# ReA4091_Mini_2024-10-24_SCH.net
KiCad netlist of a schematic drawn in EasyEDA
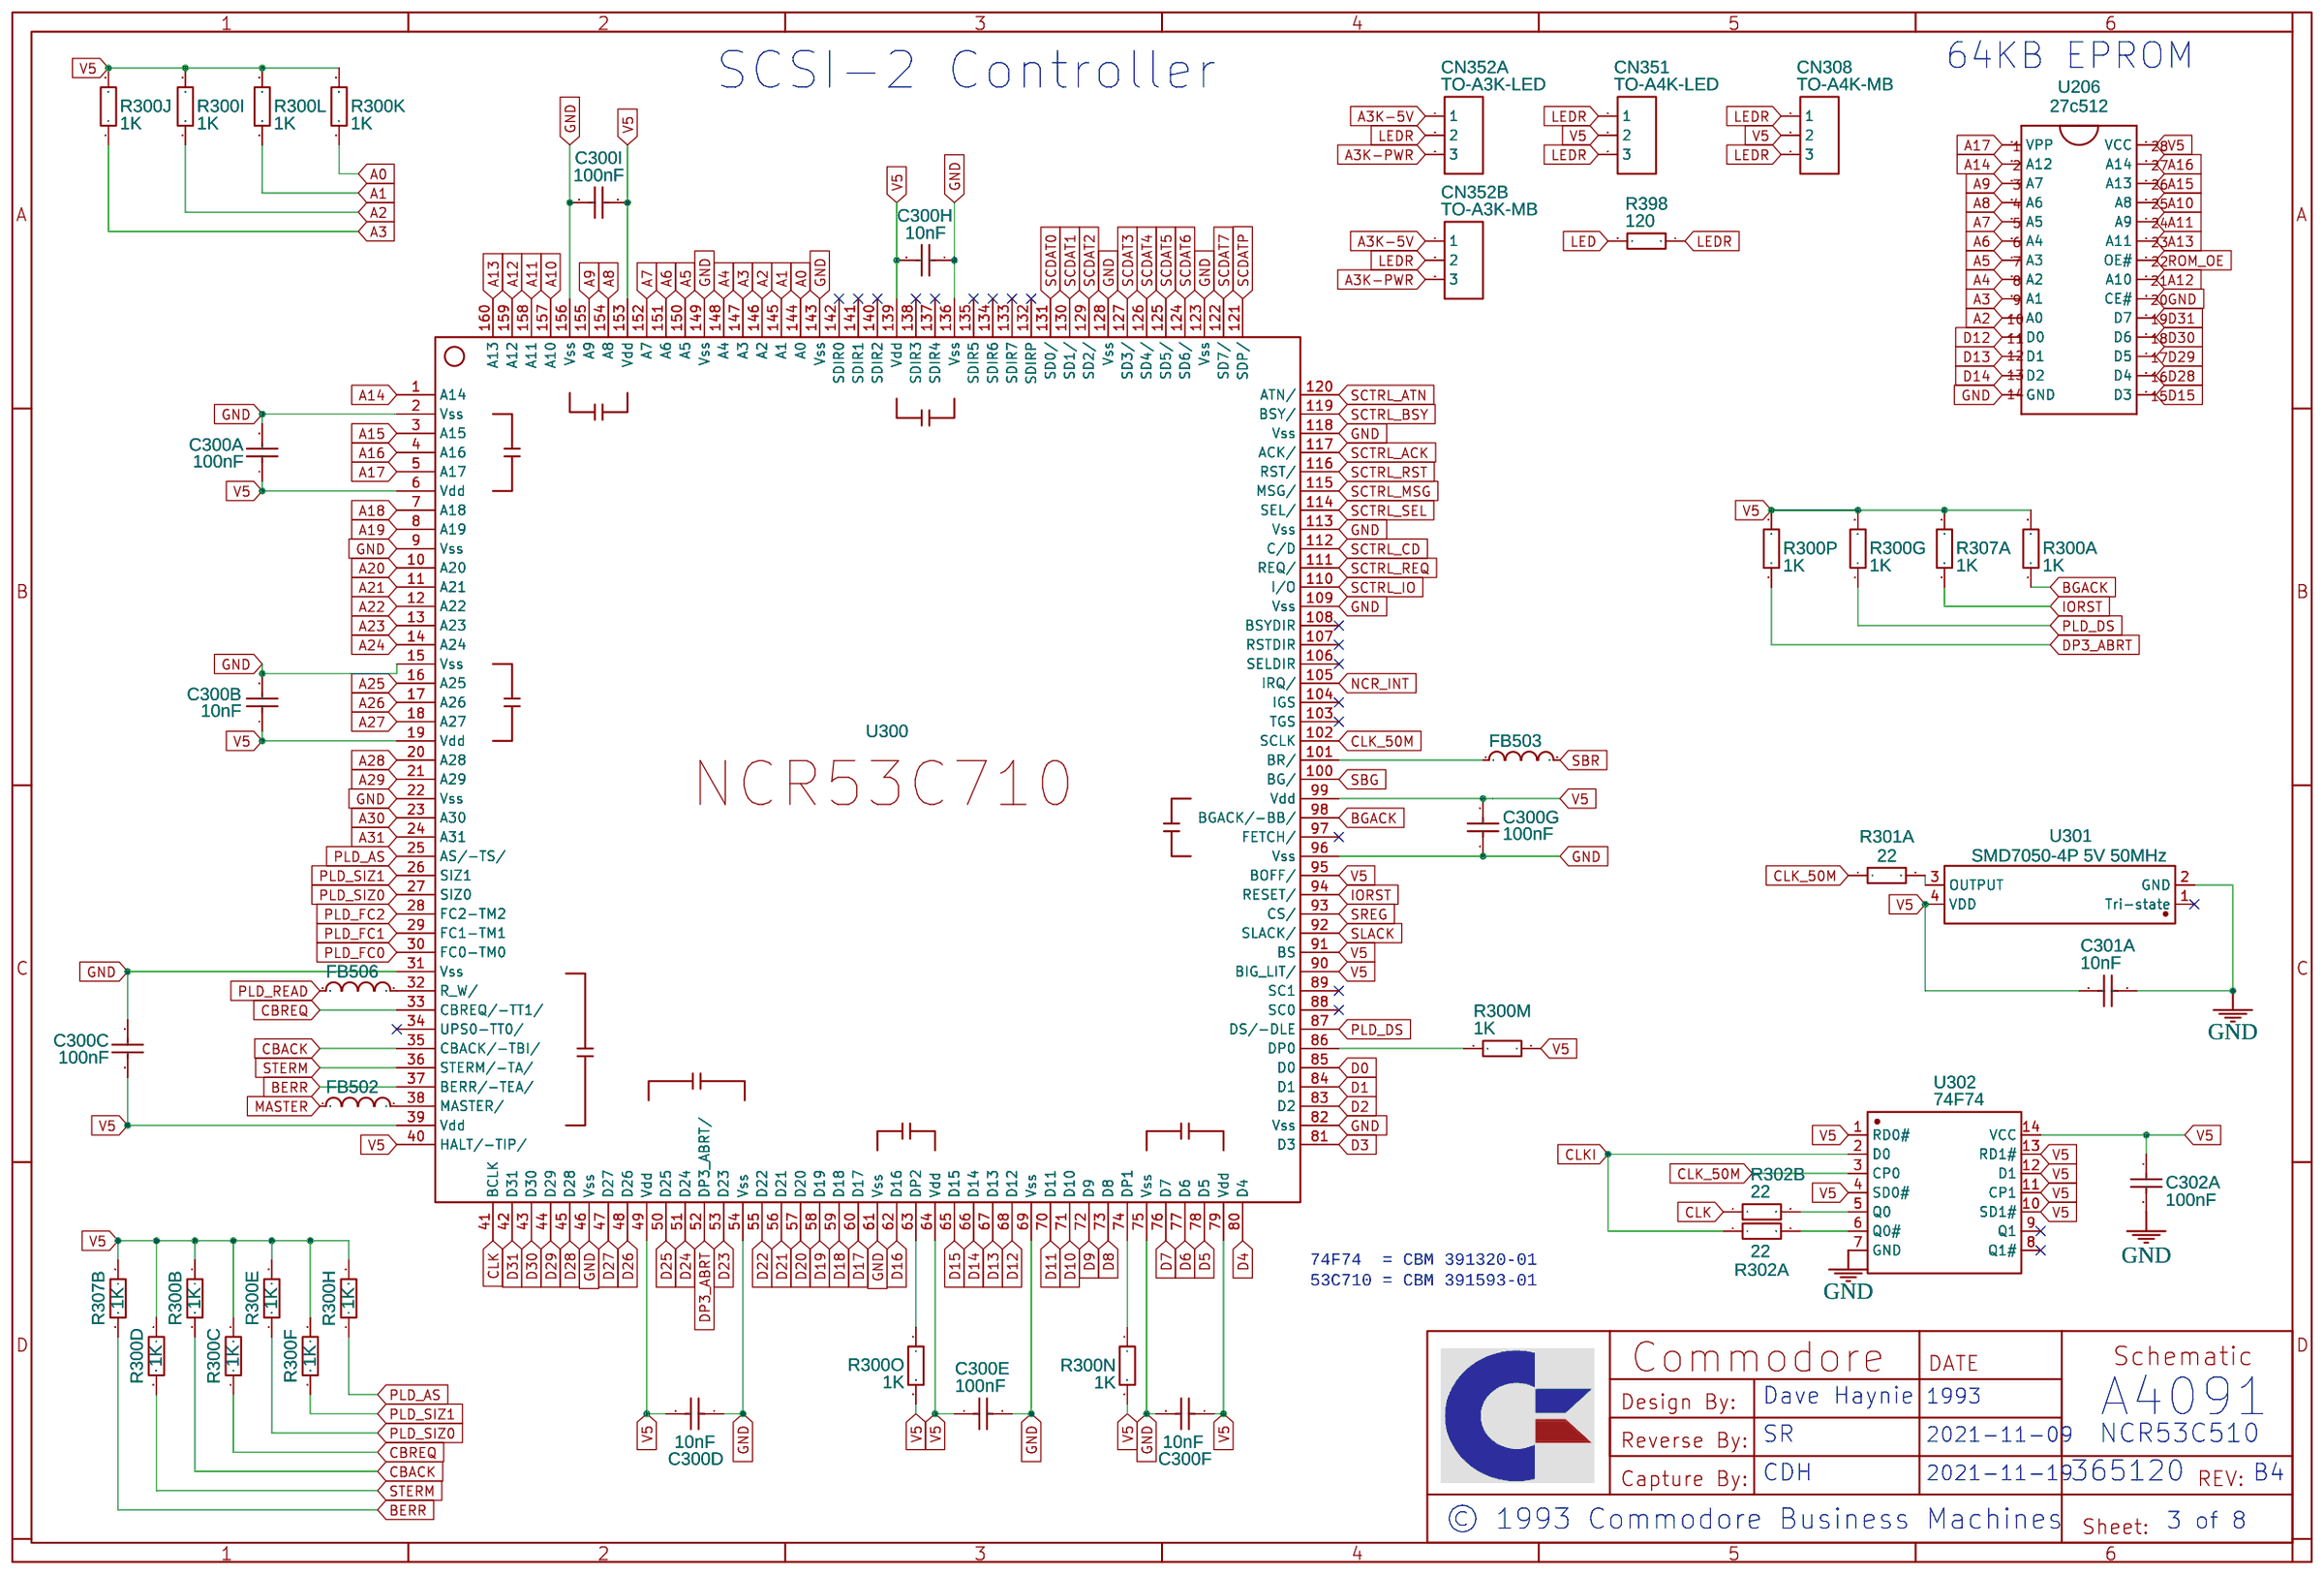
[diagram p0: NCR53C710]
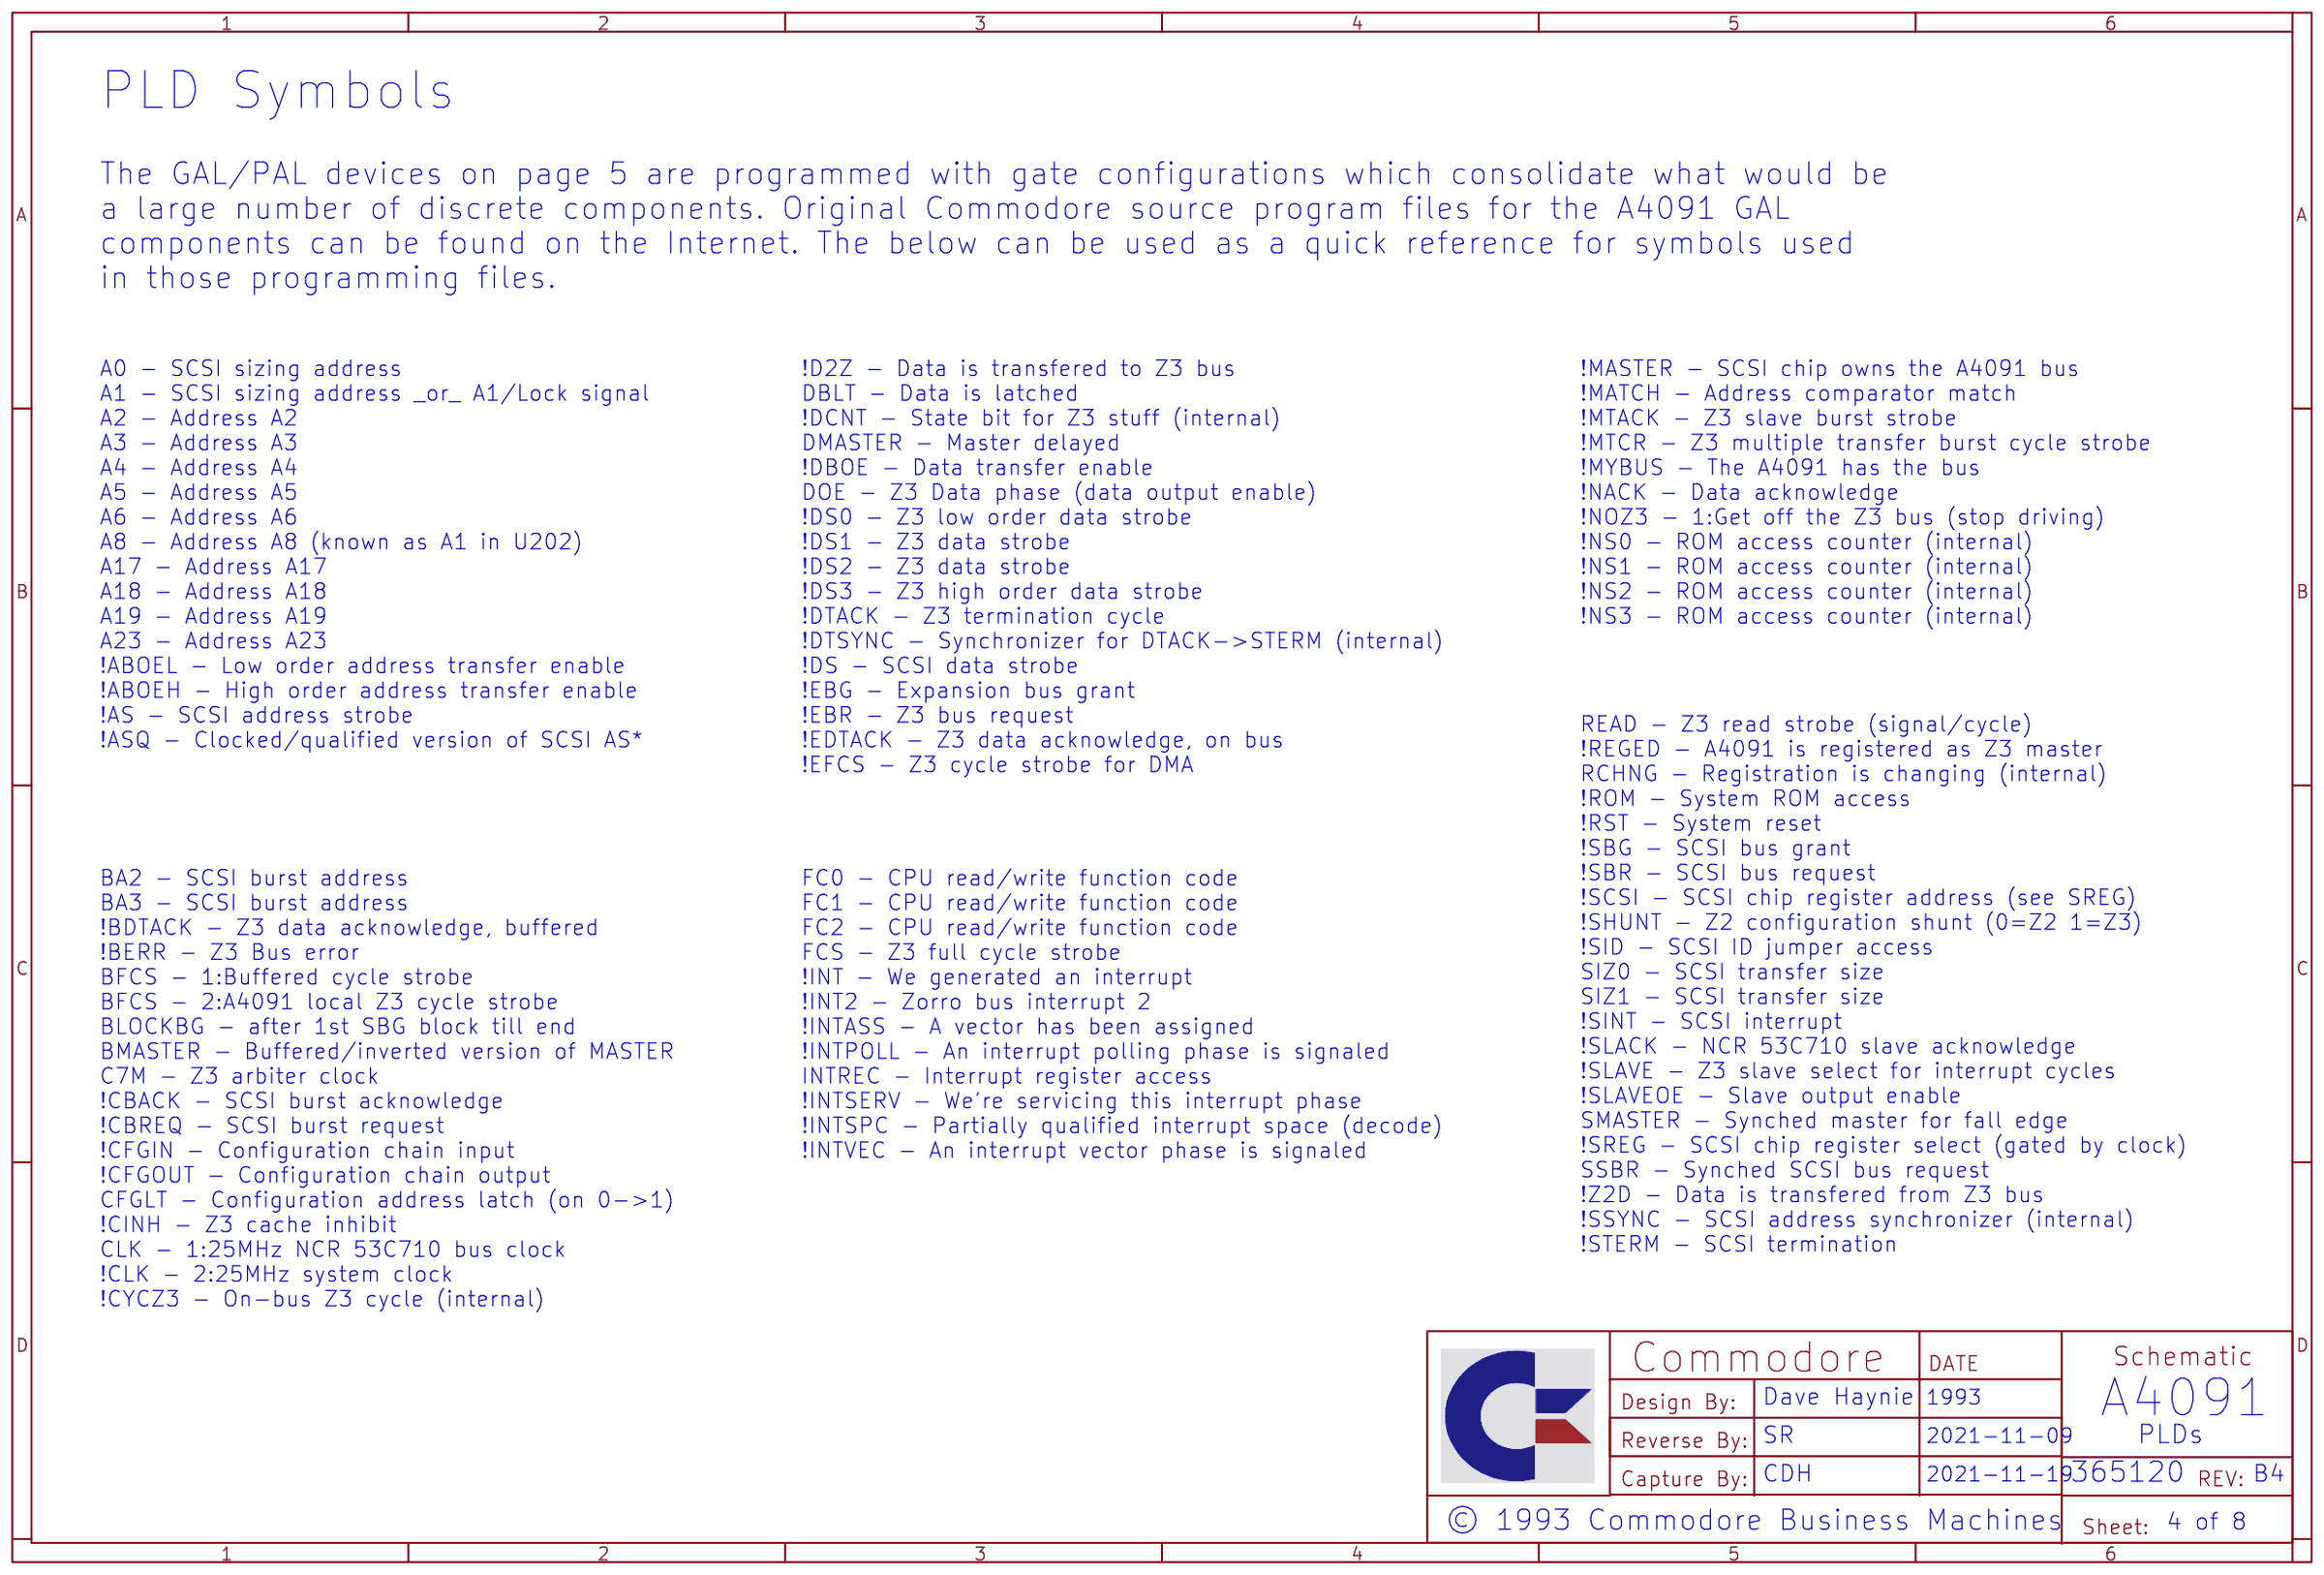
[diagram p1: PLD Symbols]
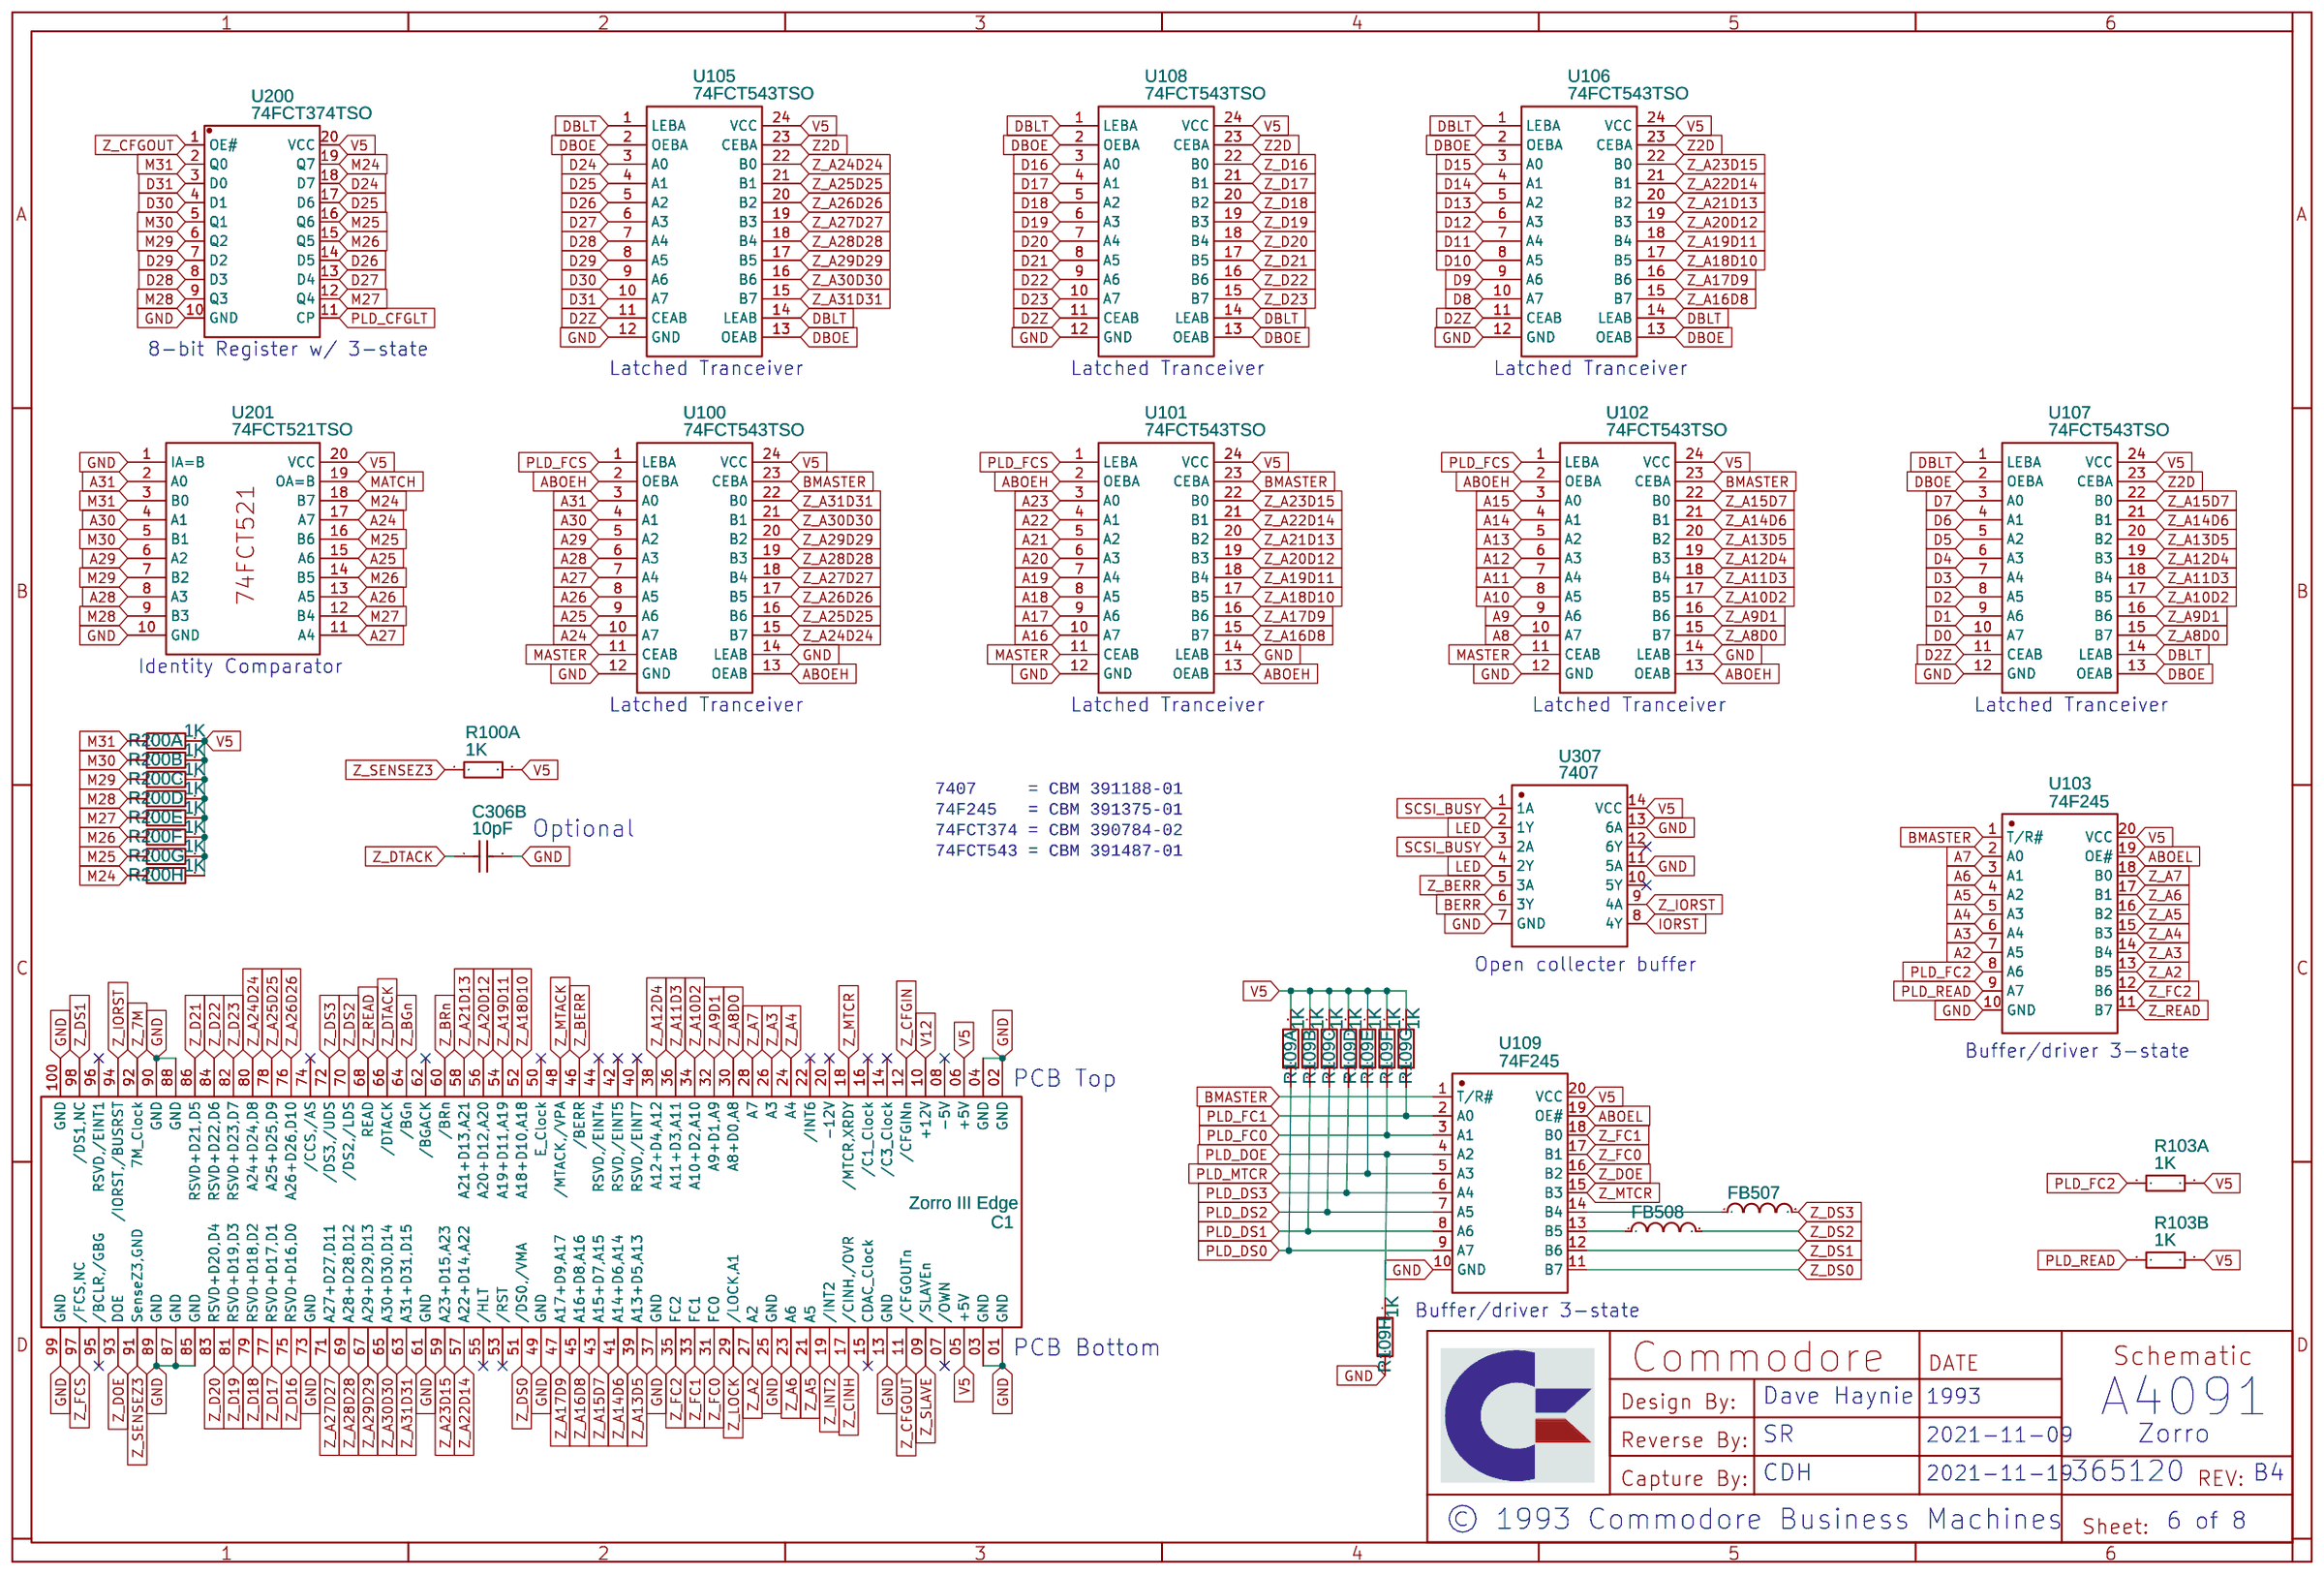
[diagram p2: Zorro]
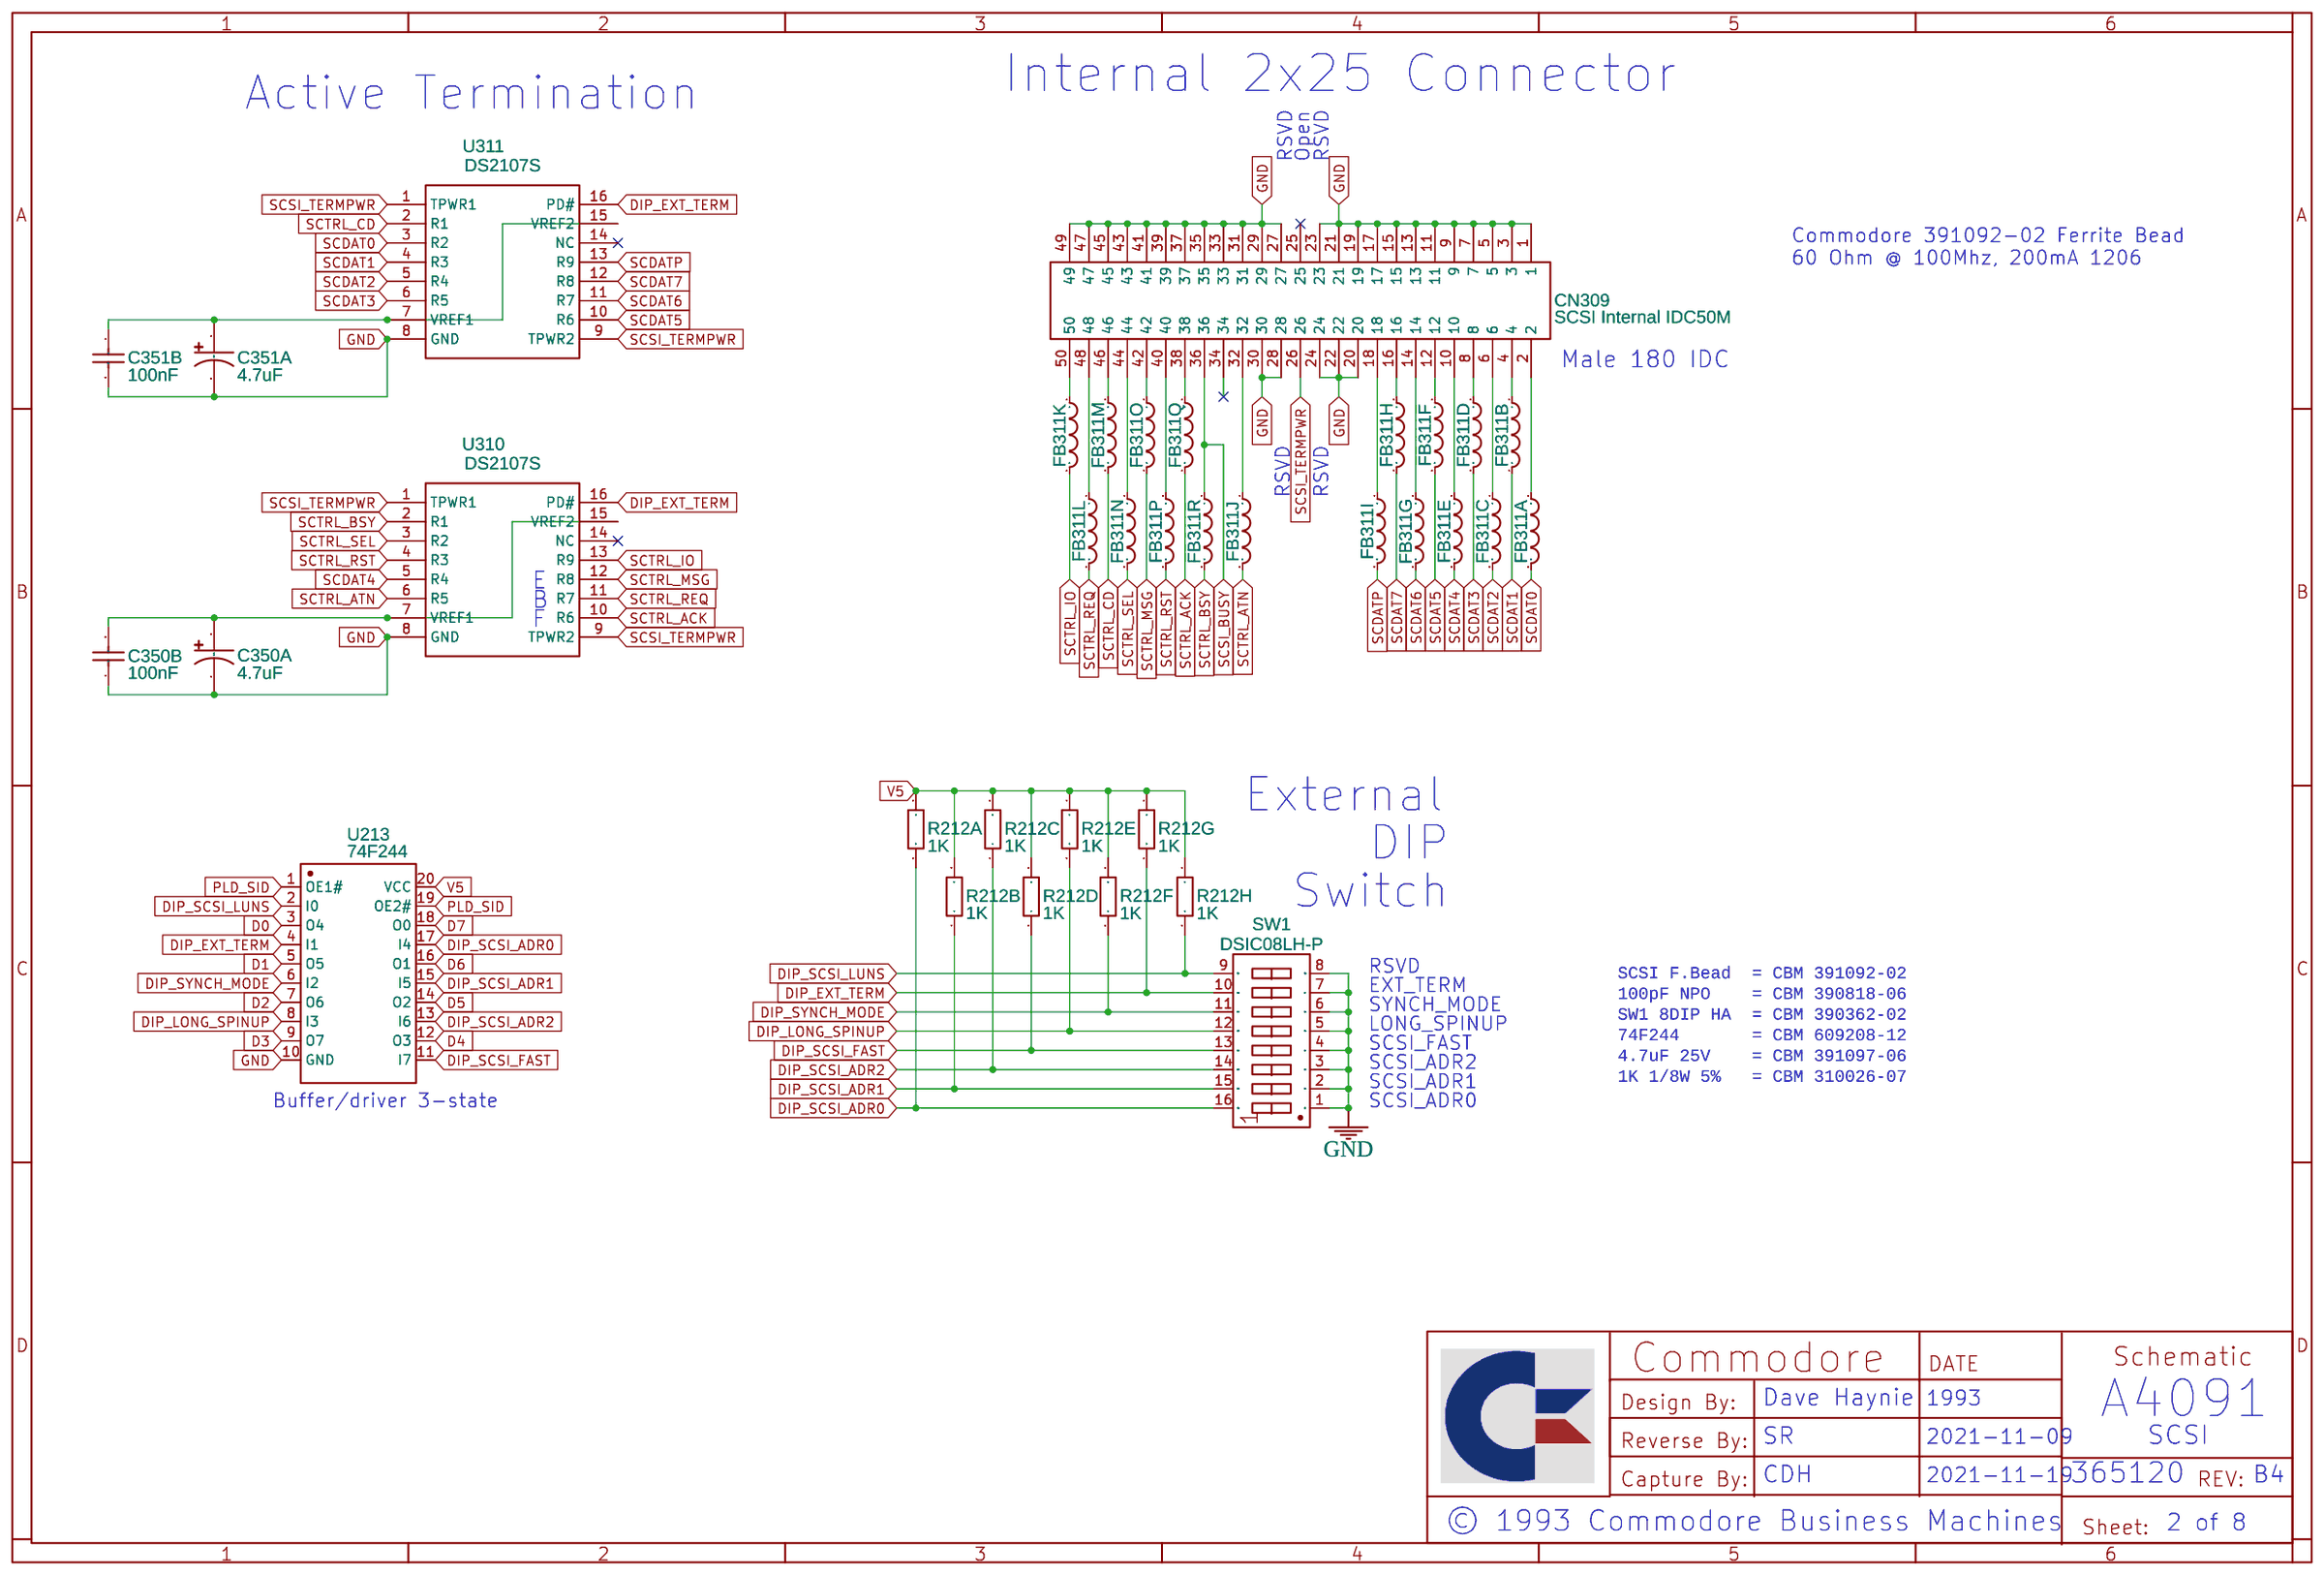
[diagram p3: SCSI]
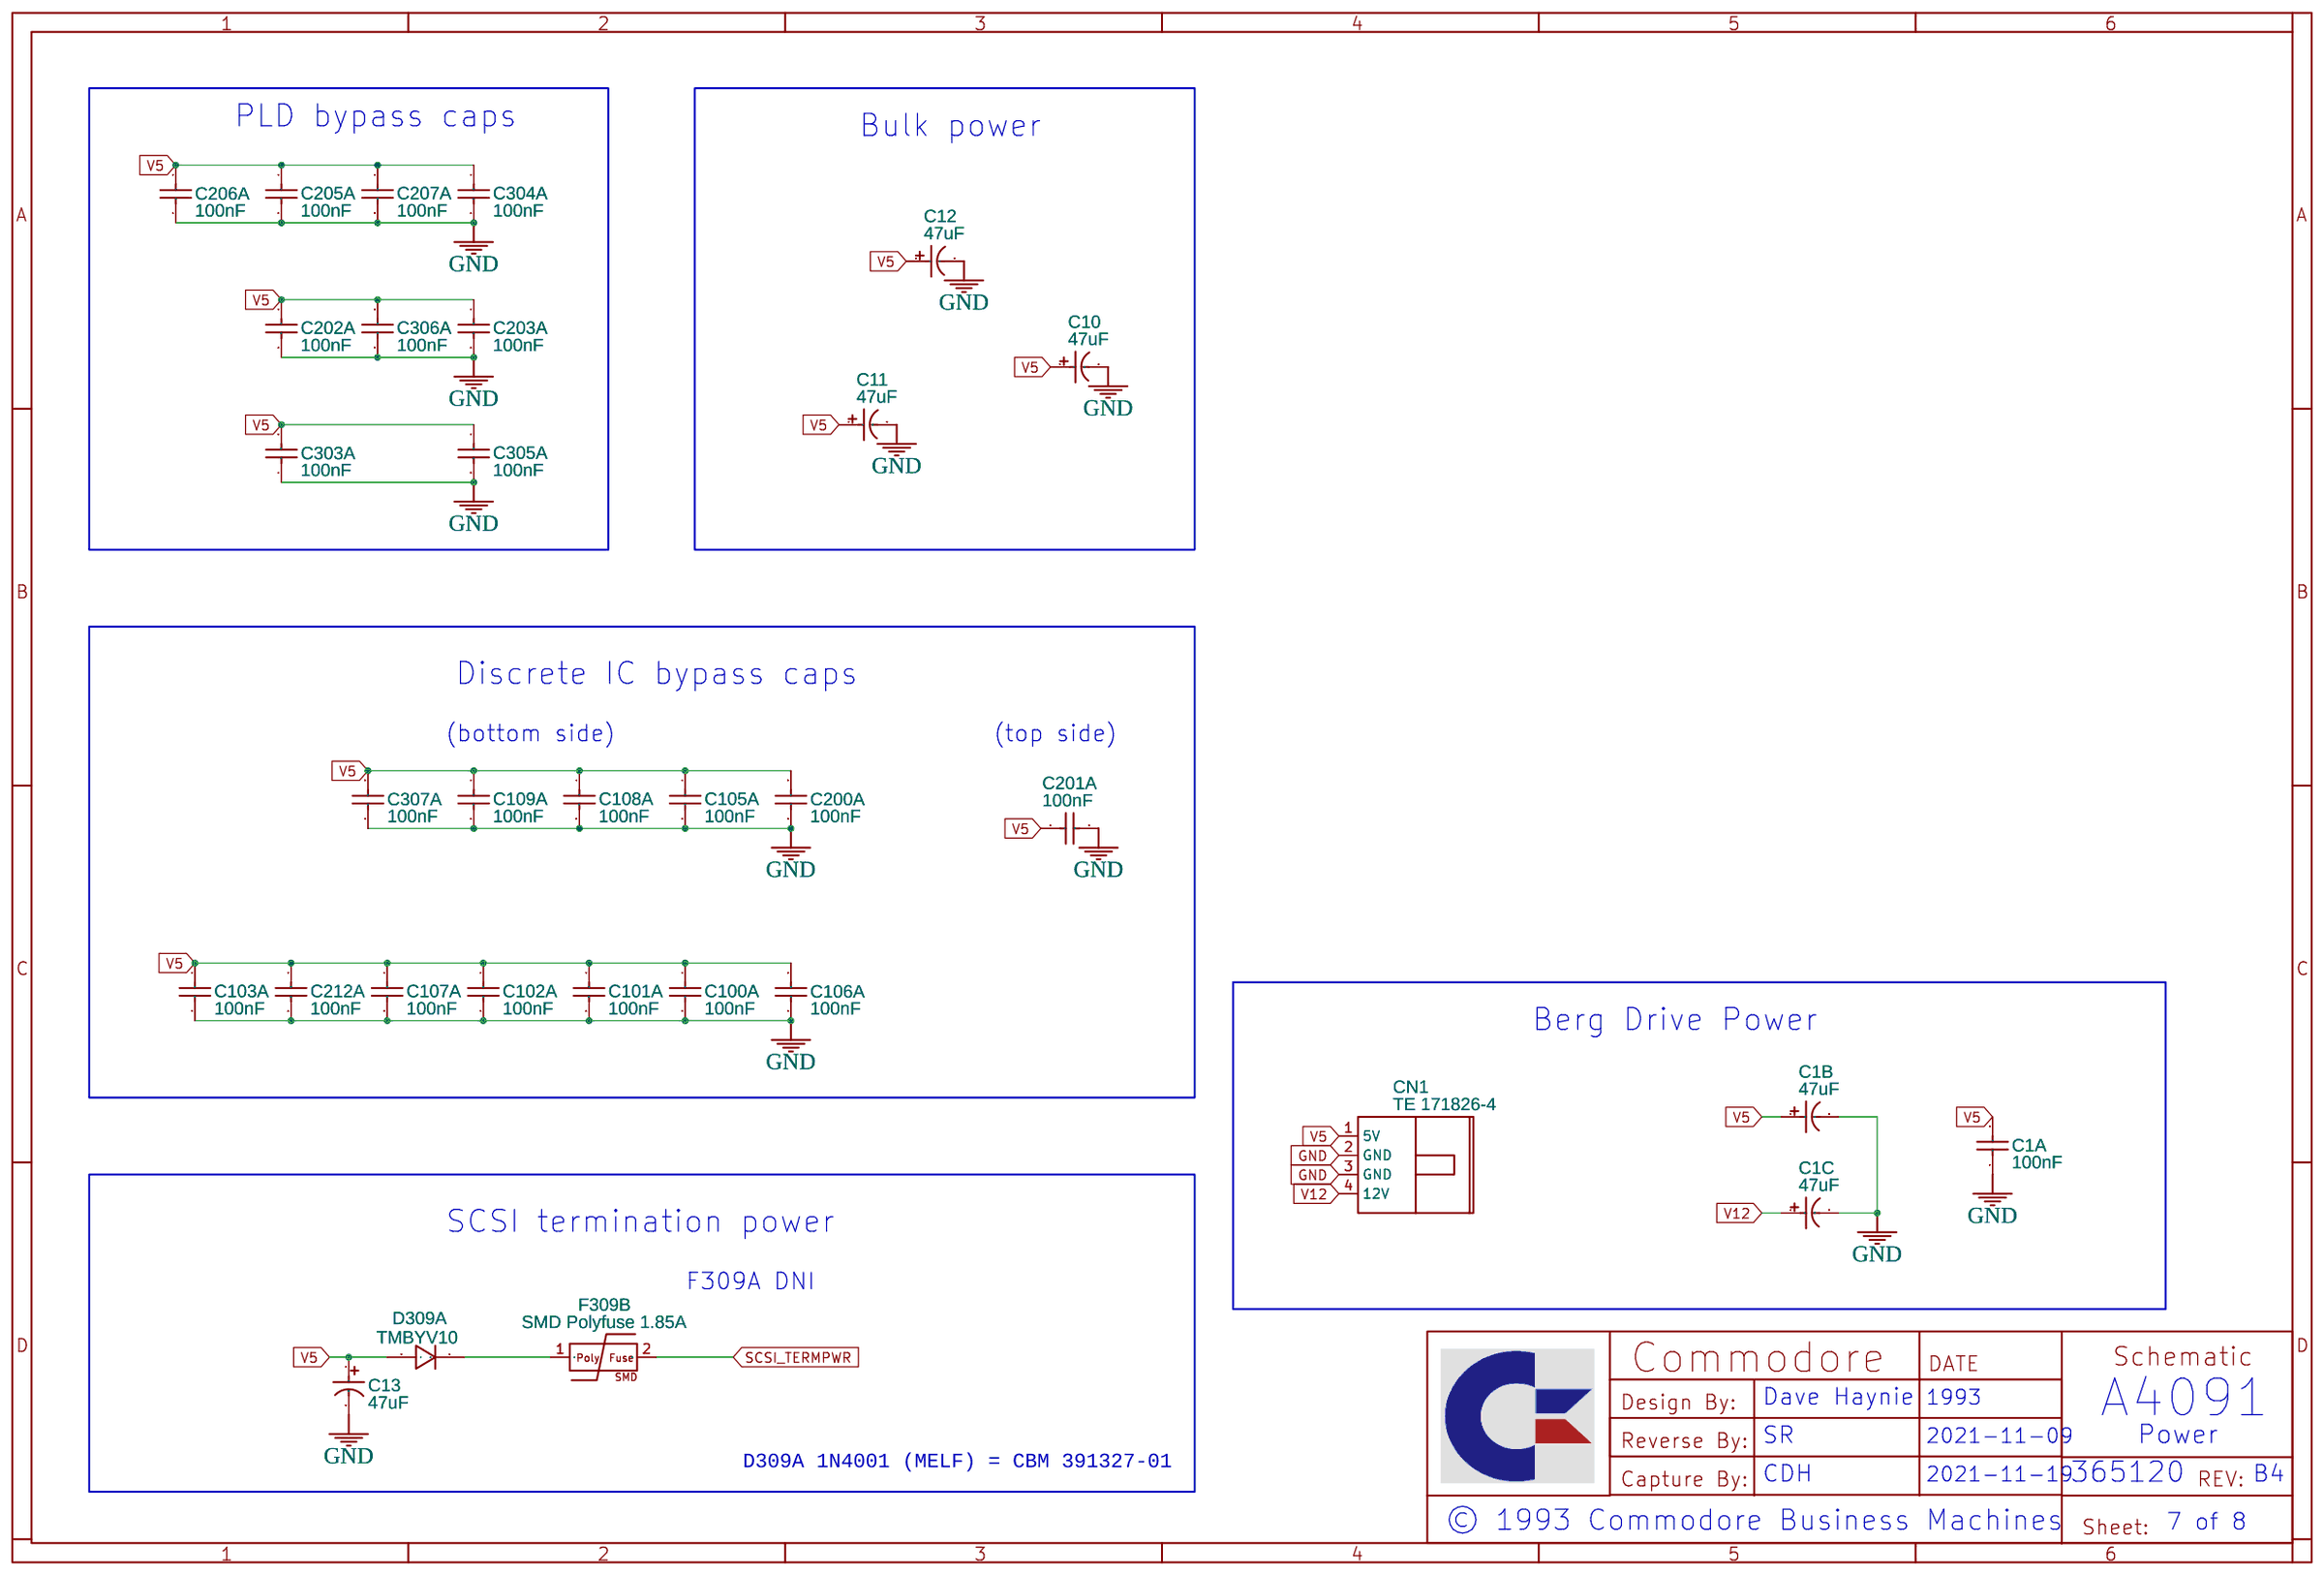
[diagram p4: Power]
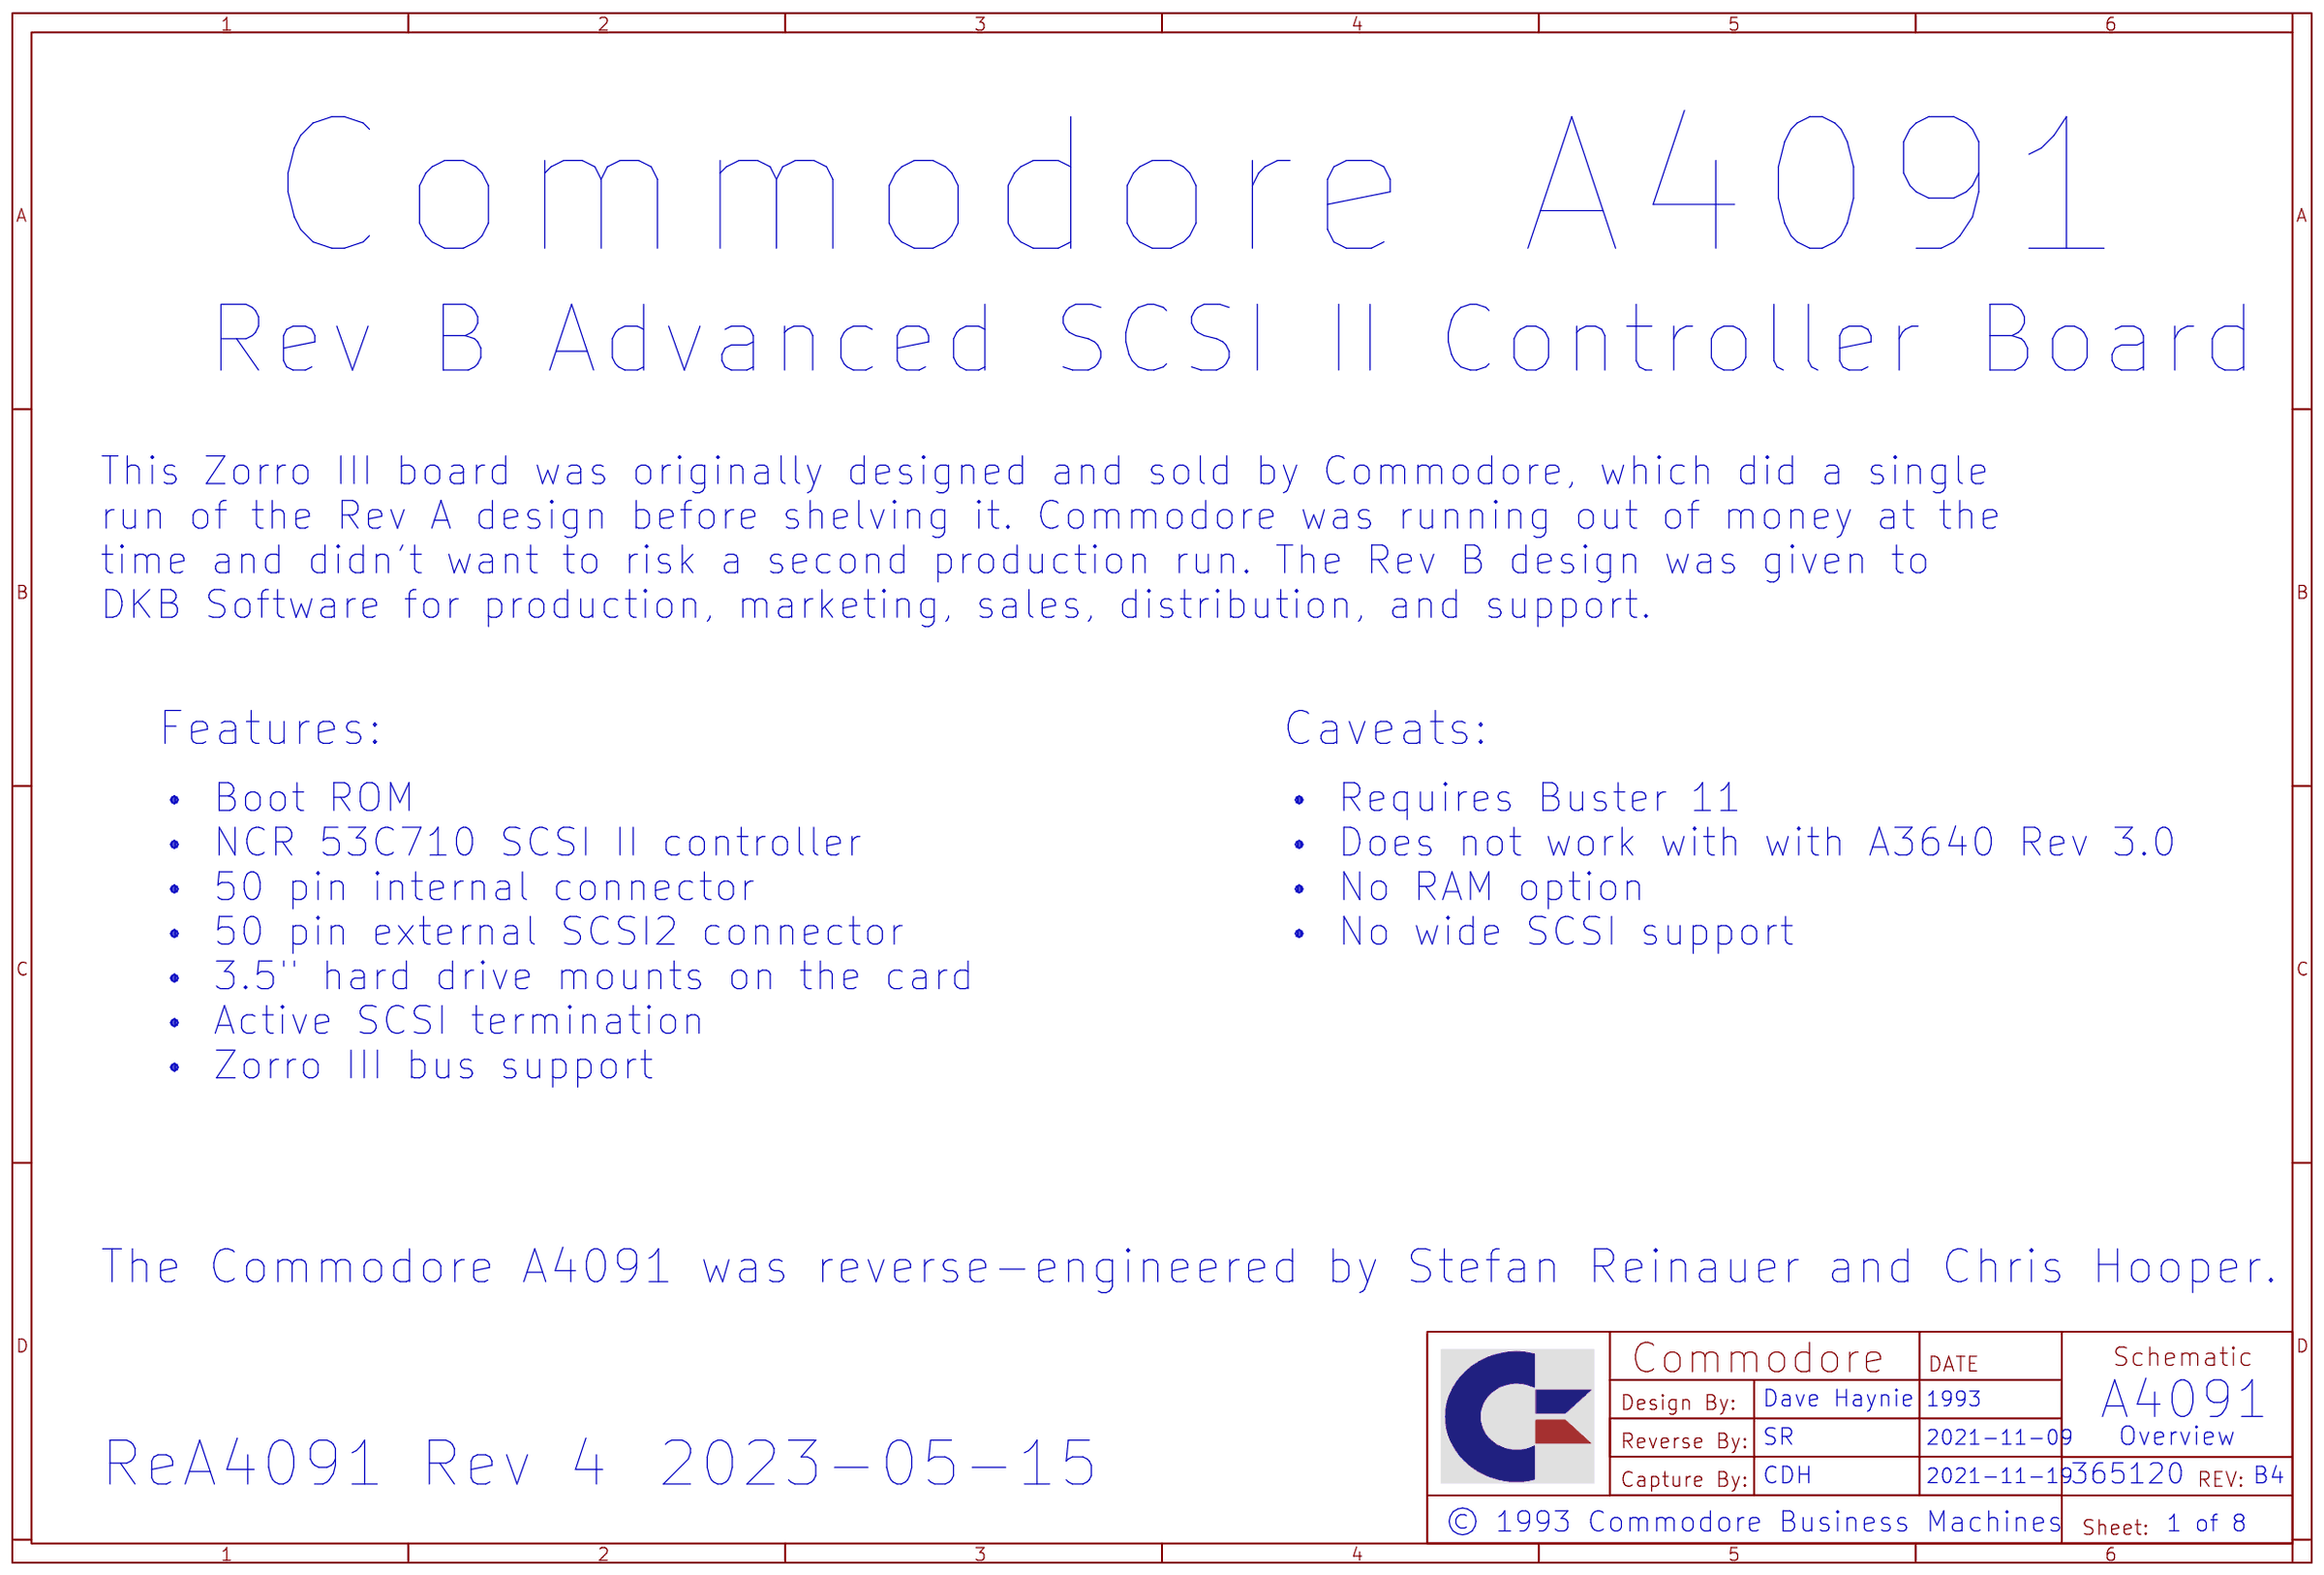
[diagram p5: Overview]
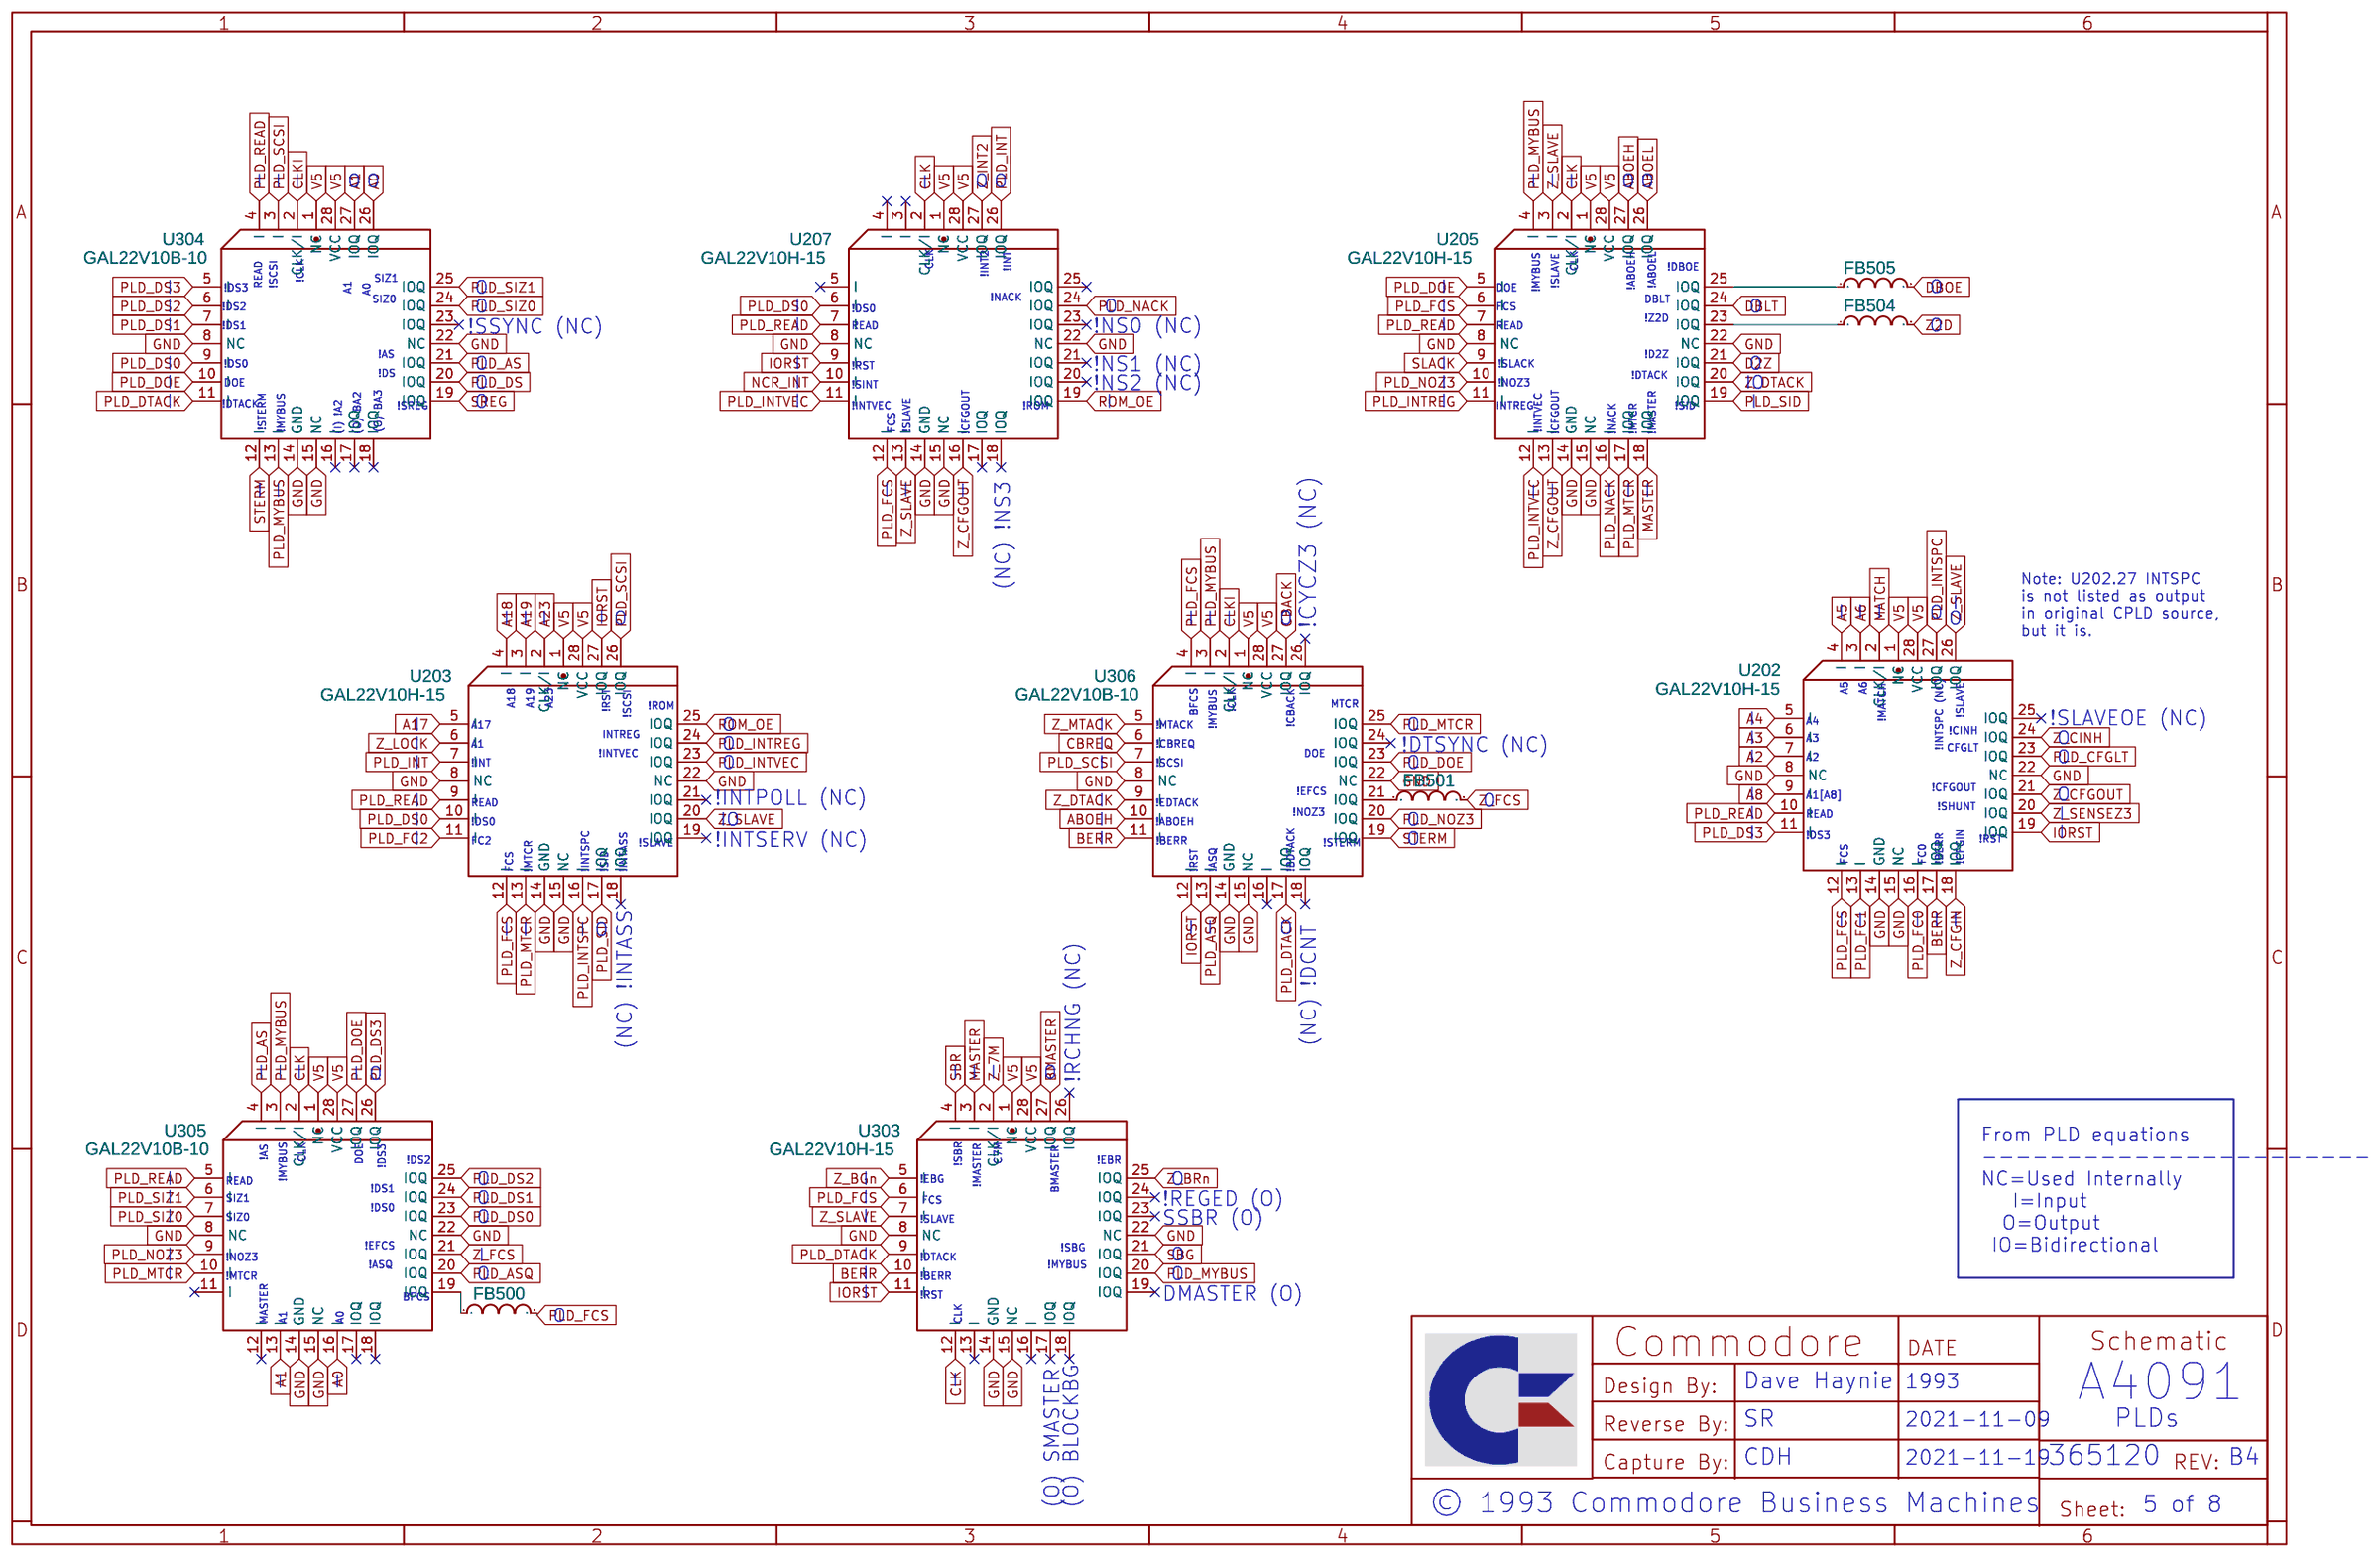
[diagram p6: PLDs]

(export (version "E")
  (design (tool "Eeschema 10.0.6"))
  (components
    (comp (ref "C300A")
      (value "100nF")
      (fields (field (name "Manufacturer Part") "CL31B104KBCNNNC") (field (name "Manufacturer") "SAMSUNG"))
      (libsource (lib "") (part "CL31B104KBCNNNC_5"))
    )
    (comp (ref "C300B")
      (value "10nF")
      (fields (field (name "Manufacturer Part") "1206B103K500NT") (field (name "Manufacturer") "FH"))
      (libsource (lib "") (part "1206B103K500NT_1"))
    )
    (comp (ref "C300C")
      (value "100nF")
      (fields (field (name "Manufacturer Part") "CL31B104KBCNNNC") (field (name "Manufacturer") "SAMSUNG"))
      (libsource (lib "") (part "CL31B104KBCNNNC_2"))
    )
    (comp (ref "C300D")
      (value "10nF")
      (fields (field (name "Manufacturer Part") "1206B103K500NT") (field (name "Manufacturer") "FH"))
      (libsource (lib "") (part "1206B103K500NT_4"))
    )
    (comp (ref "C300E")
      (value "100nF")
      (fields (field (name "Manufacturer Part") "CL31B104KBCNNNC") (field (name "Manufacturer") "SAMSUNG"))
      (libsource (lib "") (part "CL31B104KBCNNNC_4"))
    )
    (comp (ref "C300F")
      (value "10nF")
      (fields (field (name "Manufacturer Part") "1206B103K500NT") (field (name "Manufacturer") "FH"))
      (libsource (lib "") (part "1206B103K500NT_3"))
    )
    (comp (ref "C300G")
      (value "100nF")
      (fields (field (name "Manufacturer Part") "CL31B104KBCNNNC") (field (name "Manufacturer") "SAMSUNG"))
      (libsource (lib "") (part "CL31B104KBCNNNC_3"))
    )
    (comp (ref "C300H")
      (value "10nF")
      (fields (field (name "Manufacturer Part") "1206B103K500NT") (field (name "Manufacturer") "FH"))
      (libsource (lib "") (part "1206B103K500NT_2"))
    )
    (comp (ref "C300I")
      (value "100nF")
      (fields (field (name "Manufacturer Part") "CL31B104KBCNNNC") (field (name "Manufacturer") "SAMSUNG"))
      (libsource (lib "") (part "CL31B104KBCNNNC"))
    )
    (comp (ref "C301A")
      (value "10nF")
      (fields (field (name "Manufacturer Part") "1206B103K500NT") (field (name "Manufacturer") "FH"))
      (libsource (lib "") (part "1206B103K500NT"))
    )
    (comp (ref "C302A")
      (value "100nF")
      (fields (field (name "Manufacturer Part") "CL31B104KBCNNNC") (field (name "Manufacturer") "SAMSUNG"))
      (libsource (lib "") (part "CL31B104KBCNNNC_1"))
    )
    (comp (ref "CN308")
      (value "TO-A4K-MB")
      (fields (field (name "Manufacturer Part") "Header2.54mm 1*3P") (field (name "Manufacturer") "BOOMELE"))
      (libsource (lib "") (part "Header-Male-2.54_1x3_1"))
    )
    (comp (ref "CN351")
      (value "TO-A4K-LED")
      (fields (field (name "Manufacturer Part") "Header2.54mm 1*3P") (field (name "Manufacturer") "BOOMELE"))
      (libsource (lib "") (part "Header-Male-2.54_1x3_1"))
    )
    (comp (ref "CN352A")
      (value "TO-A3K-LED")
      (fields (field (name "Manufacturer Part") "Header2.54mm 1*3P") (field (name "Manufacturer") "BOOMELE"))
      (libsource (lib "") (part "Header-Male-2.54_1x3_2"))
    )
    (comp (ref "CN352B")
      (value "TO-A3K-MB")
      (fields (field (name "Manufacturer Part") "Header2.54mm 1*3P") (field (name "Manufacturer") "BOOMELE"))
      (libsource (lib "") (part "Header-Male-2.54_1x3"))
    )
    (comp (ref "FB502")
      (value "60Ω")
      (fields (field (name "Manufacturer Part") "CBG321609U600T") (field (name "Manufacturer") "FH"))
      (libsource (lib "") (part "MLB3216-601(f)"))
    )
    (comp (ref "FB503")
      (value "60Ω")
      (fields (field (name "Manufacturer Part") "CBG321609U600T") (field (name "Manufacturer") "FH"))
      (libsource (lib "") (part "MLB3216-601(f)_1"))
    )
    (comp (ref "FB506")
      (value "60Ω")
      (fields (field (name "Manufacturer Part") "CBG321609U600T") (field (name "Manufacturer") "FH"))
      (libsource (lib "") (part "MLB3216-601(f)"))
    )
    (comp (ref "R300A")
      (value "1K")
      (fields (field (name "Manufacturer Part") "1206W4F1001T5E") (field (name "Manufacturer") "UniOhm"))
      (libsource (lib "") (part "1206W4F1001T5E_10"))
    )
    (comp (ref "R300B")
      (value "1K")
      (fields (field (name "Manufacturer Part") "1206W4F1001T5E") (field (name "Manufacturer") "UniOhm"))
      (libsource (lib "") (part "1206W4F1001T5E_12"))
    )
    (comp (ref "R300C")
      (value "1K")
      (fields (field (name "Manufacturer Part") "1206W4F1001T5E") (field (name "Manufacturer") "UniOhm"))
      (libsource (lib "") (part "1206W4F1001T5E"))
    )
    (comp (ref "R300D")
      (value "1K")
      (fields (field (name "Manufacturer Part") "1206W4F1001T5E") (field (name "Manufacturer") "UniOhm"))
      (libsource (lib "") (part "1206W4F1001T5E_4"))
    )
    (comp (ref "R300E")
      (value "1K")
      (fields (field (name "Manufacturer Part") "1206W4F1001T5E") (field (name "Manufacturer") "UniOhm"))
      (libsource (lib "") (part "1206W4F1001T5E_14"))
    )
    (comp (ref "R300F")
      (value "1K")
      (fields (field (name "Manufacturer Part") "1206W4F1001T5E") (field (name "Manufacturer") "UniOhm"))
      (libsource (lib "") (part "1206W4F1001T5E_8"))
    )
    (comp (ref "R300G")
      (value "1K")
      (fields (field (name "Manufacturer Part") "1206W4F1001T5E") (field (name "Manufacturer") "UniOhm"))
      (libsource (lib "") (part "1206W4F1001T5E_17"))
    )
    (comp (ref "R300H")
      (value "1K")
      (fields (field (name "Manufacturer Part") "1206W4F1001T5E") (field (name "Manufacturer") "UniOhm"))
      (libsource (lib "") (part "1206W4F1001T5E_11"))
    )
    (comp (ref "R300I")
      (value "1K")
      (fields (field (name "Manufacturer Part") "1206W4F1001T5E") (field (name "Manufacturer") "UniOhm"))
      (libsource (lib "") (part "1206W4F1001T5E_16"))
    )
    (comp (ref "R300J")
      (value "1K")
      (fields (field (name "Manufacturer Part") "1206W4F1001T5E") (field (name "Manufacturer") "UniOhm"))
      (libsource (lib "") (part "1206W4F1001T5E_9"))
    )
    (comp (ref "R300K")
      (value "1K")
      (fields (field (name "Manufacturer Part") "1206W4F1001T5E") (field (name "Manufacturer") "UniOhm"))
      (libsource (lib "") (part "1206W4F1001T5E_1"))
    )
    (comp (ref "R300L")
      (value "1K")
      (fields (field (name "Manufacturer Part") "1206W4F1001T5E") (field (name "Manufacturer") "UniOhm"))
      (libsource (lib "") (part "1206W4F1001T5E_15"))
    )
    (comp (ref "R300M")
      (value "1K")
      (fields (field (name "Manufacturer Part") "1206W4F1001T5E") (field (name "Manufacturer") "UniOhm"))
      (libsource (lib "") (part "1206W4F1001T5E_2"))
    )
    (comp (ref "R300N")
      (value "1K")
      (fields (field (name "Manufacturer Part") "1206W4F1001T5E") (field (name "Manufacturer") "UniOhm"))
      (libsource (lib "") (part "1206W4F1001T5E_7"))
    )
    (comp (ref "R300O")
      (value "1K")
      (fields (field (name "Manufacturer Part") "1206W4F1001T5E") (field (name "Manufacturer") "UniOhm"))
      (libsource (lib "") (part "1206W4F1001T5E_13"))
    )
    (comp (ref "R300P")
      (value "1K")
      (fields (field (name "Manufacturer Part") "1206W4F1001T5E") (field (name "Manufacturer") "UniOhm"))
      (libsource (lib "") (part "1206W4F1001T5E_6"))
    )
    (comp (ref "R301A")
      (value "22")
      (fields
        (field (name "Manufacturer Part") "1206W4F220JT5E")
        (field (name "Manufacturer") "UNI-ROYAL(厚声)")
      )
      (libsource (lib "") (part "RS-06K22R0FT_1"))
    )
    (comp (ref "R302A")
      (value "22")
      (fields
        (field (name "Manufacturer Part") "1206W4F220JT5E")
        (field (name "Manufacturer") "UNI-ROYAL(厚声)")
      )
      (libsource (lib "") (part "RS-06K22R0FT"))
    )
    (comp (ref "R302B")
      (value "22")
      (fields
        (field (name "Manufacturer Part") "1206W4F220JT5E")
        (field (name "Manufacturer") "UNI-ROYAL(厚声)")
      )
      (libsource (lib "") (part "RS-06K22R0FT_2"))
    )
    (comp (ref "R307A")
      (value "1K")
      (fields (field (name "Manufacturer Part") "1206W4F1001T5E") (field (name "Manufacturer") "UniOhm"))
      (libsource (lib "") (part "1206W4F1001T5E_3"))
    )
    (comp (ref "R307B")
      (value "1K")
      (fields (field (name "Manufacturer Part") "1206W4F1001T5E") (field (name "Manufacturer") "UniOhm"))
      (libsource (lib "") (part "1206W4F1001T5E_5"))
    )
    (comp (ref "R398")
      (value "120")
      (fields
        (field (name "Manufacturer Part") "1206W4F1200T5E")
        (field (name "Manufacturer") "UNI-ROYAL(厚声)")
      )
      (libsource (lib "") (part "RTT061200FTP"))
    )
    (comp (ref "U206")
      (value "27c512")
      (fields
        (field (name "Manufacturer Part") "IC254V-12-28-0743-P1524")
        (field (name "Manufacturer") "XFCN(兴飞)")
      )
      (libsource (lib "") (part "27c256"))
    )
    (comp (ref "U300") (value "NCR53C710") (libsource (lib "") (part "NCR53C710")))
    (comp (ref "U301")
      (value "SMD7050-4P 5V 50MHz")
      (fields
        (field (name "Manufacturer Part") "S7D50.000000A20F30T")
        (field (name "Manufacturer") "SCTF(星通时频)")
      )
      (libsource (lib "") (part "S7D50.000000A20F30T"))
    )
    (comp (ref "U302")
      (value "74F74")
      (fields (field (name "Manufacturer Part") "74F74D") (field (name "Manufacturer") "PHILIPS"))
      (libsource (lib "") (part "74F74D"))
    )
    (comp (ref "C1") (value "Zorro III Edge") (libsource (lib "") (part "Zorro III Edge")))
    (comp (ref "C306B")
      (value "10pF")
      (fields (field (name "Manufacturer Part") "CL21C100JBANNNC") (field (name "Manufacturer") "SAMSUNG"))
      (libsource (lib "") (part "CL21C100JBANNNC"))
    )
    (comp (ref "FB507")
      (value "60Ω")
      (fields (field (name "Manufacturer Part") "CBG321609U600T") (field (name "Manufacturer") "FH"))
      (libsource (lib "") (part "MLB3216-601(f)"))
    )
    (comp (ref "FB508")
      (value "60Ω")
      (fields (field (name "Manufacturer Part") "CBG321609U600T") (field (name "Manufacturer") "FH"))
      (libsource (lib "") (part "MLB3216-601(f)"))
    )
    (comp (ref "R100A")
      (value "1K")
      (fields (field (name "Manufacturer Part") "1206W4F1001T5E") (field (name "Manufacturer") "UniOhm"))
      (libsource (lib "") (part "1206W4F1001T5E_3"))
    )
    (comp (ref "R103A")
      (value "1K")
      (fields (field (name "Manufacturer Part") "1206W4F1001T5E") (field (name "Manufacturer") "UniOhm"))
      (libsource (lib "") (part "1206W4F1001T5E"))
    )
    (comp (ref "R103B")
      (value "1K")
      (fields (field (name "Manufacturer Part") "1206W4F1001T5E") (field (name "Manufacturer") "UniOhm"))
      (libsource (lib "") (part "1206W4F1001T5E_6"))
    )
    (comp (ref "R109A")
      (value "1K")
      (fields (field (name "Manufacturer Part") "1206W4F1001T5E") (field (name "Manufacturer") "UniOhm"))
      (libsource (lib "") (part "1206W4F1001T5E_5"))
    )
    (comp (ref "R109B")
      (value "1K")
      (fields (field (name "Manufacturer Part") "1206W4F1001T5E") (field (name "Manufacturer") "UniOhm"))
      (libsource (lib "") (part "1206W4F1001T5E_13"))
    )
    (comp (ref "R109C")
      (value "1K")
      (fields (field (name "Manufacturer Part") "1206W4F1001T5E") (field (name "Manufacturer") "UniOhm"))
      (libsource (lib "") (part "1206W4F1001T5E_12"))
    )
    (comp (ref "R109D")
      (value "1K")
      (fields (field (name "Manufacturer Part") "1206W4F1001T5E") (field (name "Manufacturer") "UniOhm"))
      (libsource (lib "") (part "1206W4F1001T5E_15"))
    )
    (comp (ref "R109E")
      (value "1K")
      (fields (field (name "Manufacturer Part") "1206W4F1001T5E") (field (name "Manufacturer") "UniOhm"))
      (libsource (lib "") (part "1206W4F1001T5E_7"))
    )
    (comp (ref "R109F")
      (value "1K")
      (fields (field (name "Manufacturer Part") "1206W4F1001T5E") (field (name "Manufacturer") "UniOhm"))
      (libsource (lib "") (part "1206W4F1001T5E_1"))
    )
    (comp (ref "R109G")
      (value "1K")
      (fields (field (name "Manufacturer Part") "1206W4F1001T5E") (field (name "Manufacturer") "UniOhm"))
      (libsource (lib "") (part "1206W4F1001T5E_9"))
    )
    (comp (ref "R109H")
      (value "1K")
      (fields (field (name "Manufacturer Part") "1206W4F1001T5E") (field (name "Manufacturer") "UniOhm"))
      (libsource (lib "") (part "1206W4F1001T5E_16"))
    )
    (comp (ref "R200A")
      (value "1K")
      (fields (field (name "Manufacturer Part") "1206W4F1001T5E") (field (name "Manufacturer") "UniOhm"))
      (libsource (lib "") (part "1206W4F1001T5E_8"))
    )
    (comp (ref "R200B")
      (value "1K")
      (fields (field (name "Manufacturer Part") "1206W4F1001T5E") (field (name "Manufacturer") "UniOhm"))
      (libsource (lib "") (part "1206W4F1001T5E_14"))
    )
    (comp (ref "R200C")
      (value "1K")
      (fields (field (name "Manufacturer Part") "1206W4F1001T5E") (field (name "Manufacturer") "UniOhm"))
      (libsource (lib "") (part "1206W4F1001T5E_18"))
    )
    (comp (ref "R200D")
      (value "1K")
      (fields (field (name "Manufacturer Part") "1206W4F1001T5E") (field (name "Manufacturer") "UniOhm"))
      (libsource (lib "") (part "1206W4F1001T5E_17"))
    )
    (comp (ref "R200E")
      (value "1K")
      (fields (field (name "Manufacturer Part") "1206W4F1001T5E") (field (name "Manufacturer") "UniOhm"))
      (libsource (lib "") (part "1206W4F1001T5E_11"))
    )
    (comp (ref "R200F")
      (value "1K")
      (fields (field (name "Manufacturer Part") "1206W4F1001T5E") (field (name "Manufacturer") "UniOhm"))
      (libsource (lib "") (part "1206W4F1001T5E_10"))
    )
    (comp (ref "R200G")
      (value "1K")
      (fields (field (name "Manufacturer Part") "1206W4F1001T5E") (field (name "Manufacturer") "UniOhm"))
      (libsource (lib "") (part "1206W4F1001T5E_2"))
    )
    (comp (ref "R200H")
      (value "1K")
      (fields (field (name "Manufacturer Part") "1206W4F1001T5E") (field (name "Manufacturer") "UniOhm"))
      (libsource (lib "") (part "1206W4F1001T5E_4"))
    )
    (comp (ref "U100")
      (value "74FCT543TSO")
      (fields (field (name "Manufacturer Part") "CY74FCT543TSOC") (field (name "Manufacturer") "TI"))
      (libsource (lib "") (part "74FCT543TSO"))
    )
    (comp (ref "U101")
      (value "74FCT543TSO")
      (fields (field (name "Manufacturer Part") "CY74FCT543TSOC") (field (name "Manufacturer") "TI"))
      (libsource (lib "") (part "74FCT543TSO"))
    )
    (comp (ref "U102")
      (value "74FCT543TSO")
      (fields (field (name "Manufacturer Part") "CY74FCT543TSOC") (field (name "Manufacturer") "TI"))
      (libsource (lib "") (part "74FCT543TSO"))
    )
    (comp (ref "U103")
      (value "74F245")
      (fields (field (name "Manufacturer Part") "74F245D") (field (name "Manufacturer") "PHILIPS"))
      (libsource (lib "") (part "74F245D"))
    )
    (comp (ref "U105")
      (value "74FCT543TSO")
      (fields (field (name "Manufacturer Part") "CY74FCT543TSOC") (field (name "Manufacturer") "TI"))
      (libsource (lib "") (part "74FCT543TSO"))
    )
    (comp (ref "U106")
      (value "74FCT543TSO")
      (fields (field (name "Manufacturer Part") "CY74FCT543TSOC") (field (name "Manufacturer") "TI"))
      (libsource (lib "") (part "74FCT543TSO"))
    )
    (comp (ref "U107")
      (value "74FCT543TSO")
      (fields (field (name "Manufacturer Part") "CY74FCT543TSOC") (field (name "Manufacturer") "TI"))
      (libsource (lib "") (part "74FCT543TSO"))
    )
    (comp (ref "U108")
      (value "74FCT543TSO")
      (fields (field (name "Manufacturer Part") "CY74FCT543TSOC") (field (name "Manufacturer") "TI"))
      (libsource (lib "") (part "74FCT543TSO"))
    )
    (comp (ref "U109")
      (value "74F245")
      (fields (field (name "Manufacturer Part") "74F245D") (field (name "Manufacturer") "PHILIPS"))
      (libsource (lib "") (part "74F245D"))
    )
    (comp (ref "U200")
      (value "74FCT374TSO")
      (fields (field (name "Manufacturer Part") "74F374D") (field (name "Manufacturer") "PHILIPS"))
      (libsource (lib "") (part "74F374D"))
    )
    (comp (ref "U201")
      (value "74FCT521TSO")
      (fields
        (field (name "Manufacturer Part") "74FCT521CTSOG8")
        (field (name "Manufacturer") "Renesas Electronics")
      )
      (libsource (lib "") (part "74FCT521TSO"))
    )
    (comp (ref "U307")
      (value "7407")
      (fields (field (name "Manufacturer Part") "SN7407DR") (field (name "Manufacturer") "TI(德州仪器)"))
      (libsource (lib "") (part "SN7407DR"))
    )
    (comp (ref "C350A")
      (value "4.7uF")
      (fields
        (field (name "Manufacturer Part") "UWX1E4R7MCL1GB")
        (field (name "Manufacturer") "Nichicon(尼吉康)")
      )
      (libsource (lib "") (part "VZH4R7M1HTR-0406_1"))
    )
    (comp (ref "C350B")
      (value "100nF")
      (fields (field (name "Manufacturer Part") "CL31B104KBCNNNC") (field (name "Manufacturer") "SAMSUNG"))
      (libsource (lib "") (part "CL31B104KBCNNNC"))
    )
    (comp (ref "C351A")
      (value "4.7uF")
      (fields
        (field (name "Manufacturer Part") "UWX1E4R7MCL1GB")
        (field (name "Manufacturer") "Nichicon(尼吉康)")
      )
      (libsource (lib "") (part "VZH4R7M1HTR-0406"))
    )
    (comp (ref "C351B")
      (value "100nF")
      (fields (field (name "Manufacturer Part") "CL31B104KBCNNNC") (field (name "Manufacturer") "SAMSUNG"))
      (libsource (lib "") (part "CL31B104KBCNNNC_1"))
    )
    (comp (ref "CN309")
      (value "SCSI Internal IDC50M")
      (fields (field (name "Manufacturer Part") "B-3000S50P-0110") (field (name "Manufacturer") "Ckmtw(灿科盟)"))
      (libsource (lib "") (part "300S-50P"))
    )
    (comp (ref "FB311A")
      (value "60Ω")
      (fields (field (name "Manufacturer Part") "CBG321609U600T") (field (name "Manufacturer") "FH"))
      (libsource (lib "") (part "MLB3216-601(f)_10"))
    )
    (comp (ref "FB311B")
      (value "60Ω")
      (fields (field (name "Manufacturer Part") "CBG321609U600T") (field (name "Manufacturer") "FH"))
      (libsource (lib "") (part "MLB3216-601(f)_3"))
    )
    (comp (ref "FB311C")
      (value "60Ω")
      (fields (field (name "Manufacturer Part") "CBG321609U600T") (field (name "Manufacturer") "FH"))
      (libsource (lib "") (part "MLB3216-601(f)_6"))
    )
    (comp (ref "FB311D")
      (value "60Ω")
      (fields (field (name "Manufacturer Part") "CBG321609U600T") (field (name "Manufacturer") "FH"))
      (libsource (lib "") (part "MLB3216-601(f)"))
    )
    (comp (ref "FB311E")
      (value "60Ω")
      (fields (field (name "Manufacturer Part") "CBG321609U600T") (field (name "Manufacturer") "FH"))
      (libsource (lib "") (part "MLB3216-601(f)_15"))
    )
    (comp (ref "FB311F")
      (value "60Ω")
      (fields (field (name "Manufacturer Part") "CBG321609U600T") (field (name "Manufacturer") "FH"))
      (libsource (lib "") (part "MLB3216-601(f)_16"))
    )
    (comp (ref "FB311G")
      (value "60Ω")
      (fields (field (name "Manufacturer Part") "CBG321609U600T") (field (name "Manufacturer") "FH"))
      (libsource (lib "") (part "MLB3216-601(f)_7"))
    )
    (comp (ref "FB311H")
      (value "60Ω")
      (fields (field (name "Manufacturer Part") "CBG321609U600T") (field (name "Manufacturer") "FH"))
      (libsource (lib "") (part "MLB3216-601(f)_2"))
    )
    (comp (ref "FB311I")
      (value "60Ω")
      (fields (field (name "Manufacturer Part") "CBG321609U600T") (field (name "Manufacturer") "FH"))
      (libsource (lib "") (part "MLB3216-601(f)_4"))
    )
    (comp (ref "FB311J")
      (value "60Ω")
      (fields (field (name "Manufacturer Part") "CBG321609U600T") (field (name "Manufacturer") "FH"))
      (libsource (lib "") (part "MLB3216-601(f)_14"))
    )
    (comp (ref "FB311K")
      (value "60Ω")
      (fields (field (name "Manufacturer Part") "CBG321609U600T") (field (name "Manufacturer") "FH"))
      (libsource (lib "") (part "MLB3216-601(f)_13"))
    )
    (comp (ref "FB311L")
      (value "60Ω")
      (fields (field (name "Manufacturer Part") "CBG321609U600T") (field (name "Manufacturer") "FH"))
      (libsource (lib "") (part "MLB3216-601(f)_1"))
    )
    (comp (ref "FB311M")
      (value "60Ω")
      (fields (field (name "Manufacturer Part") "CBG321609U600T") (field (name "Manufacturer") "FH"))
      (libsource (lib "") (part "MLB3216-601(f)_9"))
    )
    (comp (ref "FB311N")
      (value "60Ω")
      (fields (field (name "Manufacturer Part") "CBG321609U600T") (field (name "Manufacturer") "FH"))
      (libsource (lib "") (part "MLB3216-601(f)_12"))
    )
    (comp (ref "FB311O")
      (value "60Ω")
      (fields (field (name "Manufacturer Part") "CBG321609U600T") (field (name "Manufacturer") "FH"))
      (libsource (lib "") (part "MLB3216-601(f)_11"))
    )
    (comp (ref "FB311P")
      (value "60Ω")
      (fields (field (name "Manufacturer Part") "CBG321609U600T") (field (name "Manufacturer") "FH"))
      (libsource (lib "") (part "MLB3216-601(f)_5"))
    )
    (comp (ref "FB311Q")
      (value "60Ω")
      (fields (field (name "Manufacturer Part") "CBG321609U600T") (field (name "Manufacturer") "FH"))
      (libsource (lib "") (part "MLB3216-601(f)_8"))
    )
    (comp (ref "FB311R")
      (value "60Ω")
      (fields (field (name "Manufacturer Part") "CBG321609U600T") (field (name "Manufacturer") "FH"))
      (libsource (lib "") (part "MLB3216-601(f)_17"))
    )
    (comp (ref "R212A")
      (value "1K")
      (fields (field (name "Manufacturer Part") "1206W4F1001T5E") (field (name "Manufacturer") "UniOhm"))
      (libsource (lib "") (part "1206W4F1001T5E_1"))
    )
    (comp (ref "R212B")
      (value "1K")
      (fields (field (name "Manufacturer Part") "1206W4F1001T5E") (field (name "Manufacturer") "UniOhm"))
      (libsource (lib "") (part "1206W4F1001T5E_5"))
    )
    (comp (ref "R212C")
      (value "1K")
      (fields (field (name "Manufacturer Part") "1206W4F1001T5E") (field (name "Manufacturer") "UniOhm"))
      (libsource (lib "") (part "1206W4F1001T5E_2"))
    )
    (comp (ref "R212D")
      (value "1K")
      (fields (field (name "Manufacturer Part") "1206W4F1001T5E") (field (name "Manufacturer") "UniOhm"))
      (libsource (lib "") (part "1206W4F1001T5E_6"))
    )
    (comp (ref "R212E")
      (value "1K")
      (fields (field (name "Manufacturer Part") "1206W4F1001T5E") (field (name "Manufacturer") "UniOhm"))
      (libsource (lib "") (part "1206W4F1001T5E_7"))
    )
    (comp (ref "R212F")
      (value "1K")
      (fields (field (name "Manufacturer Part") "1206W4F1001T5E") (field (name "Manufacturer") "UniOhm"))
      (libsource (lib "") (part "1206W4F1001T5E"))
    )
    (comp (ref "R212G")
      (value "1K")
      (fields (field (name "Manufacturer Part") "1206W4F1001T5E") (field (name "Manufacturer") "UniOhm"))
      (libsource (lib "") (part "1206W4F1001T5E_4"))
    )
    (comp (ref "R212H")
      (value "1K")
      (fields (field (name "Manufacturer Part") "1206W4F1001T5E") (field (name "Manufacturer") "UniOhm"))
      (libsource (lib "") (part "1206W4F1001T5E_3"))
    )
    (comp (ref "SW1")
      (value "DSIC08LH-P")
      (fields (field (name "Manufacturer") "XKB Connectivity(中国星坤)"))
      (libsource (lib "") (part "DSIC08LH-P"))
    )
    (comp (ref "U213")
      (value "74F244")
      (fields (field (name "Manufacturer Part") "74F244SCX") (field (name "Manufacturer") "TI"))
      (libsource (lib "") (part "74F244SCX"))
    )
    (comp (ref "U310")
      (value "DS2107S")
      (fields (field (name "Manufacturer") "Dallas"))
      (libsource (lib "") (part "DS2107S"))
    )
    (comp (ref "U311")
      (value "DS2107S")
      (fields (field (name "Manufacturer") "Dallas"))
      (libsource (lib "") (part "DS2107S"))
    )
    (comp (ref "C1A")
      (value "100nF")
      (fields (field (name "Manufacturer Part") "CL31B104KBCNNNC") (field (name "Manufacturer") "SAMSUNG"))
      (libsource (lib "") (part "CL31B104KBCNNNC_2"))
    )
    (comp (ref "C1B")
      (value "47uF")
      (fields (field (name "Manufacturer Part") "RVT1V470M0605") (field (name "Manufacturer") "HONOR"))
      (libsource (lib "") (part "RVT1V470M0605"))
    )
    (comp (ref "C1C")
      (value "47uF")
      (fields (field (name "Manufacturer Part") "RVT1V470M0605") (field (name "Manufacturer") "HONOR"))
      (libsource (lib "") (part "RVT1V470M0605_1"))
    )
    (comp (ref "C10")
      (value "47uF")
      (fields (field (name "Manufacturer Part") "RVT1V470M0605") (field (name "Manufacturer") "HONOR"))
      (libsource (lib "") (part "RVT1V470M0605_3"))
    )
    (comp (ref "C11")
      (value "47uF")
      (fields (field (name "Manufacturer Part") "RVT1V470M0605") (field (name "Manufacturer") "HONOR"))
      (libsource (lib "") (part "RVT1V470M0605_3"))
    )
    (comp (ref "C12")
      (value "47uF")
      (fields (field (name "Manufacturer Part") "RVT1V470M0605") (field (name "Manufacturer") "HONOR"))
      (libsource (lib "") (part "RVT1V470M0605_3"))
    )
    (comp (ref "C13")
      (value "47uF")
      (fields (field (name "Manufacturer Part") "RVT1V470M0605") (field (name "Manufacturer") "HONOR"))
      (libsource (lib "") (part "RVT1V470M0605_2"))
    )
    (comp (ref "C100A")
      (value "100nF")
      (fields (field (name "Manufacturer Part") "CL31B104KBCNNNC") (field (name "Manufacturer") "SAMSUNG"))
      (libsource (lib "") (part "CL31B104KBCNNNC_14"))
    )
    (comp (ref "C101A")
      (value "100nF")
      (fields (field (name "Manufacturer Part") "CL31B104KBCNNNC") (field (name "Manufacturer") "SAMSUNG"))
      (libsource (lib "") (part "CL31B104KBCNNNC_17"))
    )
    (comp (ref "C102A")
      (value "100nF")
      (fields (field (name "Manufacturer Part") "CL31B104KBCNNNC") (field (name "Manufacturer") "SAMSUNG"))
      (libsource (lib "") (part "CL31B104KBCNNNC_1"))
    )
    (comp (ref "C103A")
      (value "100nF")
      (fields (field (name "Manufacturer Part") "CL31B104KBCNNNC") (field (name "Manufacturer") "SAMSUNG"))
      (libsource (lib "") (part "CL31B104KBCNNNC_18"))
    )
    (comp (ref "C105A")
      (value "100nF")
      (fields (field (name "Manufacturer Part") "CL31B104KBCNNNC") (field (name "Manufacturer") "SAMSUNG"))
      (libsource (lib "") (part "CL31B104KBCNNNC_5"))
    )
    (comp (ref "C106A")
      (value "100nF")
      (fields (field (name "Manufacturer Part") "CL31B104KBCNNNC") (field (name "Manufacturer") "SAMSUNG"))
      (libsource (lib "") (part "CL31B104KBCNNNC_9"))
    )
    (comp (ref "C107A")
      (value "100nF")
      (fields (field (name "Manufacturer Part") "CL31B104KBCNNNC") (field (name "Manufacturer") "SAMSUNG"))
      (libsource (lib "") (part "CL31B104KBCNNNC_12"))
    )
    (comp (ref "C108A")
      (value "100nF")
      (fields (field (name "Manufacturer Part") "CL31B104KBCNNNC") (field (name "Manufacturer") "SAMSUNG"))
      (libsource (lib "") (part "CL31B104KBCNNNC_13"))
    )
    (comp (ref "C109A")
      (value "100nF")
      (fields (field (name "Manufacturer Part") "CL31B104KBCNNNC") (field (name "Manufacturer") "SAMSUNG"))
      (libsource (lib "") (part "CL31B104KBCNNNC_4"))
    )
    (comp (ref "C200A")
      (value "100nF")
      (fields (field (name "Manufacturer Part") "CL31B104KBCNNNC") (field (name "Manufacturer") "SAMSUNG"))
      (libsource (lib "") (part "CL31B104KBCNNNC_15"))
    )
    (comp (ref "C201A")
      (value "100nF")
      (fields (field (name "Manufacturer Part") "CL31B104KBCNNNC") (field (name "Manufacturer") "SAMSUNG"))
      (libsource (lib "") (part "CL31B104KBCNNNC_10"))
    )
    (comp (ref "C202A")
      (value "100nF")
      (fields (field (name "Manufacturer Part") "CL31B104KBCNNNC") (field (name "Manufacturer") "SAMSUNG"))
      (libsource (lib "") (part "CL31B104KBCNNNC_21"))
    )
    (comp (ref "C203A")
      (value "100nF")
      (fields (field (name "Manufacturer Part") "CL31B104KBCNNNC") (field (name "Manufacturer") "SAMSUNG"))
      (libsource (lib "") (part "CL31B104KBCNNNC_8"))
    )
    (comp (ref "C205A")
      (value "100nF")
      (fields (field (name "Manufacturer Part") "CL31B104KBCNNNC") (field (name "Manufacturer") "SAMSUNG"))
      (libsource (lib "") (part "CL31B104KBCNNNC_16"))
    )
    (comp (ref "C206A")
      (value "100nF")
      (fields (field (name "Manufacturer Part") "CL31B104KBCNNNC") (field (name "Manufacturer") "SAMSUNG"))
      (libsource (lib "") (part "CL31B104KBCNNNC_7"))
    )
    (comp (ref "C207A")
      (value "100nF")
      (fields (field (name "Manufacturer Part") "CL31B104KBCNNNC") (field (name "Manufacturer") "SAMSUNG"))
      (libsource (lib "") (part "CL31B104KBCNNNC_6"))
    )
    (comp (ref "C212A")
      (value "100nF")
      (fields (field (name "Manufacturer Part") "CL31B104KBCNNNC") (field (name "Manufacturer") "SAMSUNG"))
      (libsource (lib "") (part "CL31B104KBCNNNC_3"))
    )
    (comp (ref "C303A")
      (value "100nF")
      (fields (field (name "Manufacturer Part") "CL31B104KBCNNNC") (field (name "Manufacturer") "SAMSUNG"))
      (libsource (lib "") (part "CL31B104KBCNNNC_20"))
    )
    (comp (ref "C304A")
      (value "100nF")
      (fields (field (name "Manufacturer Part") "CL31B104KBCNNNC") (field (name "Manufacturer") "SAMSUNG"))
      (libsource (lib "") (part "CL31B104KBCNNNC_22"))
    )
    (comp (ref "C305A")
      (value "100nF")
      (fields (field (name "Manufacturer Part") "CL31B104KBCNNNC") (field (name "Manufacturer") "SAMSUNG"))
      (libsource (lib "") (part "CL31B104KBCNNNC_19"))
    )
    (comp (ref "C306A")
      (value "100nF")
      (fields (field (name "Manufacturer Part") "CL31B104KBCNNNC") (field (name "Manufacturer") "SAMSUNG"))
      (libsource (lib "") (part "CL31B104KBCNNNC"))
    )
    (comp (ref "C307A")
      (value "100nF")
      (fields (field (name "Manufacturer Part") "CL31B104KBCNNNC") (field (name "Manufacturer") "SAMSUNG"))
      (libsource (lib "") (part "CL31B104KBCNNNC_11"))
    )
    (comp (ref "CN1")
      (value "TE 171826-4")
      (fields (field (name "Manufacturer Part") "171826-4") (field (name "Manufacturer") "TE Connectivity"))
      (libsource (lib "") (part "FLOPPY PWR TE 171826-4"))
    )
    (comp (ref "D309A")
      (value "TMBYV10")
      (fields (field (name "Manufacturer Part") "TMBYV10-40FILM") (field (name "Manufacturer") "ST(意法半导体)"))
      (libsource (lib "") (part "LL4007G L0"))
    )
    (comp (ref "F309B")
      (value "SMD Polyfuse 1.85A")
      (fields
        (field (name "Manufacturer Part") "SMD2920B185TF")
        (field (name "Manufacturer") "Brightking(君耀电子)")
      )
      (libsource (lib "") (part "A72-185-POLYFUSE-SMD"))
    )
    (comp (ref "FB500")
      (value "60Ω")
      (fields (field (name "Manufacturer Part") "CBG321609U600T") (field (name "Manufacturer") "FH"))
      (libsource (lib "") (part "MLB3216-601(f)_1"))
    )
    (comp (ref "FB501")
      (value "60Ω")
      (fields (field (name "Manufacturer Part") "CBG321609U600T") (field (name "Manufacturer") "FH"))
      (libsource (lib "") (part "MLB3216-601(f)"))
    )
    (comp (ref "FB504")
      (value "60Ω")
      (fields (field (name "Manufacturer Part") "CBG321609U600T") (field (name "Manufacturer") "FH"))
      (libsource (lib "") (part "MLB3216-601(f)"))
    )
    (comp (ref "FB505")
      (value "60Ω")
      (fields (field (name "Manufacturer Part") "CBG321609U600T") (field (name "Manufacturer") "FH"))
      (libsource (lib "") (part "MLB3216-601(f)"))
    )
    (comp (ref "U202")
      (value "GAL22V10H-15")
      (fields (field (name "Manufacturer Part") "GAL220V10") (field (name "Manufacturer") "Lattice"))
      (libsource (lib "") (part "GAL22V10"))
    )
    (comp (ref "U203")
      (value "GAL22V10H-15")
      (fields (field (name "Manufacturer Part") "GAL220V10") (field (name "Manufacturer") "Lattice"))
      (libsource (lib "") (part "GAL22V10"))
    )
    (comp (ref "U205")
      (value "GAL22V10H-15")
      (fields (field (name "Manufacturer Part") "GAL220V10") (field (name "Manufacturer") "Lattice"))
      (libsource (lib "") (part "GAL22V10"))
    )
    (comp (ref "U207")
      (value "GAL22V10H-15")
      (fields (field (name "Manufacturer Part") "GAL220V10") (field (name "Manufacturer") "Lattice"))
      (libsource (lib "") (part "GAL22V10"))
    )
    (comp (ref "U303")
      (value "GAL22V10H-15")
      (fields (field (name "Manufacturer Part") "GAL220V10") (field (name "Manufacturer") "Lattice"))
      (libsource (lib "") (part "GAL22V10"))
    )
    (comp (ref "U304")
      (value "GAL22V10B-10")
      (fields (field (name "Manufacturer Part") "GAL220V10") (field (name "Manufacturer") "Lattice"))
      (libsource (lib "") (part "GAL22V10"))
    )
    (comp (ref "U305")
      (value "GAL22V10B-10")
      (fields (field (name "Manufacturer Part") "GAL220V10") (field (name "Manufacturer") "Lattice"))
      (libsource (lib "") (part "GAL22V10"))
    )
    (comp (ref "U306")
      (value "GAL22V10B-10")
      (fields (field (name "Manufacturer Part") "GAL220V10") (field (name "Manufacturer") "Lattice"))
      (libsource (lib "") (part "GAL22V10"))
    )
  )
  (nets
    (net (code "1") (name "A0") (class "Default")
      (node (ref "R300K") (pin "1") (pinfunction "1_1") (pintype "input"))
      (node (ref "U300") (pin "144") (pinfunction "A0_144") (pintype "unspecified"))
      (node (ref "U304") (pin "26") (pinfunction "IOQ_26") (pintype "unspecified"))
      (node (ref "U305") (pin "16") (pinfunction "I_16") (pintype "unspecified"))
    )
    (net (code "2") (name "A1") (class "Default")
      (node (ref "R300L") (pin "1") (pinfunction "1_1") (pintype "input"))
      (node (ref "U300") (pin "145") (pinfunction "A1_145") (pintype "unspecified"))
      (node (ref "U304") (pin "27") (pinfunction "IOQ_27") (pintype "unspecified"))
      (node (ref "U305") (pin "13") (pinfunction "I_13") (pintype "unspecified"))
    )
    (net (code "3") (name "A2") (class "Default")
      (node (ref "R300I") (pin "1") (pinfunction "1_1") (pintype "input"))
      (node (ref "U103") (pin "7") (pinfunction "A5_7") (pintype "unspecified"))
      (node (ref "U202") (pin "7") (pinfunction "I_7") (pintype "unspecified"))
      (node (ref "U206") (pin "10") (pinfunction "A0_10") (pintype "input"))
      (node (ref "U300") (pin "146") (pinfunction "A2_146") (pintype "unspecified"))
    )
    (net (code "4") (name "A3") (class "Default")
      (node (ref "R300J") (pin "1") (pinfunction "1_1") (pintype "input"))
      (node (ref "U103") (pin "6") (pinfunction "A4_6") (pintype "unspecified"))
      (node (ref "U202") (pin "6") (pinfunction "I_6") (pintype "unspecified"))
      (node (ref "U206") (pin "9") (pinfunction "A1_9") (pintype "input"))
      (node (ref "U300") (pin "147") (pinfunction "A3_147") (pintype "unspecified"))
    )
    (net (code "5") (name "A3K-5V") (class "Default")
      (node (ref "CN352A") (pin "1") (pinfunction "1_1") (pintype "input"))
      (node (ref "CN352B") (pin "1") (pinfunction "1_1") (pintype "input"))
    )
    (net (code "6") (name "A3K-PWR") (class "Default")
      (node (ref "CN352A") (pin "3") (pinfunction "3_3") (pintype "input"))
      (node (ref "CN352B") (pin "3") (pinfunction "3_3") (pintype "input"))
    )
    (net (code "7") (name "A4") (class "Default")
      (node (ref "U103") (pin "5") (pinfunction "A3_5") (pintype "unspecified"))
      (node (ref "U202") (pin "5") (pinfunction "I_5") (pintype "unspecified"))
      (node (ref "U206") (pin "8") (pinfunction "A2_8") (pintype "input"))
      (node (ref "U300") (pin "148") (pinfunction "A4_148") (pintype "unspecified"))
    )
    (net (code "8") (name "A5") (class "Default")
      (node (ref "U103") (pin "4") (pinfunction "A2_4") (pintype "unspecified"))
      (node (ref "U202") (pin "4") (pinfunction "I_4") (pintype "unspecified"))
      (node (ref "U206") (pin "7") (pinfunction "A3_7") (pintype "input"))
      (node (ref "U300") (pin "150") (pinfunction "A5_150") (pintype "unspecified"))
    )
    (net (code "9") (name "A6") (class "Default")
      (node (ref "U103") (pin "3") (pinfunction "A1_3") (pintype "unspecified"))
      (node (ref "U202") (pin "3") (pinfunction "I_3") (pintype "unspecified"))
      (node (ref "U206") (pin "6") (pinfunction "A4_6") (pintype "input"))
      (node (ref "U300") (pin "151") (pinfunction "A6_151") (pintype "unspecified"))
    )
    (net (code "10") (name "A7") (class "Default")
      (node (ref "U103") (pin "2") (pinfunction "A0_2") (pintype "unspecified"))
      (node (ref "U206") (pin "5") (pinfunction "A5_5") (pintype "input"))
      (node (ref "U300") (pin "152") (pinfunction "A7_152") (pintype "unspecified"))
    )
    (net (code "11") (name "A8") (class "Default")
      (node (ref "U102") (pin "10") (pinfunction "A7_10") (pintype "bidirectional"))
      (node (ref "U202") (pin "9") (pinfunction "I_9") (pintype "unspecified"))
      (node (ref "U206") (pin "4") (pinfunction "A6_4") (pintype "input"))
      (node (ref "U300") (pin "154") (pinfunction "A8_154") (pintype "unspecified"))
    )
    (net (code "12") (name "A9") (class "Default")
      (node (ref "U102") (pin "9") (pinfunction "A6_9") (pintype "bidirectional"))
      (node (ref "U206") (pin "3") (pinfunction "A7_3") (pintype "input"))
      (node (ref "U300") (pin "155") (pinfunction "A9_155") (pintype "unspecified"))
    )
    (net (code "13") (name "A10") (class "Default")
      (node (ref "U102") (pin "8") (pinfunction "A5_8") (pintype "bidirectional"))
      (node (ref "U206") (pin "25") (pinfunction "A8_25") (pintype "output"))
      (node (ref "U300") (pin "157") (pinfunction "A10_157") (pintype "unspecified"))
    )
    (net (code "14") (name "A11") (class "Default")
      (node (ref "U102") (pin "7") (pinfunction "A4_7") (pintype "bidirectional"))
      (node (ref "U206") (pin "24") (pinfunction "A9_24") (pintype "output"))
      (node (ref "U300") (pin "158") (pinfunction "A11_158") (pintype "unspecified"))
    )
    (net (code "15") (name "A12") (class "Default")
      (node (ref "U102") (pin "6") (pinfunction "A3_6") (pintype "bidirectional"))
      (node (ref "U206") (pin "21") (pinfunction "A10_21") (pintype "output"))
      (node (ref "U300") (pin "159") (pinfunction "A12_159") (pintype "unspecified"))
    )
    (net (code "16") (name "A13") (class "Default")
      (node (ref "U102") (pin "5") (pinfunction "A2_5") (pintype "bidirectional"))
      (node (ref "U206") (pin "23") (pinfunction "A11_23") (pintype "output"))
      (node (ref "U300") (pin "160") (pinfunction "A13_160") (pintype "unspecified"))
    )
    (net (code "17") (name "A14") (class "Default")
      (node (ref "U102") (pin "4") (pinfunction "A1_4") (pintype "bidirectional"))
      (node (ref "U206") (pin "2") (pinfunction "A12_2") (pintype "input"))
      (node (ref "U300") (pin "1") (pinfunction "A14_1") (pintype "unspecified"))
    )
    (net (code "18") (name "A15") (class "Default")
      (node (ref "U102") (pin "3") (pinfunction "A0_3") (pintype "bidirectional"))
      (node (ref "U206") (pin "26") (pinfunction "A13_26") (pintype "output"))
      (node (ref "U300") (pin "3") (pinfunction "A15_3") (pintype "unspecified"))
    )
    (net (code "19") (name "A16") (class "Default")
      (node (ref "U101") (pin "10") (pinfunction "A7_10") (pintype "bidirectional"))
      (node (ref "U206") (pin "27") (pinfunction "A14_27") (pintype "output"))
      (node (ref "U300") (pin "4") (pinfunction "A16_4") (pintype "unspecified"))
    )
    (net (code "20") (name "A17") (class "Default")
      (node (ref "U101") (pin "9") (pinfunction "A6_9") (pintype "bidirectional"))
      (node (ref "U203") (pin "5") (pinfunction "I_5") (pintype "unspecified"))
      (node (ref "U206") (pin "1") (pinfunction "VPP_1") (pintype "input"))
      (node (ref "U300") (pin "5") (pinfunction "A17_5") (pintype "unspecified"))
    )
    (net (code "21") (name "A18") (class "Default")
      (node (ref "U101") (pin "8") (pinfunction "A5_8") (pintype "bidirectional"))
      (node (ref "U203") (pin "4") (pinfunction "I_4") (pintype "unspecified"))
      (node (ref "U300") (pin "7") (pinfunction "A18_7") (pintype "unspecified"))
    )
    (net (code "22") (name "A19") (class "Default")
      (node (ref "U101") (pin "7") (pinfunction "A4_7") (pintype "bidirectional"))
      (node (ref "U203") (pin "3") (pinfunction "I_3") (pintype "unspecified"))
      (node (ref "U300") (pin "8") (pinfunction "A19_8") (pintype "unspecified"))
    )
    (net (code "23") (name "A20") (class "Default")
      (node (ref "U101") (pin "6") (pinfunction "A3_6") (pintype "bidirectional"))
      (node (ref "U300") (pin "10") (pinfunction "A20_10") (pintype "unspecified"))
    )
    (net (code "24") (name "A21") (class "Default")
      (node (ref "U101") (pin "5") (pinfunction "A2_5") (pintype "bidirectional"))
      (node (ref "U300") (pin "11") (pinfunction "A21_11") (pintype "unspecified"))
    )
    (net (code "25") (name "A22") (class "Default")
      (node (ref "U101") (pin "4") (pinfunction "A1_4") (pintype "bidirectional"))
      (node (ref "U300") (pin "12") (pinfunction "A22_12") (pintype "unspecified"))
    )
    (net (code "26") (name "A23") (class "Default")
      (node (ref "U101") (pin "3") (pinfunction "A0_3") (pintype "bidirectional"))
      (node (ref "U203") (pin "2") (pinfunction "CLK/I_2") (pintype "unspecified"))
      (node (ref "U300") (pin "13") (pinfunction "A23_13") (pintype "unspecified"))
    )
    (net (code "27") (name "A24") (class "Default")
      (node (ref "U100") (pin "10") (pinfunction "A7_10") (pintype "bidirectional"))
      (node (ref "U201") (pin "17") (pinfunction "A7_17") (pintype "unspecified"))
      (node (ref "U300") (pin "14") (pinfunction "A24_14") (pintype "unspecified"))
    )
    (net (code "28") (name "A25") (class "Default")
      (node (ref "U100") (pin "9") (pinfunction "A6_9") (pintype "bidirectional"))
      (node (ref "U201") (pin "15") (pinfunction "A6_15") (pintype "unspecified"))
      (node (ref "U300") (pin "16") (pinfunction "A25_16") (pintype "unspecified"))
    )
    (net (code "29") (name "A26") (class "Default")
      (node (ref "U100") (pin "8") (pinfunction "A5_8") (pintype "bidirectional"))
      (node (ref "U201") (pin "13") (pinfunction "A5_13") (pintype "unspecified"))
      (node (ref "U300") (pin "17") (pinfunction "A26_17") (pintype "unspecified"))
    )
    (net (code "30") (name "A27") (class "Default")
      (node (ref "U100") (pin "7") (pinfunction "A4_7") (pintype "bidirectional"))
      (node (ref "U201") (pin "11") (pinfunction "A4_11") (pintype "unspecified"))
      (node (ref "U300") (pin "18") (pinfunction "A27_18") (pintype "unspecified"))
    )
    (net (code "31") (name "A28") (class "Default")
      (node (ref "U100") (pin "6") (pinfunction "A3_6") (pintype "bidirectional"))
      (node (ref "U201") (pin "8") (pinfunction "A3_8") (pintype "unspecified"))
      (node (ref "U300") (pin "20") (pinfunction "A28_20") (pintype "unspecified"))
    )
    (net (code "32") (name "A29") (class "Default")
      (node (ref "U100") (pin "5") (pinfunction "A2_5") (pintype "bidirectional"))
      (node (ref "U201") (pin "6") (pinfunction "A2_6") (pintype "unspecified"))
      (node (ref "U300") (pin "21") (pinfunction "A29_21") (pintype "unspecified"))
    )
    (net (code "33") (name "A30") (class "Default")
      (node (ref "U100") (pin "4") (pinfunction "A1_4") (pintype "bidirectional"))
      (node (ref "U201") (pin "4") (pinfunction "A1_4") (pintype "unspecified"))
      (node (ref "U300") (pin "23") (pinfunction "A30_23") (pintype "unspecified"))
    )
    (net (code "34") (name "A31") (class "Default")
      (node (ref "U100") (pin "3") (pinfunction "A0_3") (pintype "bidirectional"))
      (node (ref "U201") (pin "2") (pinfunction "A0_2") (pintype "unspecified"))
      (node (ref "U300") (pin "24") (pinfunction "A31_24") (pintype "unspecified"))
    )
    (net (code "35") (name "ABOEH") (class "Default")
      (node (ref "U100") (pin "13") (pinfunction "OEAB_13") (pintype "unspecified"))
      (node (ref "U100") (pin "2") (pinfunction "OEBA_2") (pintype "unspecified"))
      (node (ref "U101") (pin "13") (pinfunction "OEAB_13") (pintype "unspecified"))
      (node (ref "U101") (pin "2") (pinfunction "OEBA_2") (pintype "unspecified"))
      (node (ref "U102") (pin "13") (pinfunction "OEAB_13") (pintype "unspecified"))
      (node (ref "U102") (pin "2") (pinfunction "OEBA_2") (pintype "unspecified"))
      (node (ref "U205") (pin "27") (pinfunction "IOQ_27") (pintype "unspecified"))
      (node (ref "U306") (pin "10") (pinfunction "I_10") (pintype "unspecified"))
    )
    (net (code "36") (name "ABOEL") (class "Default")
      (node (ref "U103") (pin "19") (pinfunction "OE#_19") (pintype "unspecified"))
      (node (ref "U109") (pin "19") (pinfunction "OE#_19") (pintype "unspecified"))
      (node (ref "U205") (pin "26") (pinfunction "IOQ_26") (pintype "unspecified"))
    )
    (net (code "37") (name "BERR") (class "Default")
      (node (ref "R307B") (pin "2") (pinfunction "2_2") (pintype "input"))
      (node (ref "U202") (pin "17") (pinfunction "IOQ_17") (pintype "unspecified"))
      (node (ref "U300") (pin "37") (pinfunction "BERR/-TEA/_37") (pintype "unspecified"))
      (node (ref "U303") (pin "10") (pinfunction "I_10") (pintype "unspecified"))
      (node (ref "U306") (pin "11") (pinfunction "I_11") (pintype "unspecified"))
      (node (ref "U307") (pin "6") (pinfunction "3Y_6") (pintype "unspecified"))
    )
    (net (code "38") (name "BGACK") (class "Default")
      (node (ref "R300A") (pin "1") (pinfunction "1_1") (pintype "input"))
      (node (ref "U300") (pin "98") (pinfunction "BGACK/-BB/_98") (pintype "unspecified"))
    )
    (net (code "39") (name "BMASTER") (class "Default")
      (node (ref "U100") (pin "23") (pinfunction "CEBA_23") (pintype "unspecified"))
      (node (ref "U101") (pin "23") (pinfunction "CEBA_23") (pintype "unspecified"))
      (node (ref "U102") (pin "23") (pinfunction "CEBA_23") (pintype "unspecified"))
      (node (ref "U103") (pin "1") (pinfunction "T/R#_1") (pintype "unspecified"))
      (node (ref "U109") (pin "1") (pinfunction "T/R#_1") (pintype "unspecified"))
      (node (ref "U303") (pin "27") (pinfunction "IOQ_27") (pintype "unspecified"))
    )
    (net (code "40") (name "CBACK") (class "Default")
      (node (ref "R300B") (pin "2") (pinfunction "2_2") (pintype "input"))
      (node (ref "U300") (pin "35") (pinfunction "CBACK/-TBI/_35") (pintype "unspecified"))
      (node (ref "U306") (pin "27") (pinfunction "IOQ_27") (pintype "unspecified"))
    )
    (net (code "41") (name "CBREQ") (class "Default")
      (node (ref "R300C") (pin "1") (pinfunction "1_1") (pintype "input"))
      (node (ref "U300") (pin "33") (pinfunction "CBREQ/-TT1/_33") (pintype "unspecified"))
      (node (ref "U306") (pin "6") (pinfunction "I_6") (pintype "unspecified"))
    )
    (net (code "42") (name "CLK") (class "Default")
      (node (ref "R302B") (pin "1") (pinfunction "1_1") (pintype "input"))
      (node (ref "U205") (pin "2") (pinfunction "CLK/I_2") (pintype "unspecified"))
      (node (ref "U207") (pin "2") (pinfunction "CLK/I_2") (pintype "unspecified"))
      (node (ref "U300") (pin "41") (pinfunction "BCLK_41") (pintype "unspecified"))
      (node (ref "U303") (pin "12") (pinfunction "I_12") (pintype "unspecified"))
      (node (ref "U305") (pin "2") (pinfunction "CLK/I_2") (pintype "unspecified"))
    )
    (net (code "43") (name "CLKI") (class "Default")
      (node (ref "R302A") (pin "1") (pinfunction "1_1") (pintype "input"))
      (node (ref "U302") (pin "2") (pinfunction "D0_2") (pintype "unspecified"))
      (node (ref "U304") (pin "2") (pinfunction "CLK/I_2") (pintype "unspecified"))
      (node (ref "U306") (pin "2") (pinfunction "CLK/I_2") (pintype "unspecified"))
    )
    (net (code "44") (name "CLK_50M") (class "Default")
      (node (ref "R301A") (pin "1") (pinfunction "1_1") (pintype "input"))
      (node (ref "U300") (pin "102") (pinfunction "SCLK_102") (pintype "unspecified"))
      (node (ref "U302") (pin "3") (pinfunction "CP0_3") (pintype "unspecified"))
    )
    (net (code "45") (name "D0") (class "Default")
      (node (ref "U107") (pin "10") (pinfunction "A7_10") (pintype "bidirectional"))
      (node (ref "U213") (pin "3") (pinfunction "O4_3") (pintype "unspecified"))
      (node (ref "U300") (pin "85") (pinfunction "D0_85") (pintype "unspecified"))
    )
    (net (code "46") (name "D1") (class "Default")
      (node (ref "U107") (pin "9") (pinfunction "A6_9") (pintype "bidirectional"))
      (node (ref "U213") (pin "5") (pinfunction "O5_5") (pintype "unspecified"))
      (node (ref "U300") (pin "84") (pinfunction "D1_84") (pintype "unspecified"))
    )
    (net (code "47") (name "D2") (class "Default")
      (node (ref "U107") (pin "8") (pinfunction "A5_8") (pintype "bidirectional"))
      (node (ref "U213") (pin "7") (pinfunction "O6_7") (pintype "unspecified"))
      (node (ref "U300") (pin "83") (pinfunction "D2_83") (pintype "unspecified"))
    )
    (net (code "48") (name "D2Z") (class "Default")
      (node (ref "U105") (pin "11") (pinfunction "CEAB_11") (pintype "unspecified"))
      (node (ref "U106") (pin "11") (pinfunction "CEAB_11") (pintype "unspecified"))
      (node (ref "U107") (pin "11") (pinfunction "CEAB_11") (pintype "unspecified"))
      (node (ref "U108") (pin "11") (pinfunction "CEAB_11") (pintype "unspecified"))
      (node (ref "U205") (pin "21") (pinfunction "IOQ_21") (pintype "unspecified"))
    )
    (net (code "49") (name "D3") (class "Default")
      (node (ref "U107") (pin "7") (pinfunction "A4_7") (pintype "bidirectional"))
      (node (ref "U213") (pin "9") (pinfunction "O7_9") (pintype "unspecified"))
      (node (ref "U300") (pin "81") (pinfunction "D3_81") (pintype "unspecified"))
    )
    (net (code "50") (name "D4") (class "Default")
      (node (ref "U107") (pin "6") (pinfunction "A3_6") (pintype "bidirectional"))
      (node (ref "U213") (pin "12") (pinfunction "O3_12") (pintype "unspecified"))
      (node (ref "U300") (pin "80") (pinfunction "D4_80") (pintype "unspecified"))
    )
    (net (code "51") (name "D5") (class "Default")
      (node (ref "U107") (pin "5") (pinfunction "A2_5") (pintype "bidirectional"))
      (node (ref "U213") (pin "14") (pinfunction "O2_14") (pintype "unspecified"))
      (node (ref "U300") (pin "78") (pinfunction "D5_78") (pintype "unspecified"))
    )
    (net (code "52") (name "D6") (class "Default")
      (node (ref "U107") (pin "4") (pinfunction "A1_4") (pintype "bidirectional"))
      (node (ref "U213") (pin "16") (pinfunction "O1_16") (pintype "unspecified"))
      (node (ref "U300") (pin "77") (pinfunction "D6_77") (pintype "unspecified"))
    )
    (net (code "53") (name "D7") (class "Default")
      (node (ref "U107") (pin "3") (pinfunction "A0_3") (pintype "bidirectional"))
      (node (ref "U213") (pin "18") (pinfunction "O0_18") (pintype "unspecified"))
      (node (ref "U300") (pin "76") (pinfunction "D7_76") (pintype "unspecified"))
    )
    (net (code "54") (name "D8") (class "Default")
      (node (ref "U106") (pin "10") (pinfunction "A7_10") (pintype "bidirectional"))
      (node (ref "U300") (pin "73") (pinfunction "D8_73") (pintype "unspecified"))
    )
    (net (code "55") (name "D9") (class "Default")
      (node (ref "U106") (pin "9") (pinfunction "A6_9") (pintype "bidirectional"))
      (node (ref "U300") (pin "72") (pinfunction "D9_72") (pintype "unspecified"))
    )
    (net (code "56") (name "D10") (class "Default")
      (node (ref "U106") (pin "8") (pinfunction "A5_8") (pintype "bidirectional"))
      (node (ref "U300") (pin "71") (pinfunction "D10_71") (pintype "unspecified"))
    )
    (net (code "57") (name "D11") (class "Default")
      (node (ref "U106") (pin "7") (pinfunction "A4_7") (pintype "bidirectional"))
      (node (ref "U300") (pin "70") (pinfunction "D11_70") (pintype "unspecified"))
    )
    (net (code "58") (name "D12") (class "Default")
      (node (ref "U106") (pin "6") (pinfunction "A3_6") (pintype "bidirectional"))
      (node (ref "U206") (pin "11") (pinfunction "D0_11") (pintype "input"))
      (node (ref "U300") (pin "68") (pinfunction "D12_68") (pintype "unspecified"))
    )
    (net (code "59") (name "D13") (class "Default")
      (node (ref "U106") (pin "5") (pinfunction "A2_5") (pintype "bidirectional"))
      (node (ref "U206") (pin "12") (pinfunction "D1_12") (pintype "passive"))
      (node (ref "U300") (pin "67") (pinfunction "D13_67") (pintype "unspecified"))
    )
    (net (code "60") (name "D14") (class "Default")
      (node (ref "U106") (pin "4") (pinfunction "A1_4") (pintype "bidirectional"))
      (node (ref "U206") (pin "13") (pinfunction "D2_13") (pintype "input"))
      (node (ref "U300") (pin "66") (pinfunction "D14_66") (pintype "unspecified"))
    )
    (net (code "61") (name "D15") (class "Default")
      (node (ref "U106") (pin "3") (pinfunction "A0_3") (pintype "bidirectional"))
      (node (ref "U206") (pin "15") (pinfunction "D3_15") (pintype "output"))
      (node (ref "U300") (pin "65") (pinfunction "D15_65") (pintype "unspecified"))
    )
    (net (code "62") (name "D16") (class "Default")
      (node (ref "U108") (pin "3") (pinfunction "A0_3") (pintype "bidirectional"))
      (node (ref "U300") (pin "62") (pinfunction "D16_62") (pintype "unspecified"))
    )
    (net (code "63") (name "D17") (class "Default")
      (node (ref "U108") (pin "4") (pinfunction "A1_4") (pintype "bidirectional"))
      (node (ref "U300") (pin "60") (pinfunction "D17_60") (pintype "unspecified"))
    )
    (net (code "64") (name "D18") (class "Default")
      (node (ref "U108") (pin "5") (pinfunction "A2_5") (pintype "bidirectional"))
      (node (ref "U300") (pin "59") (pinfunction "D18_59") (pintype "unspecified"))
    )
    (net (code "65") (name "D19") (class "Default")
      (node (ref "U108") (pin "6") (pinfunction "A3_6") (pintype "bidirectional"))
      (node (ref "U300") (pin "58") (pinfunction "D19_58") (pintype "unspecified"))
    )
    (net (code "66") (name "D20") (class "Default")
      (node (ref "U108") (pin "7") (pinfunction "A4_7") (pintype "bidirectional"))
      (node (ref "U300") (pin "57") (pinfunction "D20_57") (pintype "unspecified"))
    )
    (net (code "67") (name "D21") (class "Default")
      (node (ref "U108") (pin "8") (pinfunction "A5_8") (pintype "bidirectional"))
      (node (ref "U300") (pin "56") (pinfunction "D21_56") (pintype "unspecified"))
    )
    (net (code "68") (name "D22") (class "Default")
      (node (ref "U108") (pin "9") (pinfunction "A6_9") (pintype "bidirectional"))
      (node (ref "U300") (pin "55") (pinfunction "D22_55") (pintype "unspecified"))
    )
    (net (code "69") (name "D23") (class "Default")
      (node (ref "U108") (pin "10") (pinfunction "A7_10") (pintype "bidirectional"))
      (node (ref "U300") (pin "53") (pinfunction "D23_53") (pintype "unspecified"))
    )
    (net (code "70") (name "D24") (class "Default")
      (node (ref "U105") (pin "3") (pinfunction "A0_3") (pintype "bidirectional"))
      (node (ref "U200") (pin "18") (pinfunction "D7_18") (pintype "unspecified"))
      (node (ref "U300") (pin "51") (pinfunction "D24_51") (pintype "unspecified"))
    )
    (net (code "71") (name "D25") (class "Default")
      (node (ref "U105") (pin "4") (pinfunction "A1_4") (pintype "bidirectional"))
      (node (ref "U200") (pin "17") (pinfunction "D6_17") (pintype "unspecified"))
      (node (ref "U300") (pin "50") (pinfunction "D25_50") (pintype "unspecified"))
    )
    (net (code "72") (name "D26") (class "Default")
      (node (ref "U105") (pin "5") (pinfunction "A2_5") (pintype "bidirectional"))
      (node (ref "U200") (pin "14") (pinfunction "D5_14") (pintype "unspecified"))
      (node (ref "U300") (pin "48") (pinfunction "D26_48") (pintype "unspecified"))
    )
    (net (code "73") (name "D27") (class "Default")
      (node (ref "U105") (pin "6") (pinfunction "A3_6") (pintype "bidirectional"))
      (node (ref "U200") (pin "13") (pinfunction "D4_13") (pintype "unspecified"))
      (node (ref "U300") (pin "47") (pinfunction "D27_47") (pintype "unspecified"))
    )
    (net (code "74") (name "D28") (class "Default")
      (node (ref "U105") (pin "7") (pinfunction "A4_7") (pintype "bidirectional"))
      (node (ref "U200") (pin "8") (pinfunction "D3_8") (pintype "unspecified"))
      (node (ref "U206") (pin "16") (pinfunction "D4_16") (pintype "output"))
      (node (ref "U300") (pin "45") (pinfunction "D28_45") (pintype "unspecified"))
    )
    (net (code "75") (name "D29") (class "Default")
      (node (ref "U105") (pin "8") (pinfunction "A5_8") (pintype "bidirectional"))
      (node (ref "U200") (pin "7") (pinfunction "D2_7") (pintype "unspecified"))
      (node (ref "U206") (pin "17") (pinfunction "D5_17") (pintype "output"))
      (node (ref "U300") (pin "44") (pinfunction "D29_44") (pintype "unspecified"))
    )
    (net (code "76") (name "D30") (class "Default")
      (node (ref "U105") (pin "9") (pinfunction "A6_9") (pintype "bidirectional"))
      (node (ref "U200") (pin "4") (pinfunction "D1_4") (pintype "unspecified"))
      (node (ref "U206") (pin "18") (pinfunction "D6_18") (pintype "output"))
      (node (ref "U300") (pin "43") (pinfunction "D30_43") (pintype "unspecified"))
    )
    (net (code "77") (name "D31") (class "Default")
      (node (ref "U105") (pin "10") (pinfunction "A7_10") (pintype "bidirectional"))
      (node (ref "U200") (pin "3") (pinfunction "D0_3") (pintype "unspecified"))
      (node (ref "U206") (pin "19") (pinfunction "D7_19") (pintype "output"))
      (node (ref "U300") (pin "42") (pinfunction "D31_42") (pintype "unspecified"))
    )
    (net (code "78") (name "DBLT") (class "Default")
      (node (ref "U105") (pin "1") (pinfunction "LEBA_1") (pintype "unspecified"))
      (node (ref "U105") (pin "14") (pinfunction "LEAB_14") (pintype "unspecified"))
      (node (ref "U106") (pin "1") (pinfunction "LEBA_1") (pintype "unspecified"))
      (node (ref "U106") (pin "14") (pinfunction "LEAB_14") (pintype "unspecified"))
      (node (ref "U107") (pin "1") (pinfunction "LEBA_1") (pintype "unspecified"))
      (node (ref "U107") (pin "14") (pinfunction "LEAB_14") (pintype "unspecified"))
      (node (ref "U108") (pin "1") (pinfunction "LEBA_1") (pintype "unspecified"))
      (node (ref "U108") (pin "14") (pinfunction "LEAB_14") (pintype "unspecified"))
      (node (ref "U205") (pin "24") (pinfunction "IOQ_24") (pintype "unspecified"))
    )
    (net (code "79") (name "DBOE") (class "Default")
      (node (ref "FB505") (pin "2") (pinfunction "2_2") (pintype "unspecified"))
      (node (ref "U105") (pin "13") (pinfunction "OEAB_13") (pintype "unspecified"))
      (node (ref "U105") (pin "2") (pinfunction "OEBA_2") (pintype "unspecified"))
      (node (ref "U106") (pin "13") (pinfunction "OEAB_13") (pintype "unspecified"))
      (node (ref "U106") (pin "2") (pinfunction "OEBA_2") (pintype "unspecified"))
      (node (ref "U107") (pin "13") (pinfunction "OEAB_13") (pintype "unspecified"))
      (node (ref "U107") (pin "2") (pinfunction "OEBA_2") (pintype "unspecified"))
      (node (ref "U108") (pin "13") (pinfunction "OEAB_13") (pintype "unspecified"))
      (node (ref "U108") (pin "2") (pinfunction "OEBA_2") (pintype "unspecified"))
    )
    (net (code "80") (name "DIP_EXT_TERM") (class "Default")
      (node (ref "R212G") (pin "2") (pinfunction "2_2") (pintype "input"))
      (node (ref "SW1") (pin "10") (pinfunction "PIN10_10") (pintype "unspecified"))
      (node (ref "U213") (pin "4") (pinfunction "I1_4") (pintype "unspecified"))
      (node (ref "U310") (pin "16") (pinfunction "PD#_16") (pintype "unspecified"))
      (node (ref "U311") (pin "16") (pinfunction "PD#_16") (pintype "unspecified"))
    )
    (net (code "81") (name "DIP_LONG_SPINUP") (class "Default")
      (node (ref "R212E") (pin "2") (pinfunction "2_2") (pintype "input"))
      (node (ref "SW1") (pin "12") (pinfunction "PIN12_12") (pintype "unspecified"))
      (node (ref "U213") (pin "8") (pinfunction "I3_8") (pintype "unspecified"))
    )
    (net (code "82") (name "DIP_SCSI_ADR0") (class "Default")
      (node (ref "R212A") (pin "2") (pinfunction "2_2") (pintype "input"))
      (node (ref "SW1") (pin "16") (pinfunction "PIN16_16") (pintype "unspecified"))
      (node (ref "U213") (pin "17") (pinfunction "I4_17") (pintype "unspecified"))
    )
    (net (code "83") (name "DIP_SCSI_ADR1") (class "Default")
      (node (ref "R212B") (pin "1") (pinfunction "1_1") (pintype "input"))
      (node (ref "SW1") (pin "15") (pinfunction "PIN15_15") (pintype "unspecified"))
      (node (ref "U213") (pin "15") (pinfunction "I5_15") (pintype "unspecified"))
    )
    (net (code "84") (name "DIP_SCSI_ADR2") (class "Default")
      (node (ref "R212C") (pin "1") (pinfunction "1_1") (pintype "input"))
      (node (ref "SW1") (pin "14") (pinfunction "PIN14_14") (pintype "unspecified"))
      (node (ref "U213") (pin "13") (pinfunction "I6_13") (pintype "unspecified"))
    )
    (net (code "85") (name "DIP_SCSI_FAST") (class "Default")
      (node (ref "R212D") (pin "1") (pinfunction "1_1") (pintype "input"))
      (node (ref "SW1") (pin "13") (pinfunction "PIN13_13") (pintype "unspecified"))
      (node (ref "U213") (pin "11") (pinfunction "I7_11") (pintype "unspecified"))
    )
    (net (code "86") (name "DIP_SCSI_LUNS") (class "Default")
      (node (ref "R212H") (pin "2") (pinfunction "2_2") (pintype "input"))
      (node (ref "SW1") (pin "9") (pinfunction "PIN9_9") (pintype "unspecified"))
      (node (ref "U213") (pin "2") (pinfunction "I0_2") (pintype "unspecified"))
    )
    (net (code "87") (name "DIP_SYNCH_MODE") (class "Default")
      (node (ref "R212F") (pin "2") (pinfunction "2_2") (pintype "input"))
      (node (ref "SW1") (pin "11") (pinfunction "PIN11_11") (pintype "unspecified"))
      (node (ref "U213") (pin "6") (pinfunction "I2_6") (pintype "unspecified"))
    )
    (net (code "88") (name "DP3_ABRT") (class "Default")
      (node (ref "R300P") (pin "1") (pinfunction "1_1") (pintype "input"))
      (node (ref "U300") (pin "52") (pinfunction "DP3_ABRT/_52") (pintype "unspecified"))
    )
    (net (code "89") (name "GND") (class "Default")
      (node (ref "C1") (pin "01") (pinfunction "GND_01") (pintype "bidirectional"))
      (node (ref "C1") (pin "02") (pinfunction "GND_02") (pintype "unspecified"))
      (node (ref "C1") (pin "03") (pinfunction "GND_03") (pintype "output"))
      (node (ref "C1") (pin "04") (pinfunction "GND_04") (pintype "bidirectional"))
      (node (ref "C1") (pin "100") (pinfunction "GND_100") (pintype "bidirectional"))
      (node (ref "C1") (pin "13") (pinfunction "GND_13") (pintype "bidirectional"))
      (node (ref "C1") (pin "25") (pinfunction "GND_25") (pintype "output"))
      (node (ref "C1") (pin "37") (pinfunction "GND_37") (pintype "unspecified"))
      (node (ref "C1") (pin "49") (pinfunction "GND_49") (pintype "unspecified"))
      (node (ref "C1") (pin "61") (pinfunction "GND_61") (pintype "bidirectional"))
      (node (ref "C1") (pin "73") (pinfunction "GND_73") (pintype "unspecified"))
      (node (ref "C1") (pin "85") (pinfunction "GND_85") (pintype "unspecified"))
      (node (ref "C1") (pin "87") (pinfunction "GND_87") (pintype "output"))
      (node (ref "C1") (pin "88") (pinfunction "GND_88") (pintype "bidirectional"))
      (node (ref "C1") (pin "89") (pinfunction "GND_89") (pintype "unspecified"))
      (node (ref "C1") (pin "90") (pinfunction "GND_90") (pintype "bidirectional"))
      (node (ref "C1") (pin "99") (pinfunction "GND_99") (pintype "bidirectional"))
      (node (ref "C10") (pin "2") (pinfunction "2_2") (pintype "input"))
      (node (ref "C100A") (pin "2") (pinfunction "2_2") (pintype "input"))
      (node (ref "C101A") (pin "2") (pinfunction "2_2") (pintype "input"))
      (node (ref "C102A") (pin "2") (pinfunction "2_2") (pintype "input"))
      (node (ref "C103A") (pin "2") (pinfunction "2_2") (pintype "input"))
      (node (ref "C105A") (pin "2") (pinfunction "2_2") (pintype "input"))
      (node (ref "C106A") (pin "1") (pinfunction "1_1") (pintype "input"))
      (node (ref "C107A") (pin "2") (pinfunction "2_2") (pintype "input"))
      (node (ref "C108A") (pin "2") (pinfunction "2_2") (pintype "input"))
      (node (ref "C109A") (pin "2") (pinfunction "2_2") (pintype "input"))
      (node (ref "C11") (pin "2") (pinfunction "2_2") (pintype "input"))
      (node (ref "C12") (pin "2") (pinfunction "2_2") (pintype "input"))
      (node (ref "C13") (pin "2") (pinfunction "2_2") (pintype "input"))
      (node (ref "C1A") (pin "1") (pinfunction "1_1") (pintype "input"))
      (node (ref "C1B") (pin "2") (pinfunction "2_2") (pintype "input"))
      (node (ref "C1C") (pin "2") (pinfunction "2_2") (pintype "input"))
      (node (ref "C200A") (pin "1") (pinfunction "1_1") (pintype "input"))
      (node (ref "C201A") (pin "2") (pinfunction "2_2") (pintype "input"))
      (node (ref "C202A") (pin "2") (pinfunction "2_2") (pintype "input"))
      (node (ref "C203A") (pin "2") (pinfunction "2_2") (pintype "input"))
      (node (ref "C205A") (pin "2") (pinfunction "2_2") (pintype "input"))
      (node (ref "C206A") (pin "1") (pinfunction "1_1") (pintype "input"))
      (node (ref "C207A") (pin "2") (pinfunction "2_2") (pintype "input"))
      (node (ref "C212A") (pin "2") (pinfunction "2_2") (pintype "input"))
      (node (ref "C300A") (pin "2") (pinfunction "2_2") (pintype "input"))
      (node (ref "C300B") (pin "2") (pinfunction "2_2") (pintype "input"))
      (node (ref "C300C") (pin "2") (pinfunction "2_2") (pintype "input"))
      (node (ref "C300D") (pin "1") (pinfunction "1_1") (pintype "input"))
      (node (ref "C300E") (pin "2") (pinfunction "2_2") (pintype "input"))
      (node (ref "C300F") (pin "2") (pinfunction "2_2") (pintype "input"))
      (node (ref "C300G") (pin "2") (pinfunction "2_2") (pintype "input"))
      (node (ref "C300H") (pin "1") (pinfunction "1_1") (pintype "input"))
      (node (ref "C300I") (pin "2") (pinfunction "2_2") (pintype "input"))
      (node (ref "C301A") (pin "1") (pinfunction "1_1") (pintype "input"))
      (node (ref "C302A") (pin "2") (pinfunction "2_2") (pintype "input"))
      (node (ref "C303A") (pin "1") (pinfunction "1_1") (pintype "input"))
      (node (ref "C304A") (pin "2") (pinfunction "2_2") (pintype "input"))
      (node (ref "C305A") (pin "2") (pinfunction "2_2") (pintype "input"))
      (node (ref "C306A") (pin "2") (pinfunction "2_2") (pintype "input"))
      (node (ref "C306B") (pin "2") (pinfunction "2_2") (pintype "input"))
      (node (ref "C307A") (pin "1") (pinfunction "1_1") (pintype "input"))
      (node (ref "C350A") (pin "2") (pinfunction "2_2") (pintype "unspecified"))
      (node (ref "C350B") (pin "1") (pinfunction "1_1") (pintype "input"))
      (node (ref "C351A") (pin "2") (pinfunction "2_2") (pintype "unspecified"))
      (node (ref "C351B") (pin "2") (pinfunction "2_2") (pintype "input"))
      (node (ref "CN1") (pin "2") (pinfunction "GND_2") (pintype "unspecified"))
      (node (ref "CN1") (pin "3") (pinfunction "GND_3") (pintype "unspecified"))
      (node (ref "CN309") (pin "1") (pinfunction "1_1") (pintype "unspecified"))
      (node (ref "CN309") (pin "11") (pinfunction "11_11") (pintype "unspecified"))
      (node (ref "CN309") (pin "13") (pinfunction "13_13") (pintype "unspecified"))
      (node (ref "CN309") (pin "15") (pinfunction "15_15") (pintype "unspecified"))
      (node (ref "CN309") (pin "17") (pinfunction "17_17") (pintype "unspecified"))
      (node (ref "CN309") (pin "19") (pinfunction "19_19") (pintype "unspecified"))
      (node (ref "CN309") (pin "20") (pinfunction "20_20") (pintype "unspecified"))
      (node (ref "CN309") (pin "21") (pinfunction "21_21") (pintype "unspecified"))
      (node (ref "CN309") (pin "22") (pinfunction "22_22") (pintype "unspecified"))
      (node (ref "CN309") (pin "23") (pinfunction "23_23") (pintype "unspecified"))
      (node (ref "CN309") (pin "24") (pinfunction "24_24") (pintype "unspecified"))
      (node (ref "CN309") (pin "27") (pinfunction "27_27") (pintype "unspecified"))
      (node (ref "CN309") (pin "28") (pinfunction "28_28") (pintype "unspecified"))
      (node (ref "CN309") (pin "29") (pinfunction "29_29") (pintype "unspecified"))
      (node (ref "CN309") (pin "3") (pinfunction "3_3") (pintype "unspecified"))
      (node (ref "CN309") (pin "30") (pinfunction "30_30") (pintype "unspecified"))
      (node (ref "CN309") (pin "31") (pinfunction "31_31") (pintype "unspecified"))
      (node (ref "CN309") (pin "33") (pinfunction "33_33") (pintype "unspecified"))
      (node (ref "CN309") (pin "35") (pinfunction "35_35") (pintype "unspecified"))
      (node (ref "CN309") (pin "37") (pinfunction "37_37") (pintype "unspecified"))
      (node (ref "CN309") (pin "39") (pinfunction "39_39") (pintype "unspecified"))
      (node (ref "CN309") (pin "41") (pinfunction "41_41") (pintype "unspecified"))
      (node (ref "CN309") (pin "43") (pinfunction "43_43") (pintype "unspecified"))
      (node (ref "CN309") (pin "45") (pinfunction "45_45") (pintype "unspecified"))
      (node (ref "CN309") (pin "47") (pinfunction "47_47") (pintype "unspecified"))
      (node (ref "CN309") (pin "49") (pinfunction "49_49") (pintype "unspecified"))
      (node (ref "CN309") (pin "5") (pinfunction "5_5") (pintype "unspecified"))
      (node (ref "CN309") (pin "7") (pinfunction "7_7") (pintype "unspecified"))
      (node (ref "CN309") (pin "9") (pinfunction "9_9") (pintype "unspecified"))
      (node (ref "R109H") (pin "1") (pinfunction "1_1") (pintype "input"))
      (node (ref "SW1") (pin "1") (pinfunction "PIN1_1") (pintype "unspecified"))
      (node (ref "SW1") (pin "2") (pinfunction "PIN2_2") (pintype "unspecified"))
      (node (ref "SW1") (pin "3") (pinfunction "PIN3_3") (pintype "unspecified"))
      (node (ref "SW1") (pin "4") (pinfunction "PIN4_4") (pintype "unspecified"))
      (node (ref "SW1") (pin "5") (pinfunction "PIN5_5") (pintype "unspecified"))
      (node (ref "SW1") (pin "6") (pinfunction "PIN6_6") (pintype "unspecified"))
      (node (ref "SW1") (pin "7") (pinfunction "PIN7_7") (pintype "unspecified"))
      (node (ref "SW1") (pin "8") (pinfunction "PIN8_8") (pintype "unspecified"))
      (node (ref "U100") (pin "12") (pinfunction "GND_12") (pintype "passive"))
      (node (ref "U100") (pin "14") (pinfunction "LEAB_14") (pintype "unspecified"))
      (node (ref "U101") (pin "12") (pinfunction "GND_12") (pintype "passive"))
      (node (ref "U101") (pin "14") (pinfunction "LEAB_14") (pintype "unspecified"))
      (node (ref "U102") (pin "12") (pinfunction "GND_12") (pintype "passive"))
      (node (ref "U102") (pin "14") (pinfunction "LEAB_14") (pintype "unspecified"))
      (node (ref "U103") (pin "10") (pinfunction "GND_10") (pintype "unspecified"))
      (node (ref "U105") (pin "12") (pinfunction "GND_12") (pintype "passive"))
      (node (ref "U106") (pin "12") (pinfunction "GND_12") (pintype "passive"))
      (node (ref "U107") (pin "12") (pinfunction "GND_12") (pintype "passive"))
      (node (ref "U108") (pin "12") (pinfunction "GND_12") (pintype "passive"))
      (node (ref "U109") (pin "10") (pinfunction "GND_10") (pintype "unspecified"))
      (node (ref "U200") (pin "10") (pinfunction "GND_10") (pintype "unspecified"))
      (node (ref "U201") (pin "1") (pinfunction "IA=B_1") (pintype "unspecified"))
      (node (ref "U201") (pin "10") (pinfunction "GND_10") (pintype "unspecified"))
      (node (ref "U202") (pin "14") (pinfunction "GND_14") (pintype "unspecified"))
      (node (ref "U202") (pin "15") (pinfunction "NC_15") (pintype "unspecified"))
      (node (ref "U202") (pin "22") (pinfunction "NC_22") (pintype "unspecified"))
      (node (ref "U202") (pin "8") (pinfunction "NC_8") (pintype "unspecified"))
      (node (ref "U203") (pin "14") (pinfunction "GND_14") (pintype "unspecified"))
      (node (ref "U203") (pin "15") (pinfunction "NC_15") (pintype "unspecified"))
      (node (ref "U203") (pin "22") (pinfunction "NC_22") (pintype "unspecified"))
      (node (ref "U203") (pin "8") (pinfunction "NC_8") (pintype "unspecified"))
      (node (ref "U205") (pin "14") (pinfunction "GND_14") (pintype "unspecified"))
      (node (ref "U205") (pin "15") (pinfunction "NC_15") (pintype "unspecified"))
      (node (ref "U205") (pin "22") (pinfunction "NC_22") (pintype "unspecified"))
      (node (ref "U205") (pin "8") (pinfunction "NC_8") (pintype "unspecified"))
      (node (ref "U206") (pin "14") (pinfunction "GND_14") (pintype "output"))
      (node (ref "U206") (pin "20") (pinfunction "CE#_20") (pintype "output"))
      (node (ref "U207") (pin "14") (pinfunction "GND_14") (pintype "unspecified"))
      (node (ref "U207") (pin "15") (pinfunction "NC_15") (pintype "unspecified"))
      (node (ref "U207") (pin "22") (pinfunction "NC_22") (pintype "unspecified"))
      (node (ref "U207") (pin "8") (pinfunction "NC_8") (pintype "unspecified"))
      (node (ref "U213") (pin "10") (pinfunction "GND_10") (pintype "unspecified"))
      (node (ref "U300") (pin "109") (pinfunction "Vss_109") (pintype "unspecified"))
      (node (ref "U300") (pin "113") (pinfunction "Vss_113") (pintype "unspecified"))
      (node (ref "U300") (pin "118") (pinfunction "Vss_118") (pintype "unspecified"))
      (node (ref "U300") (pin "123") (pinfunction "Vss_123") (pintype "unspecified"))
      (node (ref "U300") (pin "128") (pinfunction "Vss_128") (pintype "unspecified"))
      (node (ref "U300") (pin "136") (pinfunction "Vss_136") (pintype "unspecified"))
      (node (ref "U300") (pin "143") (pinfunction "Vss_143") (pintype "unspecified"))
      (node (ref "U300") (pin "149") (pinfunction "Vss_149") (pintype "unspecified"))
      (node (ref "U300") (pin "15") (pinfunction "Vss_15") (pintype "unspecified"))
      (node (ref "U300") (pin "156") (pinfunction "Vss_156") (pintype "unspecified"))
      (node (ref "U300") (pin "2") (pinfunction "Vss_2") (pintype "unspecified"))
      (node (ref "U300") (pin "22") (pinfunction "Vss_22") (pintype "unspecified"))
      (node (ref "U300") (pin "31") (pinfunction "Vss_31") (pintype "unspecified"))
      (node (ref "U300") (pin "46") (pinfunction "Vss_46") (pintype "unspecified"))
      (node (ref "U300") (pin "54") (pinfunction "Vss_54") (pintype "unspecified"))
      (node (ref "U300") (pin "61") (pinfunction "Vss_61") (pintype "unspecified"))
      (node (ref "U300") (pin "69") (pinfunction "Vss_69") (pintype "unspecified"))
      (node (ref "U300") (pin "75") (pinfunction "Vss_75") (pintype "unspecified"))
      (node (ref "U300") (pin "82") (pinfunction "Vss_82") (pintype "unspecified"))
      (node (ref "U300") (pin "9") (pinfunction "Vss_9") (pintype "unspecified"))
      (node (ref "U300") (pin "96") (pinfunction "Vss_96") (pintype "unspecified"))
      (node (ref "U301") (pin "2") (pinfunction "GND_2") (pintype "unspecified"))
      (node (ref "U302") (pin "7") (pinfunction "GND_7") (pintype "unspecified"))
      (node (ref "U303") (pin "14") (pinfunction "GND_14") (pintype "unspecified"))
      (node (ref "U303") (pin "15") (pinfunction "NC_15") (pintype "unspecified"))
      (node (ref "U303") (pin "22") (pinfunction "NC_22") (pintype "unspecified"))
      (node (ref "U303") (pin "8") (pinfunction "NC_8") (pintype "unspecified"))
      (node (ref "U304") (pin "14") (pinfunction "GND_14") (pintype "unspecified"))
      (node (ref "U304") (pin "15") (pinfunction "NC_15") (pintype "unspecified"))
      (node (ref "U304") (pin "22") (pinfunction "NC_22") (pintype "unspecified"))
      (node (ref "U304") (pin "8") (pinfunction "NC_8") (pintype "unspecified"))
      (node (ref "U305") (pin "14") (pinfunction "GND_14") (pintype "unspecified"))
      (node (ref "U305") (pin "15") (pinfunction "NC_15") (pintype "unspecified"))
      (node (ref "U305") (pin "22") (pinfunction "NC_22") (pintype "unspecified"))
      (node (ref "U305") (pin "8") (pinfunction "NC_8") (pintype "unspecified"))
      (node (ref "U306") (pin "14") (pinfunction "GND_14") (pintype "unspecified"))
      (node (ref "U306") (pin "15") (pinfunction "NC_15") (pintype "unspecified"))
      (node (ref "U306") (pin "22") (pinfunction "NC_22") (pintype "unspecified"))
      (node (ref "U306") (pin "8") (pinfunction "NC_8") (pintype "unspecified"))
      (node (ref "U307") (pin "11") (pinfunction "5A_11") (pintype "unspecified"))
      (node (ref "U307") (pin "13") (pinfunction "6A_13") (pintype "unspecified"))
      (node (ref "U307") (pin "7") (pinfunction "GND_7") (pintype "unspecified"))
      (node (ref "U310") (pin "8") (pinfunction "GND_8") (pintype "passive"))
      (node (ref "U311") (pin "8") (pinfunction "GND_8") (pintype "passive"))
    )
    (net (code "90") (name "IORST") (class "Default")
      (node (ref "R307A") (pin "1") (pinfunction "1_1") (pintype "input"))
      (node (ref "U202") (pin "19") (pinfunction "IOQ_19") (pintype "unspecified"))
      (node (ref "U203") (pin "27") (pinfunction "IOQ_27") (pintype "unspecified"))
      (node (ref "U207") (pin "9") (pinfunction "I_9") (pintype "unspecified"))
      (node (ref "U300") (pin "94") (pinfunction "RESET/_94") (pintype "unspecified"))
      (node (ref "U303") (pin "11") (pinfunction "I_11") (pintype "unspecified"))
      (node (ref "U306") (pin "12") (pinfunction "I_12") (pintype "unspecified"))
      (node (ref "U307") (pin "8") (pinfunction "4Y_8") (pintype "unspecified"))
    )
    (net (code "91") (name "LED") (class "Default")
      (node (ref "R398") (pin "2") (pinfunction "2_2") (pintype "unspecified"))
      (node (ref "U307") (pin "2") (pinfunction "1Y_2") (pintype "unspecified"))
      (node (ref "U307") (pin "4") (pinfunction "2Y_4") (pintype "unspecified"))
    )
    (net (code "92") (name "LEDR") (class "Default")
      (node (ref "CN308") (pin "1") (pinfunction "1_1") (pintype "input"))
      (node (ref "CN308") (pin "3") (pinfunction "3_3") (pintype "input"))
      (node (ref "CN351") (pin "1") (pinfunction "1_1") (pintype "input"))
      (node (ref "CN351") (pin "3") (pinfunction "3_3") (pintype "input"))
      (node (ref "CN352A") (pin "2") (pinfunction "2_2") (pintype "input"))
      (node (ref "CN352B") (pin "2") (pinfunction "2_2") (pintype "input"))
      (node (ref "R398") (pin "1") (pinfunction "1_1") (pintype "unspecified"))
    )
    (net (code "93") (name "M24") (class "Default")
      (node (ref "R200H") (pin "1") (pinfunction "1_1") (pintype "input"))
      (node (ref "U200") (pin "19") (pinfunction "Q7_19") (pintype "unspecified"))
      (node (ref "U201") (pin "18") (pinfunction "B7_18") (pintype "unspecified"))
    )
    (net (code "94") (name "M25") (class "Default")
      (node (ref "R200G") (pin "1") (pinfunction "1_1") (pintype "input"))
      (node (ref "U200") (pin "16") (pinfunction "Q6_16") (pintype "unspecified"))
      (node (ref "U201") (pin "16") (pinfunction "B6_16") (pintype "unspecified"))
    )
    (net (code "95") (name "M26") (class "Default")
      (node (ref "R200F") (pin "1") (pinfunction "1_1") (pintype "input"))
      (node (ref "U200") (pin "15") (pinfunction "Q5_15") (pintype "unspecified"))
      (node (ref "U201") (pin "14") (pinfunction "B5_14") (pintype "unspecified"))
    )
    (net (code "96") (name "M27") (class "Default")
      (node (ref "R200E") (pin "1") (pinfunction "1_1") (pintype "input"))
      (node (ref "U200") (pin "12") (pinfunction "Q4_12") (pintype "unspecified"))
      (node (ref "U201") (pin "12") (pinfunction "B4_12") (pintype "unspecified"))
    )
    (net (code "97") (name "M28") (class "Default")
      (node (ref "R200D") (pin "1") (pinfunction "1_1") (pintype "input"))
      (node (ref "U200") (pin "9") (pinfunction "Q3_9") (pintype "unspecified"))
      (node (ref "U201") (pin "9") (pinfunction "B3_9") (pintype "unspecified"))
    )
    (net (code "98") (name "M29") (class "Default")
      (node (ref "R200C") (pin "1") (pinfunction "1_1") (pintype "input"))
      (node (ref "U200") (pin "6") (pinfunction "Q2_6") (pintype "unspecified"))
      (node (ref "U201") (pin "7") (pinfunction "B2_7") (pintype "unspecified"))
    )
    (net (code "99") (name "M30") (class "Default")
      (node (ref "R200B") (pin "1") (pinfunction "1_1") (pintype "input"))
      (node (ref "U200") (pin "5") (pinfunction "Q1_5") (pintype "unspecified"))
      (node (ref "U201") (pin "5") (pinfunction "B1_5") (pintype "unspecified"))
    )
    (net (code "100") (name "M31") (class "Default")
      (node (ref "R200A") (pin "1") (pinfunction "1_1") (pintype "input"))
      (node (ref "U200") (pin "2") (pinfunction "Q0_2") (pintype "unspecified"))
      (node (ref "U201") (pin "3") (pinfunction "B0_3") (pintype "unspecified"))
    )
    (net (code "101") (name "MASTER") (class "Default")
      (node (ref "FB502") (pin "1") (pinfunction "1_1") (pintype "unspecified"))
      (node (ref "U100") (pin "11") (pinfunction "CEAB_11") (pintype "unspecified"))
      (node (ref "U101") (pin "11") (pinfunction "CEAB_11") (pintype "unspecified"))
      (node (ref "U102") (pin "11") (pinfunction "CEAB_11") (pintype "unspecified"))
      (node (ref "U205") (pin "18") (pinfunction "IOQ_18") (pintype "unspecified"))
      (node (ref "U303") (pin "3") (pinfunction "I_3") (pintype "unspecified"))
    )
    (net (code "102") (name "MATCH") (class "Default")
      (node (ref "U201") (pin "19") (pinfunction "OA=B_19") (pintype "unspecified"))
      (node (ref "U202") (pin "2") (pinfunction "CLK/I_2") (pintype "unspecified"))
    )
    (net (code "103") (name "NCR_INT") (class "Default")
      (node (ref "U207") (pin "10") (pinfunction "I_10") (pintype "unspecified"))
      (node (ref "U300") (pin "105") (pinfunction "IRQ/_105") (pintype "unspecified"))
    )
    (net (code "104") (name "Net-(CN309-Pad2)") (class "Default")
      (node (ref "CN309") (pin "2") (pinfunction "2_2") (pintype "unspecified"))
      (node (ref "FB311A") (pin "1") (pinfunction "1_1") (pintype "unspecified"))
    )
    (net (code "105") (name "Net-(CN309-Pad4)") (class "Default")
      (node (ref "CN309") (pin "4") (pinfunction "4_4") (pintype "unspecified"))
      (node (ref "FB311B") (pin "1") (pinfunction "1_1") (pintype "unspecified"))
    )
    (net (code "106") (name "Net-(CN309-Pad6)") (class "Default")
      (node (ref "CN309") (pin "6") (pinfunction "6_6") (pintype "unspecified"))
      (node (ref "FB311C") (pin "1") (pinfunction "1_1") (pintype "unspecified"))
    )
    (net (code "107") (name "Net-(CN309-Pad8)") (class "Default")
      (node (ref "CN309") (pin "8") (pinfunction "8_8") (pintype "unspecified"))
      (node (ref "FB311D") (pin "1") (pinfunction "1_1") (pintype "unspecified"))
    )
    (net (code "108") (name "Net-(CN309-Pad10)") (class "Default")
      (node (ref "CN309") (pin "10") (pinfunction "10_10") (pintype "unspecified"))
      (node (ref "FB311E") (pin "1") (pinfunction "1_1") (pintype "unspecified"))
    )
    (net (code "109") (name "Net-(CN309-Pad12)") (class "Default")
      (node (ref "CN309") (pin "12") (pinfunction "12_12") (pintype "unspecified"))
      (node (ref "FB311F") (pin "1") (pinfunction "1_1") (pintype "unspecified"))
    )
    (net (code "110") (name "Net-(CN309-Pad14)") (class "Default")
      (node (ref "CN309") (pin "14") (pinfunction "14_14") (pintype "unspecified"))
      (node (ref "FB311G") (pin "1") (pinfunction "1_1") (pintype "unspecified"))
    )
    (net (code "111") (name "Net-(CN309-Pad16)") (class "Default")
      (node (ref "CN309") (pin "16") (pinfunction "16_16") (pintype "unspecified"))
      (node (ref "FB311H") (pin "1") (pinfunction "1_1") (pintype "unspecified"))
    )
    (net (code "112") (name "Net-(CN309-Pad18)") (class "Default")
      (node (ref "CN309") (pin "18") (pinfunction "18_18") (pintype "unspecified"))
      (node (ref "FB311I") (pin "1") (pinfunction "1_1") (pintype "unspecified"))
    )
    (net (code "113") (name "Net-(CN309-Pad32)") (class "Default")
      (node (ref "CN309") (pin "32") (pinfunction "32_32") (pintype "unspecified"))
      (node (ref "FB311J") (pin "1") (pinfunction "1_1") (pintype "unspecified"))
    )
    (net (code "114") (name "Net-(CN309-Pad38)") (class "Default")
      (node (ref "CN309") (pin "38") (pinfunction "38_38") (pintype "unspecified"))
      (node (ref "FB311Q") (pin "1") (pinfunction "1_1") (pintype "unspecified"))
    )
    (net (code "115") (name "Net-(CN309-Pad40)") (class "Default")
      (node (ref "CN309") (pin "40") (pinfunction "40_40") (pintype "unspecified"))
      (node (ref "FB311P") (pin "1") (pinfunction "1_1") (pintype "unspecified"))
    )
    (net (code "116") (name "Net-(CN309-Pad42)") (class "Default")
      (node (ref "CN309") (pin "42") (pinfunction "42_42") (pintype "unspecified"))
      (node (ref "FB311O") (pin "1") (pinfunction "1_1") (pintype "unspecified"))
    )
    (net (code "117") (name "Net-(CN309-Pad44)") (class "Default")
      (node (ref "CN309") (pin "44") (pinfunction "44_44") (pintype "unspecified"))
      (node (ref "FB311N") (pin "1") (pinfunction "1_1") (pintype "unspecified"))
    )
    (net (code "118") (name "Net-(CN309-Pad46)") (class "Default")
      (node (ref "CN309") (pin "46") (pinfunction "46_46") (pintype "unspecified"))
      (node (ref "FB311M") (pin "1") (pinfunction "1_1") (pintype "unspecified"))
    )
    (net (code "119") (name "Net-(CN309-Pad48)") (class "Default")
      (node (ref "CN309") (pin "48") (pinfunction "48_48") (pintype "unspecified"))
      (node (ref "FB311L") (pin "1") (pinfunction "1_1") (pintype "unspecified"))
    )
    (net (code "120") (name "Net-(CN309-Pad50)") (class "Default")
      (node (ref "CN309") (pin "50") (pinfunction "50_50") (pintype "unspecified"))
      (node (ref "FB311K") (pin "1") (pinfunction "1_1") (pintype "unspecified"))
    )
    (net (code "121") (name "Net-(D309A-C)") (class "Default")
      (node (ref "D309A") (pin "1") (pinfunction "C_1") (pintype "unspecified"))
      (node (ref "F309B") (pin "1") (pinfunction "1_1") (pintype "unspecified"))
    )
    (net (code "122") (name "Net-(FB500-Pad1)") (class "Default")
      (node (ref "FB500") (pin "1") (pinfunction "1_1") (pintype "unspecified"))
      (node (ref "U305") (pin "19") (pinfunction "IOQ_19") (pintype "unspecified"))
    )
    (net (code "123") (name "Net-(FB501-Pad1)") (class "Default")
      (node (ref "FB501") (pin "1") (pinfunction "1_1") (pintype "unspecified"))
      (node (ref "U306") (pin "21") (pinfunction "IOQ_21") (pintype "unspecified"))
    )
    (net (code "124") (name "Net-(FB504-Pad1)") (class "Default")
      (node (ref "FB504") (pin "1") (pinfunction "1_1") (pintype "unspecified"))
      (node (ref "U205") (pin "23") (pinfunction "IOQ_23") (pintype "unspecified"))
    )
    (net (code "125") (name "Net-(FB505-Pad1)") (class "Default")
      (node (ref "FB505") (pin "1") (pinfunction "1_1") (pintype "unspecified"))
      (node (ref "U205") (pin "25") (pinfunction "IOQ_25") (pintype "unspecified"))
    )
    (net (code "126") (name "Net-(U109-B4)") (class "Default")
      (node (ref "FB507") (pin "1") (pinfunction "1_1") (pintype "unspecified"))
      (node (ref "U109") (pin "14") (pinfunction "B4_14") (pintype "unspecified"))
    )
    (net (code "127") (name "Net-(U109-B5)") (class "Default")
      (node (ref "FB508") (pin "1") (pinfunction "1_1") (pintype "unspecified"))
      (node (ref "U109") (pin "13") (pinfunction "B5_13") (pintype "unspecified"))
    )
    (net (code "128") (name "Net-(U300-BR{slash})") (class "Default")
      (node (ref "FB503") (pin "1") (pinfunction "1_1") (pintype "unspecified"))
      (node (ref "U300") (pin "101") (pinfunction "BR/_101") (pintype "unspecified"))
    )
    (net (code "129") (name "Net-(U300-DP0)") (class "Default")
      (node (ref "R300M") (pin "2") (pinfunction "2_2") (pintype "input"))
      (node (ref "U300") (pin "86") (pinfunction "DP0_86") (pintype "unspecified"))
    )
    (net (code "130") (name "Net-(U300-DP1)") (class "Default")
      (node (ref "R300N") (pin "1") (pinfunction "1_1") (pintype "input"))
      (node (ref "U300") (pin "74") (pinfunction "DP1_74") (pintype "unspecified"))
    )
    (net (code "131") (name "Net-(U300-DP2)") (class "Default")
      (node (ref "R300O") (pin "1") (pinfunction "1_1") (pintype "input"))
      (node (ref "U300") (pin "63") (pinfunction "DP2_63") (pintype "unspecified"))
    )
    (net (code "132") (name "Net-(U300-MASTER{slash})") (class "Default")
      (node (ref "FB502") (pin "2") (pinfunction "2_2") (pintype "unspecified"))
      (node (ref "U300") (pin "38") (pinfunction "MASTER/_38") (pintype "unspecified"))
    )
    (net (code "133") (name "Net-(U300-R_W{slash})") (class "Default")
      (node (ref "FB506") (pin "2") (pinfunction "2_2") (pintype "unspecified"))
      (node (ref "U300") (pin "32") (pinfunction "R_W/_32") (pintype "unspecified"))
    )
    (net (code "134") (name "Net-(U301-OUTPUT)") (class "Default")
      (node (ref "R301A") (pin "2") (pinfunction "2_2") (pintype "input"))
      (node (ref "U301") (pin "3") (pinfunction "OUTPUT_3") (pintype "unspecified"))
    )
    (net (code "135") (name "Net-(U302-Q0#)") (class "Default")
      (node (ref "R302A") (pin "2") (pinfunction "2_2") (pintype "input"))
      (node (ref "U302") (pin "6") (pinfunction "Q0#_6") (pintype "unspecified"))
    )
    (net (code "136") (name "Net-(U302-Q0)") (class "Default")
      (node (ref "R302B") (pin "2") (pinfunction "2_2") (pintype "input"))
      (node (ref "U302") (pin "5") (pinfunction "Q0_5") (pintype "unspecified"))
    )
    (net (code "137") (name "Net-(U310-VREF1)") (class "Default")
      (node (ref "C350A") (pin "1") (pinfunction "1_1") (pintype "unspecified"))
      (node (ref "C350B") (pin "2") (pinfunction "2_2") (pintype "input"))
      (node (ref "U310") (pin "15") (pinfunction "VREF2_15") (pintype "passive"))
      (node (ref "U310") (pin "7") (pinfunction "VREF1_7") (pintype "passive"))
    )
    (net (code "138") (name "Net-(U311-VREF1)") (class "Default")
      (node (ref "C351A") (pin "1") (pinfunction "1_1") (pintype "unspecified"))
      (node (ref "C351B") (pin "1") (pinfunction "1_1") (pintype "input"))
      (node (ref "U311") (pin "15") (pinfunction "VREF2_15") (pintype "passive"))
      (node (ref "U311") (pin "7") (pinfunction "VREF1_7") (pintype "passive"))
    )
    (net (code "139") (name "PLD_AS") (class "Default")
      (node (ref "R300H") (pin "1") (pinfunction "1_1") (pintype "input"))
      (node (ref "U300") (pin "25") (pinfunction "AS/-TS/_25") (pintype "unspecified"))
      (node (ref "U304") (pin "21") (pinfunction "IOQ_21") (pintype "unspecified"))
      (node (ref "U305") (pin "4") (pinfunction "I_4") (pintype "unspecified"))
    )
    (net (code "140") (name "PLD_ASQ") (class "Default")
      (node (ref "U305") (pin "20") (pinfunction "IOQ_20") (pintype "unspecified"))
      (node (ref "U306") (pin "13") (pinfunction "I_13") (pintype "unspecified"))
    )
    (net (code "141") (name "PLD_CFGLT") (class "Default")
      (node (ref "U200") (pin "11") (pinfunction "CP_11") (pintype "unspecified"))
      (node (ref "U202") (pin "23") (pinfunction "IOQ_23") (pintype "unspecified"))
    )
    (net (code "142") (name "PLD_DOE") (class "Default")
      (node (ref "R109H") (pin "2") (pinfunction "2_2") (pintype "input"))
      (node (ref "U109") (pin "4") (pinfunction "A2_4") (pintype "unspecified"))
      (node (ref "U205") (pin "5") (pinfunction "I_5") (pintype "unspecified"))
      (node (ref "U304") (pin "10") (pinfunction "I_10") (pintype "unspecified"))
      (node (ref "U305") (pin "27") (pinfunction "IOQ_27") (pintype "unspecified"))
      (node (ref "U306") (pin "23") (pinfunction "IOQ_23") (pintype "unspecified"))
    )
    (net (code "143") (name "PLD_DS") (class "Default")
      (node (ref "R300G") (pin "1") (pinfunction "1_1") (pintype "input"))
      (node (ref "U300") (pin "87") (pinfunction "DS/-DLE_87") (pintype "unspecified"))
      (node (ref "U304") (pin "20") (pinfunction "IOQ_20") (pintype "unspecified"))
    )
    (net (code "144") (name "PLD_DS0") (class "Default")
      (node (ref "R109A") (pin "1") (pinfunction "1_1") (pintype "input"))
      (node (ref "U109") (pin "9") (pinfunction "A7_9") (pintype "unspecified"))
      (node (ref "U203") (pin "10") (pinfunction "I_10") (pintype "unspecified"))
      (node (ref "U207") (pin "6") (pinfunction "I_6") (pintype "unspecified"))
      (node (ref "U304") (pin "9") (pinfunction "I_9") (pintype "unspecified"))
      (node (ref "U305") (pin "23") (pinfunction "IOQ_23") (pintype "unspecified"))
    )
    (net (code "145") (name "PLD_DS1") (class "Default")
      (node (ref "R109B") (pin "1") (pinfunction "1_1") (pintype "input"))
      (node (ref "U109") (pin "8") (pinfunction "A6_8") (pintype "unspecified"))
      (node (ref "U304") (pin "7") (pinfunction "I_7") (pintype "unspecified"))
      (node (ref "U305") (pin "24") (pinfunction "IOQ_24") (pintype "unspecified"))
    )
    (net (code "146") (name "PLD_DS2") (class "Default")
      (node (ref "R109C") (pin "1") (pinfunction "1_1") (pintype "input"))
      (node (ref "U109") (pin "7") (pinfunction "A5_7") (pintype "unspecified"))
      (node (ref "U304") (pin "6") (pinfunction "I_6") (pintype "unspecified"))
      (node (ref "U305") (pin "25") (pinfunction "IOQ_25") (pintype "unspecified"))
    )
    (net (code "147") (name "PLD_DS3") (class "Default")
      (node (ref "R109D") (pin "1") (pinfunction "1_1") (pintype "input"))
      (node (ref "U109") (pin "6") (pinfunction "A4_6") (pintype "unspecified"))
      (node (ref "U202") (pin "11") (pinfunction "I_11") (pintype "unspecified"))
      (node (ref "U304") (pin "5") (pinfunction "I_5") (pintype "unspecified"))
      (node (ref "U305") (pin "26") (pinfunction "IOQ_26") (pintype "unspecified"))
    )
    (net (code "148") (name "PLD_DTACK") (class "Default")
      (node (ref "U303") (pin "9") (pinfunction "I_9") (pintype "unspecified"))
      (node (ref "U304") (pin "11") (pinfunction "I_11") (pintype "unspecified"))
      (node (ref "U306") (pin "17") (pinfunction "IOQ_17") (pintype "unspecified"))
    )
    (net (code "149") (name "PLD_FC0") (class "Default")
      (node (ref "R109F") (pin "1") (pinfunction "1_1") (pintype "input"))
      (node (ref "U109") (pin "3") (pinfunction "A1_3") (pintype "unspecified"))
      (node (ref "U202") (pin "16") (pinfunction "I_16") (pintype "unspecified"))
      (node (ref "U300") (pin "30") (pinfunction "FC0-TM0_30") (pintype "unspecified"))
    )
    (net (code "150") (name "PLD_FC1") (class "Default")
      (node (ref "R109G") (pin "1") (pinfunction "1_1") (pintype "input"))
      (node (ref "U109") (pin "2") (pinfunction "A0_2") (pintype "unspecified"))
      (node (ref "U202") (pin "13") (pinfunction "I_13") (pintype "unspecified"))
      (node (ref "U300") (pin "29") (pinfunction "FC1-TM1_29") (pintype "unspecified"))
    )
    (net (code "151") (name "PLD_FC2") (class "Default")
      (node (ref "R103A") (pin "1") (pinfunction "1_1") (pintype "input"))
      (node (ref "U103") (pin "8") (pinfunction "A6_8") (pintype "unspecified"))
      (node (ref "U203") (pin "11") (pinfunction "I_11") (pintype "unspecified"))
      (node (ref "U300") (pin "28") (pinfunction "FC2-TM2_28") (pintype "unspecified"))
    )
    (net (code "152") (name "PLD_FCS") (class "Default")
      (node (ref "FB500") (pin "2") (pinfunction "2_2") (pintype "unspecified"))
      (node (ref "U100") (pin "1") (pinfunction "LEBA_1") (pintype "unspecified"))
      (node (ref "U101") (pin "1") (pinfunction "LEBA_1") (pintype "unspecified"))
      (node (ref "U102") (pin "1") (pinfunction "LEBA_1") (pintype "unspecified"))
      (node (ref "U202") (pin "12") (pinfunction "I_12") (pintype "unspecified"))
      (node (ref "U203") (pin "12") (pinfunction "I_12") (pintype "unspecified"))
      (node (ref "U205") (pin "6") (pinfunction "I_6") (pintype "unspecified"))
      (node (ref "U207") (pin "12") (pinfunction "I_12") (pintype "unspecified"))
      (node (ref "U303") (pin "6") (pinfunction "I_6") (pintype "unspecified"))
      (node (ref "U306") (pin "4") (pinfunction "I_4") (pintype "unspecified"))
    )
    (net (code "153") (name "PLD_INT") (class "Default")
      (node (ref "U203") (pin "7") (pinfunction "I_7") (pintype "unspecified"))
      (node (ref "U207") (pin "26") (pinfunction "IOQ_26") (pintype "unspecified"))
    )
    (net (code "154") (name "PLD_INTREG") (class "Default")
      (node (ref "U203") (pin "24") (pinfunction "IOQ_24") (pintype "unspecified"))
      (node (ref "U205") (pin "11") (pinfunction "I_11") (pintype "unspecified"))
    )
    (net (code "155") (name "PLD_INTSPC") (class "Default")
      (node (ref "U202") (pin "27") (pinfunction "IOQ_27") (pintype "unspecified"))
      (node (ref "U203") (pin "16") (pinfunction "I_16") (pintype "unspecified"))
    )
    (net (code "156") (name "PLD_INTVEC") (class "Default")
      (node (ref "U203") (pin "23") (pinfunction "IOQ_23") (pintype "unspecified"))
      (node (ref "U205") (pin "12") (pinfunction "I_12") (pintype "unspecified"))
      (node (ref "U207") (pin "11") (pinfunction "I_11") (pintype "unspecified"))
    )
    (net (code "157") (name "PLD_MTCR") (class "Default")
      (node (ref "R109E") (pin "1") (pinfunction "1_1") (pintype "input"))
      (node (ref "U109") (pin "5") (pinfunction "A3_5") (pintype "unspecified"))
      (node (ref "U203") (pin "13") (pinfunction "I_13") (pintype "unspecified"))
      (node (ref "U205") (pin "17") (pinfunction "IOQ_17") (pintype "unspecified"))
      (node (ref "U305") (pin "10") (pinfunction "I_10") (pintype "unspecified"))
      (node (ref "U306") (pin "25") (pinfunction "IOQ_25") (pintype "unspecified"))
    )
    (net (code "158") (name "PLD_MYBUS") (class "Default")
      (node (ref "U205") (pin "4") (pinfunction "I_4") (pintype "unspecified"))
      (node (ref "U303") (pin "20") (pinfunction "IOQ_20") (pintype "unspecified"))
      (node (ref "U304") (pin "13") (pinfunction "I_13") (pintype "unspecified"))
      (node (ref "U305") (pin "3") (pinfunction "I_3") (pintype "unspecified"))
      (node (ref "U306") (pin "3") (pinfunction "I_3") (pintype "unspecified"))
    )
    (net (code "159") (name "PLD_NACK") (class "Default")
      (node (ref "U205") (pin "16") (pinfunction "I_16") (pintype "unspecified"))
      (node (ref "U207") (pin "24") (pinfunction "IOQ_24") (pintype "unspecified"))
    )
    (net (code "160") (name "PLD_NOZ3") (class "Default")
      (node (ref "U205") (pin "10") (pinfunction "I_10") (pintype "unspecified"))
      (node (ref "U305") (pin "9") (pinfunction "I_9") (pintype "unspecified"))
      (node (ref "U306") (pin "20") (pinfunction "IOQ_20") (pintype "unspecified"))
    )
    (net (code "161") (name "PLD_READ") (class "Default")
      (node (ref "FB506") (pin "1") (pinfunction "1_1") (pintype "unspecified"))
      (node (ref "R103B") (pin "1") (pinfunction "1_1") (pintype "input"))
      (node (ref "U103") (pin "9") (pinfunction "A7_9") (pintype "unspecified"))
      (node (ref "U202") (pin "10") (pinfunction "I_10") (pintype "unspecified"))
      (node (ref "U203") (pin "9") (pinfunction "I_9") (pintype "unspecified"))
      (node (ref "U205") (pin "7") (pinfunction "I_7") (pintype "unspecified"))
      (node (ref "U207") (pin "7") (pinfunction "I_7") (pintype "unspecified"))
      (node (ref "U304") (pin "4") (pinfunction "I_4") (pintype "unspecified"))
      (node (ref "U305") (pin "5") (pinfunction "I_5") (pintype "unspecified"))
    )
    (net (code "162") (name "PLD_SCSI") (class "Default")
      (node (ref "U203") (pin "26") (pinfunction "IOQ_26") (pintype "unspecified"))
      (node (ref "U304") (pin "3") (pinfunction "I_3") (pintype "unspecified"))
      (node (ref "U306") (pin "7") (pinfunction "I_7") (pintype "unspecified"))
    )
    (net (code "163") (name "PLD_SID") (class "Default")
      (node (ref "U203") (pin "17") (pinfunction "IOQ_17") (pintype "unspecified"))
      (node (ref "U205") (pin "19") (pinfunction "IOQ_19") (pintype "unspecified"))
      (node (ref "U213") (pin "1") (pinfunction "OE1#_1") (pintype "unspecified"))
      (node (ref "U213") (pin "19") (pinfunction "OE2#_19") (pintype "unspecified"))
    )
    (net (code "164") (name "PLD_SIZ0") (class "Default")
      (node (ref "R300E") (pin "1") (pinfunction "1_1") (pintype "input"))
      (node (ref "U300") (pin "27") (pinfunction "SIZ0_27") (pintype "unspecified"))
      (node (ref "U304") (pin "24") (pinfunction "IOQ_24") (pintype "unspecified"))
      (node (ref "U305") (pin "7") (pinfunction "I_7") (pintype "unspecified"))
    )
    (net (code "165") (name "PLD_SIZ1") (class "Default")
      (node (ref "R300F") (pin "1") (pinfunction "1_1") (pintype "input"))
      (node (ref "U300") (pin "26") (pinfunction "SIZ1_26") (pintype "unspecified"))
      (node (ref "U304") (pin "25") (pinfunction "IOQ_25") (pintype "unspecified"))
      (node (ref "U305") (pin "6") (pinfunction "I_6") (pintype "unspecified"))
    )
    (net (code "166") (name "ROM_OE") (class "Default")
      (node (ref "U203") (pin "25") (pinfunction "IOQ_25") (pintype "unspecified"))
      (node (ref "U206") (pin "22") (pinfunction "OE#_22") (pintype "passive"))
      (node (ref "U207") (pin "19") (pinfunction "IOQ_19") (pintype "unspecified"))
    )
    (net (code "167") (name "SBG") (class "Default")
      (node (ref "U300") (pin "100") (pinfunction "BG/_100") (pintype "unspecified"))
      (node (ref "U303") (pin "21") (pinfunction "IOQ_21") (pintype "unspecified"))
    )
    (net (code "168") (name "SBR") (class "Default")
      (node (ref "FB503") (pin "2") (pinfunction "2_2") (pintype "unspecified"))
      (node (ref "U303") (pin "4") (pinfunction "I_4") (pintype "unspecified"))
    )
    (net (code "169") (name "SCDAT0") (class "Default")
      (node (ref "FB311A") (pin "2") (pinfunction "2_2") (pintype "unspecified"))
      (node (ref "U300") (pin "131") (pinfunction "SD0/_131") (pintype "unspecified"))
      (node (ref "U311") (pin "3") (pinfunction "R2_3") (pintype "unspecified"))
    )
    (net (code "170") (name "SCDAT1") (class "Default")
      (node (ref "FB311B") (pin "2") (pinfunction "2_2") (pintype "unspecified"))
      (node (ref "U300") (pin "130") (pinfunction "SD1/_130") (pintype "unspecified"))
      (node (ref "U311") (pin "4") (pinfunction "R3_4") (pintype "unspecified"))
    )
    (net (code "171") (name "SCDAT2") (class "Default")
      (node (ref "FB311C") (pin "2") (pinfunction "2_2") (pintype "unspecified"))
      (node (ref "U300") (pin "129") (pinfunction "SD2/_129") (pintype "unspecified"))
      (node (ref "U311") (pin "5") (pinfunction "R4_5") (pintype "unspecified"))
    )
    (net (code "172") (name "SCDAT3") (class "Default")
      (node (ref "FB311D") (pin "2") (pinfunction "2_2") (pintype "unspecified"))
      (node (ref "U300") (pin "127") (pinfunction "SD3/_127") (pintype "unspecified"))
      (node (ref "U311") (pin "6") (pinfunction "R5_6") (pintype "unspecified"))
    )
    (net (code "173") (name "SCDAT4") (class "Default")
      (node (ref "FB311E") (pin "2") (pinfunction "2_2") (pintype "unspecified"))
      (node (ref "U300") (pin "126") (pinfunction "SD4/_126") (pintype "unspecified"))
      (node (ref "U310") (pin "5") (pinfunction "R4_5") (pintype "unspecified"))
    )
    (net (code "174") (name "SCDAT5") (class "Default")
      (node (ref "FB311F") (pin "2") (pinfunction "2_2") (pintype "unspecified"))
      (node (ref "U300") (pin "125") (pinfunction "SD5/_125") (pintype "unspecified"))
      (node (ref "U311") (pin "10") (pinfunction "R6_10") (pintype "unspecified"))
    )
    (net (code "175") (name "SCDAT6") (class "Default")
      (node (ref "FB311G") (pin "2") (pinfunction "2_2") (pintype "unspecified"))
      (node (ref "U300") (pin "124") (pinfunction "SD6/_124") (pintype "unspecified"))
      (node (ref "U311") (pin "11") (pinfunction "R7_11") (pintype "unspecified"))
    )
    (net (code "176") (name "SCDAT7") (class "Default")
      (node (ref "FB311H") (pin "2") (pinfunction "2_2") (pintype "unspecified"))
      (node (ref "U300") (pin "122") (pinfunction "SD7/_122") (pintype "unspecified"))
      (node (ref "U311") (pin "12") (pinfunction "R8_12") (pintype "unspecified"))
    )
    (net (code "177") (name "SCDATP") (class "Default")
      (node (ref "FB311I") (pin "2") (pinfunction "2_2") (pintype "unspecified"))
      (node (ref "U300") (pin "121") (pinfunction "SDP/_121") (pintype "unspecified"))
      (node (ref "U311") (pin "13") (pinfunction "R9_13") (pintype "unspecified"))
    )
    (net (code "178") (name "SCSI_BUSY") (class "Default")
      (node (ref "CN309") (pin "36") (pinfunction "36_36") (pintype "unspecified"))
      (node (ref "FB311R") (pin "1") (pinfunction "1_1") (pintype "unspecified"))
      (node (ref "U307") (pin "1") (pinfunction "1A_1") (pintype "unspecified"))
      (node (ref "U307") (pin "3") (pinfunction "2A_3") (pintype "unspecified"))
    )
    (net (code "179") (name "SCSI_TERMPWR") (class "Default")
      (node (ref "CN309") (pin "26") (pinfunction "26_26") (pintype "unspecified"))
      (node (ref "F309B") (pin "2") (pinfunction "2_2") (pintype "unspecified"))
      (node (ref "U310") (pin "1") (pinfunction "TPWR1_1") (pintype "passive"))
      (node (ref "U310") (pin "9") (pinfunction "TPWR2_9") (pintype "passive"))
      (node (ref "U311") (pin "1") (pinfunction "TPWR1_1") (pintype "passive"))
      (node (ref "U311") (pin "9") (pinfunction "TPWR2_9") (pintype "passive"))
    )
    (net (code "180") (name "SCTRL_ACK") (class "Default")
      (node (ref "FB311Q") (pin "2") (pinfunction "2_2") (pintype "unspecified"))
      (node (ref "U300") (pin "117") (pinfunction "ACK/_117") (pintype "unspecified"))
      (node (ref "U310") (pin "10") (pinfunction "R6_10") (pintype "unspecified"))
    )
    (net (code "181") (name "SCTRL_ATN") (class "Default")
      (node (ref "FB311J") (pin "2") (pinfunction "2_2") (pintype "unspecified"))
      (node (ref "U300") (pin "120") (pinfunction "ATN/_120") (pintype "unspecified"))
      (node (ref "U310") (pin "6") (pinfunction "R5_6") (pintype "unspecified"))
    )
    (net (code "182") (name "SCTRL_BSY") (class "Default")
      (node (ref "FB311R") (pin "2") (pinfunction "2_2") (pintype "unspecified"))
      (node (ref "U300") (pin "119") (pinfunction "BSY/_119") (pintype "unspecified"))
      (node (ref "U310") (pin "2") (pinfunction "R1_2") (pintype "unspecified"))
    )
    (net (code "183") (name "SCTRL_CD") (class "Default")
      (node (ref "FB311M") (pin "2") (pinfunction "2_2") (pintype "unspecified"))
      (node (ref "U300") (pin "112") (pinfunction "C/D_112") (pintype "unspecified"))
      (node (ref "U311") (pin "2") (pinfunction "R1_2") (pintype "unspecified"))
    )
    (net (code "184") (name "SCTRL_IO") (class "Default")
      (node (ref "FB311K") (pin "2") (pinfunction "2_2") (pintype "unspecified"))
      (node (ref "U300") (pin "110") (pinfunction "I/O_110") (pintype "unspecified"))
      (node (ref "U310") (pin "13") (pinfunction "R9_13") (pintype "unspecified"))
    )
    (net (code "185") (name "SCTRL_MSG") (class "Default")
      (node (ref "FB311O") (pin "2") (pinfunction "2_2") (pintype "unspecified"))
      (node (ref "U300") (pin "115") (pinfunction "MSG/_115") (pintype "unspecified"))
      (node (ref "U310") (pin "12") (pinfunction "R8_12") (pintype "unspecified"))
    )
    (net (code "186") (name "SCTRL_REQ") (class "Default")
      (node (ref "FB311L") (pin "2") (pinfunction "2_2") (pintype "unspecified"))
      (node (ref "U300") (pin "111") (pinfunction "REQ/_111") (pintype "unspecified"))
      (node (ref "U310") (pin "11") (pinfunction "R7_11") (pintype "unspecified"))
    )
    (net (code "187") (name "SCTRL_RST") (class "Default")
      (node (ref "FB311P") (pin "2") (pinfunction "2_2") (pintype "unspecified"))
      (node (ref "U300") (pin "116") (pinfunction "RST/_116") (pintype "unspecified"))
      (node (ref "U310") (pin "4") (pinfunction "R3_4") (pintype "unspecified"))
    )
    (net (code "188") (name "SCTRL_SEL") (class "Default")
      (node (ref "FB311N") (pin "2") (pinfunction "2_2") (pintype "unspecified"))
      (node (ref "U300") (pin "114") (pinfunction "SEL/_114") (pintype "unspecified"))
      (node (ref "U310") (pin "3") (pinfunction "R2_3") (pintype "unspecified"))
    )
    (net (code "189") (name "SLACK") (class "Default")
      (node (ref "U205") (pin "9") (pinfunction "I_9") (pintype "unspecified"))
      (node (ref "U300") (pin "92") (pinfunction "SLACK/_92") (pintype "unspecified"))
    )
    (net (code "190") (name "SREG") (class "Default")
      (node (ref "U300") (pin "93") (pinfunction "CS/_93") (pintype "unspecified"))
      (node (ref "U304") (pin "19") (pinfunction "IOQ_19") (pintype "unspecified"))
    )
    (net (code "191") (name "STERM") (class "Default")
      (node (ref "R300D") (pin "2") (pinfunction "2_2") (pintype "input"))
      (node (ref "U300") (pin "36") (pinfunction "STERM/-TA/_36") (pintype "unspecified"))
      (node (ref "U304") (pin "12") (pinfunction "I_12") (pintype "unspecified"))
      (node (ref "U306") (pin "19") (pinfunction "IOQ_19") (pintype "unspecified"))
    )
    (net (code "192") (name "V5") (class "Default")
      (node (ref "C1") (pin "05") (pinfunction "+5V_05") (pintype "bidirectional"))
      (node (ref "C1") (pin "06") (pinfunction "+5V_06") (pintype "bidirectional"))
      (node (ref "C10") (pin "1") (pinfunction "1_1") (pintype "input"))
      (node (ref "C100A") (pin "1") (pinfunction "1_1") (pintype "input"))
      (node (ref "C101A") (pin "1") (pinfunction "1_1") (pintype "input"))
      (node (ref "C102A") (pin "1") (pinfunction "1_1") (pintype "input"))
      (node (ref "C103A") (pin "1") (pinfunction "1_1") (pintype "input"))
      (node (ref "C105A") (pin "1") (pinfunction "1_1") (pintype "input"))
      (node (ref "C106A") (pin "2") (pinfunction "2_2") (pintype "input"))
      (node (ref "C107A") (pin "1") (pinfunction "1_1") (pintype "input"))
      (node (ref "C108A") (pin "1") (pinfunction "1_1") (pintype "input"))
      (node (ref "C109A") (pin "1") (pinfunction "1_1") (pintype "input"))
      (node (ref "C11") (pin "1") (pinfunction "1_1") (pintype "input"))
      (node (ref "C12") (pin "1") (pinfunction "1_1") (pintype "input"))
      (node (ref "C13") (pin "1") (pinfunction "1_1") (pintype "input"))
      (node (ref "C1A") (pin "2") (pinfunction "2_2") (pintype "input"))
      (node (ref "C1B") (pin "1") (pinfunction "1_1") (pintype "input"))
      (node (ref "C200A") (pin "2") (pinfunction "2_2") (pintype "input"))
      (node (ref "C201A") (pin "1") (pinfunction "1_1") (pintype "input"))
      (node (ref "C202A") (pin "1") (pinfunction "1_1") (pintype "input"))
      (node (ref "C203A") (pin "1") (pinfunction "1_1") (pintype "input"))
      (node (ref "C205A") (pin "1") (pinfunction "1_1") (pintype "input"))
      (node (ref "C206A") (pin "2") (pinfunction "2_2") (pintype "input"))
      (node (ref "C207A") (pin "1") (pinfunction "1_1") (pintype "input"))
      (node (ref "C212A") (pin "1") (pinfunction "1_1") (pintype "input"))
      (node (ref "C300A") (pin "1") (pinfunction "1_1") (pintype "input"))
      (node (ref "C300B") (pin "1") (pinfunction "1_1") (pintype "input"))
      (node (ref "C300C") (pin "1") (pinfunction "1_1") (pintype "input"))
      (node (ref "C300D") (pin "2") (pinfunction "2_2") (pintype "input"))
      (node (ref "C300E") (pin "1") (pinfunction "1_1") (pintype "input"))
      (node (ref "C300F") (pin "1") (pinfunction "1_1") (pintype "input"))
      (node (ref "C300G") (pin "1") (pinfunction "1_1") (pintype "input"))
      (node (ref "C300H") (pin "2") (pinfunction "2_2") (pintype "input"))
      (node (ref "C300I") (pin "1") (pinfunction "1_1") (pintype "input"))
      (node (ref "C301A") (pin "2") (pinfunction "2_2") (pintype "input"))
      (node (ref "C302A") (pin "1") (pinfunction "1_1") (pintype "input"))
      (node (ref "C303A") (pin "2") (pinfunction "2_2") (pintype "input"))
      (node (ref "C304A") (pin "1") (pinfunction "1_1") (pintype "input"))
      (node (ref "C305A") (pin "1") (pinfunction "1_1") (pintype "input"))
      (node (ref "C306A") (pin "1") (pinfunction "1_1") (pintype "input"))
      (node (ref "C307A") (pin "2") (pinfunction "2_2") (pintype "input"))
      (node (ref "CN1") (pin "1") (pinfunction "5V_1") (pintype "unspecified"))
      (node (ref "CN308") (pin "2") (pinfunction "2_2") (pintype "input"))
      (node (ref "CN351") (pin "2") (pinfunction "2_2") (pintype "input"))
      (node (ref "D309A") (pin "2") (pinfunction "A_2") (pintype "unspecified"))
      (node (ref "R100A") (pin "2") (pinfunction "2_2") (pintype "input"))
      (node (ref "R103A") (pin "2") (pinfunction "2_2") (pintype "input"))
      (node (ref "R103B") (pin "2") (pinfunction "2_2") (pintype "input"))
      (node (ref "R109A") (pin "2") (pinfunction "2_2") (pintype "input"))
      (node (ref "R109B") (pin "2") (pinfunction "2_2") (pintype "input"))
      (node (ref "R109C") (pin "2") (pinfunction "2_2") (pintype "input"))
      (node (ref "R109D") (pin "2") (pinfunction "2_2") (pintype "input"))
      (node (ref "R109E") (pin "2") (pinfunction "2_2") (pintype "input"))
      (node (ref "R109F") (pin "2") (pinfunction "2_2") (pintype "input"))
      (node (ref "R109G") (pin "2") (pinfunction "2_2") (pintype "input"))
      (node (ref "R200A") (pin "2") (pinfunction "2_2") (pintype "input"))
      (node (ref "R200B") (pin "2") (pinfunction "2_2") (pintype "input"))
      (node (ref "R200C") (pin "2") (pinfunction "2_2") (pintype "input"))
      (node (ref "R200D") (pin "2") (pinfunction "2_2") (pintype "input"))
      (node (ref "R200E") (pin "2") (pinfunction "2_2") (pintype "input"))
      (node (ref "R200F") (pin "2") (pinfunction "2_2") (pintype "input"))
      (node (ref "R200G") (pin "2") (pinfunction "2_2") (pintype "input"))
      (node (ref "R200H") (pin "2") (pinfunction "2_2") (pintype "input"))
      (node (ref "R212A") (pin "1") (pinfunction "1_1") (pintype "input"))
      (node (ref "R212B") (pin "2") (pinfunction "2_2") (pintype "input"))
      (node (ref "R212C") (pin "2") (pinfunction "2_2") (pintype "input"))
      (node (ref "R212D") (pin "2") (pinfunction "2_2") (pintype "input"))
      (node (ref "R212E") (pin "1") (pinfunction "1_1") (pintype "input"))
      (node (ref "R212F") (pin "1") (pinfunction "1_1") (pintype "input"))
      (node (ref "R212G") (pin "1") (pinfunction "1_1") (pintype "input"))
      (node (ref "R212H") (pin "1") (pinfunction "1_1") (pintype "input"))
      (node (ref "R300A") (pin "2") (pinfunction "2_2") (pintype "input"))
      (node (ref "R300B") (pin "1") (pinfunction "1_1") (pintype "input"))
      (node (ref "R300C") (pin "2") (pinfunction "2_2") (pintype "input"))
      (node (ref "R300D") (pin "1") (pinfunction "1_1") (pintype "input"))
      (node (ref "R300E") (pin "2") (pinfunction "2_2") (pintype "input"))
      (node (ref "R300F") (pin "2") (pinfunction "2_2") (pintype "input"))
      (node (ref "R300G") (pin "2") (pinfunction "2_2") (pintype "input"))
      (node (ref "R300H") (pin "2") (pinfunction "2_2") (pintype "input"))
      (node (ref "R300I") (pin "2") (pinfunction "2_2") (pintype "input"))
      (node (ref "R300J") (pin "2") (pinfunction "2_2") (pintype "input"))
      (node (ref "R300K") (pin "2") (pinfunction "2_2") (pintype "input"))
      (node (ref "R300L") (pin "2") (pinfunction "2_2") (pintype "input"))
      (node (ref "R300M") (pin "1") (pinfunction "1_1") (pintype "input"))
      (node (ref "R300N") (pin "2") (pinfunction "2_2") (pintype "input"))
      (node (ref "R300O") (pin "2") (pinfunction "2_2") (pintype "input"))
      (node (ref "R300P") (pin "2") (pinfunction "2_2") (pintype "input"))
      (node (ref "R307A") (pin "2") (pinfunction "2_2") (pintype "input"))
      (node (ref "R307B") (pin "1") (pinfunction "1_1") (pintype "input"))
      (node (ref "U100") (pin "24") (pinfunction "VCC_24") (pintype "passive"))
      (node (ref "U101") (pin "24") (pinfunction "VCC_24") (pintype "passive"))
      (node (ref "U102") (pin "24") (pinfunction "VCC_24") (pintype "passive"))
      (node (ref "U103") (pin "20") (pinfunction "VCC_20") (pintype "unspecified"))
      (node (ref "U105") (pin "24") (pinfunction "VCC_24") (pintype "passive"))
      (node (ref "U106") (pin "24") (pinfunction "VCC_24") (pintype "passive"))
      (node (ref "U107") (pin "24") (pinfunction "VCC_24") (pintype "passive"))
      (node (ref "U108") (pin "24") (pinfunction "VCC_24") (pintype "passive"))
      (node (ref "U109") (pin "20") (pinfunction "VCC_20") (pintype "unspecified"))
      (node (ref "U200") (pin "20") (pinfunction "VCC_20") (pintype "unspecified"))
      (node (ref "U201") (pin "20") (pinfunction "VCC_20") (pintype "unspecified"))
      (node (ref "U202") (pin "1") (pinfunction "NC_1") (pintype "unspecified"))
      (node (ref "U202") (pin "28") (pinfunction "VCC_28") (pintype "unspecified"))
      (node (ref "U203") (pin "1") (pinfunction "NC_1") (pintype "unspecified"))
      (node (ref "U203") (pin "28") (pinfunction "VCC_28") (pintype "unspecified"))
      (node (ref "U205") (pin "1") (pinfunction "NC_1") (pintype "unspecified"))
      (node (ref "U205") (pin "28") (pinfunction "VCC_28") (pintype "unspecified"))
      (node (ref "U206") (pin "28") (pinfunction "VCC_28") (pintype "output"))
      (node (ref "U207") (pin "1") (pinfunction "NC_1") (pintype "unspecified"))
      (node (ref "U207") (pin "28") (pinfunction "VCC_28") (pintype "unspecified"))
      (node (ref "U213") (pin "20") (pinfunction "VCC_20") (pintype "unspecified"))
      (node (ref "U300") (pin "139") (pinfunction "Vdd_139") (pintype "unspecified"))
      (node (ref "U300") (pin "153") (pinfunction "Vdd_153") (pintype "unspecified"))
      (node (ref "U300") (pin "19") (pinfunction "Vdd_19") (pintype "unspecified"))
      (node (ref "U300") (pin "39") (pinfunction "Vdd_39") (pintype "unspecified"))
      (node (ref "U300") (pin "40") (pinfunction "HALT/-TIP/_40") (pintype "unspecified"))
      (node (ref "U300") (pin "49") (pinfunction "Vdd_49") (pintype "unspecified"))
      (node (ref "U300") (pin "6") (pinfunction "Vdd_6") (pintype "unspecified"))
      (node (ref "U300") (pin "64") (pinfunction "Vdd_64") (pintype "unspecified"))
      (node (ref "U300") (pin "79") (pinfunction "Vdd_79") (pintype "unspecified"))
      (node (ref "U300") (pin "90") (pinfunction "BIG_LIT/_90") (pintype "unspecified"))
      (node (ref "U300") (pin "91") (pinfunction "BS_91") (pintype "unspecified"))
      (node (ref "U300") (pin "95") (pinfunction "BOFF/_95") (pintype "unspecified"))
      (node (ref "U300") (pin "99") (pinfunction "Vdd_99") (pintype "unspecified"))
      (node (ref "U301") (pin "4") (pinfunction "VDD_4") (pintype "unspecified"))
      (node (ref "U302") (pin "1") (pinfunction "RD0#_1") (pintype "unspecified"))
      (node (ref "U302") (pin "10") (pinfunction "SD1#_10") (pintype "unspecified"))
      (node (ref "U302") (pin "11") (pinfunction "CP1_11") (pintype "unspecified"))
      (node (ref "U302") (pin "12") (pinfunction "D1_12") (pintype "unspecified"))
      (node (ref "U302") (pin "13") (pinfunction "RD1#_13") (pintype "unspecified"))
      (node (ref "U302") (pin "14") (pinfunction "VCC_14") (pintype "unspecified"))
      (node (ref "U302") (pin "4") (pinfunction "SD0#_4") (pintype "unspecified"))
      (node (ref "U303") (pin "1") (pinfunction "NC_1") (pintype "unspecified"))
      (node (ref "U303") (pin "28") (pinfunction "VCC_28") (pintype "unspecified"))
      (node (ref "U304") (pin "1") (pinfunction "NC_1") (pintype "unspecified"))
      (node (ref "U304") (pin "28") (pinfunction "VCC_28") (pintype "unspecified"))
      (node (ref "U305") (pin "1") (pinfunction "NC_1") (pintype "unspecified"))
      (node (ref "U305") (pin "28") (pinfunction "VCC_28") (pintype "unspecified"))
      (node (ref "U306") (pin "1") (pinfunction "NC_1") (pintype "unspecified"))
      (node (ref "U306") (pin "28") (pinfunction "VCC_28") (pintype "unspecified"))
      (node (ref "U307") (pin "14") (pinfunction "VCC_14") (pintype "unspecified"))
    )
    (net (code "193") (name "V12") (class "Default")
      (node (ref "C1") (pin "10") (pinfunction "+12V_10") (pintype "bidirectional"))
      (node (ref "C1C") (pin "1") (pinfunction "1_1") (pintype "input"))
      (node (ref "CN1") (pin "4") (pinfunction "12V_4") (pintype "unspecified"))
    )
    (net (code "194") (name "Z2D") (class "Default")
      (node (ref "FB504") (pin "2") (pinfunction "2_2") (pintype "unspecified"))
      (node (ref "U105") (pin "23") (pinfunction "CEBA_23") (pintype "unspecified"))
      (node (ref "U106") (pin "23") (pinfunction "CEBA_23") (pintype "unspecified"))
      (node (ref "U107") (pin "23") (pinfunction "CEBA_23") (pintype "unspecified"))
      (node (ref "U108") (pin "23") (pinfunction "CEBA_23") (pintype "unspecified"))
    )
    (net (code "195") (name "Z_7M") (class "Default")
      (node (ref "C1") (pin "92") (pinfunction "7M_Clock_92") (pintype "bidirectional"))
      (node (ref "U303") (pin "2") (pinfunction "CLK/I_2") (pintype "unspecified"))
    )
    (net (code "196") (name "Z_A2") (class "Default")
      (node (ref "C1") (pin "27") (pinfunction "A2_27") (pintype "output"))
      (node (ref "U103") (pin "13") (pinfunction "B5_13") (pintype "unspecified"))
    )
    (net (code "197") (name "Z_A3") (class "Default")
      (node (ref "C1") (pin "26") (pinfunction "A3_26") (pintype "bidirectional"))
      (node (ref "U103") (pin "14") (pinfunction "B4_14") (pintype "unspecified"))
    )
    (net (code "198") (name "Z_A4") (class "Default")
      (node (ref "C1") (pin "24") (pinfunction "A4_24") (pintype "bidirectional"))
      (node (ref "U103") (pin "15") (pinfunction "B3_15") (pintype "unspecified"))
    )
    (net (code "199") (name "Z_A5") (class "Default")
      (node (ref "C1") (pin "21") (pinfunction "A5_21") (pintype "output"))
      (node (ref "U103") (pin "16") (pinfunction "B2_16") (pintype "unspecified"))
    )
    (net (code "200") (name "Z_A6") (class "Default")
      (node (ref "C1") (pin "23") (pinfunction "A6_23") (pintype "output"))
      (node (ref "U103") (pin "17") (pinfunction "B1_17") (pintype "unspecified"))
    )
    (net (code "201") (name "Z_A7") (class "Default")
      (node (ref "C1") (pin "28") (pinfunction "A7_28") (pintype "bidirectional"))
      (node (ref "U103") (pin "18") (pinfunction "B0_18") (pintype "unspecified"))
    )
    (net (code "202") (name "Z_A8D0") (class "Default")
      (node (ref "C1") (pin "30") (pinfunction "A8+D0,A8_30") (pintype "bidirectional"))
      (node (ref "U102") (pin "15") (pinfunction "B7_15") (pintype "bidirectional"))
      (node (ref "U107") (pin "15") (pinfunction "B7_15") (pintype "bidirectional"))
    )
    (net (code "203") (name "Z_A9D1") (class "Default")
      (node (ref "C1") (pin "32") (pinfunction "A9+D1,A9_32") (pintype "bidirectional"))
      (node (ref "U102") (pin "16") (pinfunction "B6_16") (pintype "bidirectional"))
      (node (ref "U107") (pin "16") (pinfunction "B6_16") (pintype "bidirectional"))
    )
    (net (code "204") (name "Z_A10D2") (class "Default")
      (node (ref "C1") (pin "34") (pinfunction "A10+D2,A10_34") (pintype "bidirectional"))
      (node (ref "U102") (pin "17") (pinfunction "B5_17") (pintype "bidirectional"))
      (node (ref "U107") (pin "17") (pinfunction "B5_17") (pintype "bidirectional"))
    )
    (net (code "205") (name "Z_A11D3") (class "Default")
      (node (ref "C1") (pin "36") (pinfunction "A11+D3,A11_36") (pintype "bidirectional"))
      (node (ref "U102") (pin "18") (pinfunction "B4_18") (pintype "bidirectional"))
      (node (ref "U107") (pin "18") (pinfunction "B4_18") (pintype "bidirectional"))
    )
    (net (code "206") (name "Z_A12D4") (class "Default")
      (node (ref "C1") (pin "38") (pinfunction "A12+D4,A12_38") (pintype "bidirectional"))
      (node (ref "U102") (pin "19") (pinfunction "B3_19") (pintype "bidirectional"))
      (node (ref "U107") (pin "19") (pinfunction "B3_19") (pintype "bidirectional"))
    )
    (net (code "207") (name "Z_A13D5") (class "Default")
      (node (ref "C1") (pin "39") (pinfunction "A13+D5,A13_39") (pintype "unspecified"))
      (node (ref "U102") (pin "20") (pinfunction "B2_20") (pintype "bidirectional"))
      (node (ref "U107") (pin "20") (pinfunction "B2_20") (pintype "bidirectional"))
    )
    (net (code "208") (name "Z_A14D6") (class "Default")
      (node (ref "C1") (pin "41") (pinfunction "A14+D6,A14_41") (pintype "unspecified"))
      (node (ref "U102") (pin "21") (pinfunction "B1_21") (pintype "bidirectional"))
      (node (ref "U107") (pin "21") (pinfunction "B1_21") (pintype "bidirectional"))
    )
    (net (code "209") (name "Z_A15D7") (class "Default")
      (node (ref "C1") (pin "43") (pinfunction "A15+D7,A15_43") (pintype "unspecified"))
      (node (ref "U102") (pin "22") (pinfunction "B0_22") (pintype "bidirectional"))
      (node (ref "U107") (pin "22") (pinfunction "B0_22") (pintype "bidirectional"))
    )
    (net (code "210") (name "Z_A16D8") (class "Default")
      (node (ref "C1") (pin "45") (pinfunction "A16+D8,A16_45") (pintype "unspecified"))
      (node (ref "U101") (pin "15") (pinfunction "B7_15") (pintype "bidirectional"))
      (node (ref "U106") (pin "15") (pinfunction "B7_15") (pintype "bidirectional"))
    )
    (net (code "211") (name "Z_A17D9") (class "Default")
      (node (ref "C1") (pin "47") (pinfunction "A17+D9,A17_47") (pintype "unspecified"))
      (node (ref "U101") (pin "16") (pinfunction "B6_16") (pintype "bidirectional"))
      (node (ref "U106") (pin "16") (pinfunction "B6_16") (pintype "bidirectional"))
    )
    (net (code "212") (name "Z_A18D10") (class "Default")
      (node (ref "C1") (pin "52") (pinfunction "A18+D10,A18_52") (pintype "bidirectional"))
      (node (ref "U101") (pin "17") (pinfunction "B5_17") (pintype "bidirectional"))
      (node (ref "U106") (pin "17") (pinfunction "B5_17") (pintype "bidirectional"))
    )
    (net (code "213") (name "Z_A19D11") (class "Default")
      (node (ref "C1") (pin "54") (pinfunction "A19+D11,A19_54") (pintype "bidirectional"))
      (node (ref "U101") (pin "18") (pinfunction "B4_18") (pintype "bidirectional"))
      (node (ref "U106") (pin "18") (pinfunction "B4_18") (pintype "bidirectional"))
    )
    (net (code "214") (name "Z_A20D12") (class "Default")
      (node (ref "C1") (pin "56") (pinfunction "A20+D12,A20_56") (pintype "bidirectional"))
      (node (ref "U101") (pin "19") (pinfunction "B3_19") (pintype "bidirectional"))
      (node (ref "U106") (pin "19") (pinfunction "B3_19") (pintype "bidirectional"))
    )
    (net (code "215") (name "Z_A21D13") (class "Default")
      (node (ref "C1") (pin "58") (pinfunction "A21+D13,A21_58") (pintype "bidirectional"))
      (node (ref "U101") (pin "20") (pinfunction "B2_20") (pintype "bidirectional"))
      (node (ref "U106") (pin "20") (pinfunction "B2_20") (pintype "bidirectional"))
    )
    (net (code "216") (name "Z_A22D14") (class "Default")
      (node (ref "C1") (pin "57") (pinfunction "A22+D14,A22_57") (pintype "bidirectional"))
      (node (ref "U101") (pin "21") (pinfunction "B1_21") (pintype "bidirectional"))
      (node (ref "U106") (pin "21") (pinfunction "B1_21") (pintype "bidirectional"))
    )
    (net (code "217") (name "Z_A23D15") (class "Default")
      (node (ref "C1") (pin "59") (pinfunction "A23+D15,A23_59") (pintype "output"))
      (node (ref "U101") (pin "22") (pinfunction "B0_22") (pintype "bidirectional"))
      (node (ref "U106") (pin "22") (pinfunction "B0_22") (pintype "bidirectional"))
    )
    (net (code "218") (name "Z_A24D24") (class "Default")
      (node (ref "C1") (pin "80") (pinfunction "A24+D24,D8_80") (pintype "unspecified"))
      (node (ref "U100") (pin "15") (pinfunction "B7_15") (pintype "bidirectional"))
      (node (ref "U105") (pin "22") (pinfunction "B0_22") (pintype "bidirectional"))
    )
    (net (code "219") (name "Z_A25D25") (class "Default")
      (node (ref "C1") (pin "78") (pinfunction "A25+D25,D9_78") (pintype "unspecified"))
      (node (ref "U100") (pin "16") (pinfunction "B6_16") (pintype "bidirectional"))
      (node (ref "U105") (pin "21") (pinfunction "B1_21") (pintype "bidirectional"))
    )
    (net (code "220") (name "Z_A26D26") (class "Default")
      (node (ref "C1") (pin "76") (pinfunction "A26+D26,D10_76") (pintype "unspecified"))
      (node (ref "U100") (pin "17") (pinfunction "B5_17") (pintype "bidirectional"))
      (node (ref "U105") (pin "20") (pinfunction "B2_20") (pintype "bidirectional"))
    )
    (net (code "221") (name "Z_A27D27") (class "Default")
      (node (ref "C1") (pin "71") (pinfunction "A27+D27,D11_71") (pintype "unspecified"))
      (node (ref "U100") (pin "18") (pinfunction "B4_18") (pintype "bidirectional"))
      (node (ref "U105") (pin "19") (pinfunction "B3_19") (pintype "bidirectional"))
    )
    (net (code "222") (name "Z_A28D28") (class "Default")
      (node (ref "C1") (pin "69") (pinfunction "A28+D28,D12_69") (pintype "unspecified"))
      (node (ref "U100") (pin "19") (pinfunction "B3_19") (pintype "bidirectional"))
      (node (ref "U105") (pin "18") (pinfunction "B4_18") (pintype "bidirectional"))
    )
    (net (code "223") (name "Z_A29D29") (class "Default")
      (node (ref "C1") (pin "67") (pinfunction "A29+D29,D13_67") (pintype "unspecified"))
      (node (ref "U100") (pin "20") (pinfunction "B2_20") (pintype "bidirectional"))
      (node (ref "U105") (pin "17") (pinfunction "B5_17") (pintype "bidirectional"))
    )
    (net (code "224") (name "Z_A30D30") (class "Default")
      (node (ref "C1") (pin "65") (pinfunction "A30+D30,D14_65") (pintype "unspecified"))
      (node (ref "U100") (pin "21") (pinfunction "B1_21") (pintype "bidirectional"))
      (node (ref "U105") (pin "16") (pinfunction "B6_16") (pintype "bidirectional"))
    )
    (net (code "225") (name "Z_A31D31") (class "Default")
      (node (ref "C1") (pin "63") (pinfunction "A31+D31,D15_63") (pintype "bidirectional"))
      (node (ref "U100") (pin "22") (pinfunction "B0_22") (pintype "bidirectional"))
      (node (ref "U105") (pin "15") (pinfunction "B7_15") (pintype "bidirectional"))
    )
    (net (code "226") (name "Z_BERR") (class "Default")
      (node (ref "C1") (pin "46") (pinfunction "/BERR_46") (pintype "bidirectional"))
      (node (ref "U307") (pin "5") (pinfunction "3A_5") (pintype "unspecified"))
    )
    (net (code "227") (name "Z_BGn") (class "Default")
      (node (ref "C1") (pin "64") (pinfunction "/BGn_64") (pintype "bidirectional"))
      (node (ref "U303") (pin "5") (pinfunction "I_5") (pintype "unspecified"))
    )
    (net (code "228") (name "Z_BRn") (class "Default")
      (node (ref "C1") (pin "60") (pinfunction "/BRn_60") (pintype "bidirectional"))
      (node (ref "U303") (pin "25") (pinfunction "IOQ_25") (pintype "unspecified"))
    )
    (net (code "229") (name "Z_CFGIN") (class "Default")
      (node (ref "C1") (pin "12") (pinfunction "/CFGINn_12") (pintype "bidirectional"))
      (node (ref "U202") (pin "18") (pinfunction "IOQ_18") (pintype "unspecified"))
    )
    (net (code "230") (name "Z_CFGOUT") (class "Default")
      (node (ref "C1") (pin "11") (pinfunction "/CFGOUTn_11") (pintype "unspecified"))
      (node (ref "U200") (pin "1") (pinfunction "OE#_1") (pintype "unspecified"))
      (node (ref "U202") (pin "21") (pinfunction "IOQ_21") (pintype "unspecified"))
      (node (ref "U205") (pin "13") (pinfunction "I_13") (pintype "unspecified"))
      (node (ref "U207") (pin "16") (pinfunction "I_16") (pintype "unspecified"))
    )
    (net (code "231") (name "Z_CINH") (class "Default")
      (node (ref "C1") (pin "17") (pinfunction "/CINH,/OVR_17") (pintype "bidirectional"))
      (node (ref "U202") (pin "24") (pinfunction "IOQ_24") (pintype "unspecified"))
    )
    (net (code "232") (name "Z_D16") (class "Default")
      (node (ref "C1") (pin "75") (pinfunction "RSVD+D16,D0_75") (pintype "unspecified"))
      (node (ref "U108") (pin "22") (pinfunction "B0_22") (pintype "bidirectional"))
    )
    (net (code "233") (name "Z_D17") (class "Default")
      (node (ref "C1") (pin "77") (pinfunction "RSVD+D17,D1_77") (pintype "unspecified"))
      (node (ref "U108") (pin "21") (pinfunction "B1_21") (pintype "bidirectional"))
    )
    (net (code "234") (name "Z_D18") (class "Default")
      (node (ref "C1") (pin "79") (pinfunction "RSVD+D18,D2_79") (pintype "output"))
      (node (ref "U108") (pin "20") (pinfunction "B2_20") (pintype "bidirectional"))
    )
    (net (code "235") (name "Z_D19") (class "Default")
      (node (ref "C1") (pin "81") (pinfunction "RSVD+D19,D3_81") (pintype "unspecified"))
      (node (ref "U108") (pin "19") (pinfunction "B3_19") (pintype "bidirectional"))
    )
    (net (code "236") (name "Z_D20") (class "Default")
      (node (ref "C1") (pin "83") (pinfunction "RSVD+D20,D4_83") (pintype "output"))
      (node (ref "U108") (pin "18") (pinfunction "B4_18") (pintype "bidirectional"))
    )
    (net (code "237") (name "Z_D21") (class "Default")
      (node (ref "C1") (pin "86") (pinfunction "RSVD+D21,D5_86") (pintype "bidirectional"))
      (node (ref "U108") (pin "17") (pinfunction "B5_17") (pintype "bidirectional"))
    )
    (net (code "238") (name "Z_D22") (class "Default")
      (node (ref "C1") (pin "84") (pinfunction "RSVD+D22,D6_84") (pintype "output"))
      (node (ref "U108") (pin "16") (pinfunction "B6_16") (pintype "bidirectional"))
    )
    (net (code "239") (name "Z_D23") (class "Default")
      (node (ref "C1") (pin "82") (pinfunction "RSVD+D23,D7_82") (pintype "bidirectional"))
      (node (ref "U108") (pin "15") (pinfunction "B7_15") (pintype "bidirectional"))
    )
    (net (code "240") (name "Z_DOE") (class "Default")
      (node (ref "C1") (pin "93") (pinfunction "DOE_93") (pintype "unspecified"))
      (node (ref "U109") (pin "16") (pinfunction "B2_16") (pintype "unspecified"))
    )
    (net (code "241") (name "Z_DS0") (class "Default")
      (node (ref "C1") (pin "51") (pinfunction "/DS0,/VMA_51") (pintype "unspecified"))
      (node (ref "U109") (pin "11") (pinfunction "B7_11") (pintype "unspecified"))
    )
    (net (code "242") (name "Z_DS1") (class "Default")
      (node (ref "C1") (pin "98") (pinfunction "/DS1,NC_98") (pintype "bidirectional"))
      (node (ref "U109") (pin "12") (pinfunction "B6_12") (pintype "unspecified"))
    )
    (net (code "243") (name "Z_DS2") (class "Default")
      (node (ref "C1") (pin "70") (pinfunction "/DS2,/LDS_70") (pintype "unspecified"))
      (node (ref "FB508") (pin "2") (pinfunction "2_2") (pintype "unspecified"))
    )
    (net (code "244") (name "Z_DS3") (class "Default")
      (node (ref "C1") (pin "72") (pinfunction "/DS3,/UDS_72") (pintype "unspecified"))
      (node (ref "FB507") (pin "2") (pinfunction "2_2") (pintype "unspecified"))
    )
    (net (code "245") (name "Z_DTACK") (class "Default")
      (node (ref "C1") (pin "66") (pinfunction "/DTACK_66") (pintype "unspecified"))
      (node (ref "C306B") (pin "1") (pinfunction "1_1") (pintype "input"))
      (node (ref "U205") (pin "20") (pinfunction "IOQ_20") (pintype "unspecified"))
      (node (ref "U306") (pin "9") (pinfunction "I_9") (pintype "unspecified"))
    )
    (net (code "246") (name "Z_FC0") (class "Default")
      (node (ref "C1") (pin "31") (pinfunction "FC0_31") (pintype "unspecified"))
      (node (ref "U109") (pin "17") (pinfunction "B1_17") (pintype "unspecified"))
    )
    (net (code "247") (name "Z_FC1") (class "Default")
      (node (ref "C1") (pin "33") (pinfunction "FC1_33") (pintype "unspecified"))
      (node (ref "U109") (pin "18") (pinfunction "B0_18") (pintype "unspecified"))
    )
    (net (code "248") (name "Z_FC2") (class "Default")
      (node (ref "C1") (pin "35") (pinfunction "FC2_35") (pintype "unspecified"))
      (node (ref "U103") (pin "12") (pinfunction "B6_12") (pintype "unspecified"))
    )
    (net (code "249") (name "Z_FCS") (class "Default")
      (node (ref "C1") (pin "97") (pinfunction "/FCS,NC_97") (pintype "unspecified"))
      (node (ref "FB501") (pin "2") (pinfunction "2_2") (pintype "unspecified"))
      (node (ref "U305") (pin "21") (pinfunction "IOQ_21") (pintype "unspecified"))
    )
    (net (code "250") (name "Z_INT2") (class "Default")
      (node (ref "C1") (pin "19") (pinfunction "/INT2_19") (pintype "bidirectional"))
      (node (ref "U207") (pin "27") (pinfunction "IOQ_27") (pintype "unspecified"))
    )
    (net (code "251") (name "Z_IORST") (class "Default")
      (node (ref "C1") (pin "94") (pinfunction "/IORST,/BUSRST_94") (pintype "bidirectional"))
      (node (ref "U307") (pin "9") (pinfunction "4A_9") (pintype "unspecified"))
    )
    (net (code "252") (name "Z_LOCK") (class "Default")
      (node (ref "C1") (pin "29") (pinfunction "/LOCK,A1_29") (pintype "unspecified"))
      (node (ref "U203") (pin "6") (pinfunction "I_6") (pintype "unspecified"))
    )
    (net (code "253") (name "Z_MTACK") (class "Default")
      (node (ref "C1") (pin "48") (pinfunction "/MTACK,/VPA_48") (pintype "bidirectional"))
      (node (ref "U306") (pin "5") (pinfunction "I_5") (pintype "unspecified"))
    )
    (net (code "254") (name "Z_MTCR") (class "Default")
      (node (ref "C1") (pin "18") (pinfunction "/MTCR,XRDY_18") (pintype "bidirectional"))
      (node (ref "U109") (pin "15") (pinfunction "B3_15") (pintype "unspecified"))
    )
    (net (code "255") (name "Z_READ") (class "Default")
      (node (ref "C1") (pin "68") (pinfunction "READ_68") (pintype "unspecified"))
      (node (ref "U103") (pin "11") (pinfunction "B7_11") (pintype "unspecified"))
    )
    (net (code "256") (name "Z_SENSEZ3") (class "Default")
      (node (ref "C1") (pin "91") (pinfunction "SenseZ3,GND_91") (pintype "output"))
      (node (ref "R100A") (pin "1") (pinfunction "1_1") (pintype "input"))
      (node (ref "U202") (pin "20") (pinfunction "IOQ_20") (pintype "unspecified"))
    )
    (net (code "257") (name "Z_SLAVE") (class "Default")
      (node (ref "C1") (pin "09") (pinfunction "/SLAVEn_09") (pintype "bidirectional"))
      (node (ref "U202") (pin "26") (pinfunction "IOQ_26") (pintype "unspecified"))
      (node (ref "U203") (pin "20") (pinfunction "IOQ_20") (pintype "unspecified"))
      (node (ref "U205") (pin "3") (pinfunction "I_3") (pintype "unspecified"))
      (node (ref "U207") (pin "13") (pinfunction "I_13") (pintype "unspecified"))
      (node (ref "U303") (pin "7") (pinfunction "I_7") (pintype "unspecified"))
    )
    (net (code "258") (name "unconnected-(C1--5V-Pad08)") (class "Default")
      (node (ref "C1") (pin "08") (pinfunction "-5V_08") (pintype "bidirectional+no_connect"))
    )
    (net (code "259") (name "unconnected-(C1--12V-Pad20)") (class "Default")
      (node (ref "C1") (pin "20") (pinfunction "-12V_20") (pintype "unspecified+no_connect"))
    )
    (net (code "260") (name "unconnected-(C1-CDAC_Clock-Pad15)") (class "Default")
      (node (ref "C1") (pin "15") (pinfunction "CDAC_Clock_15") (pintype "unspecified+no_connect"))
    )
    (net (code "261") (name "unconnected-(C1-E_Clock-Pad50)") (class "Default")
      (node (ref "C1") (pin "50") (pinfunction "E_Clock_50") (pintype "bidirectional+no_connect"))
    )
    (net (code "262") (name "unconnected-(C1-RSVD,{slash}EINT1-Pad96)") (class "Default")
      (node (ref "C1") (pin "96") (pinfunction "RSVD,/EINT1_96") (pintype "bidirectional+no_connect"))
    )
    (net (code "263") (name "unconnected-(C1-RSVD,{slash}EINT4-Pad44)") (class "Default")
      (node (ref "C1") (pin "44") (pinfunction "RSVD,/EINT4_44") (pintype "bidirectional+no_connect"))
    )
    (net (code "264") (name "unconnected-(C1-RSVD,{slash}EINT5-Pad42)") (class "Default")
      (node (ref "C1") (pin "42") (pinfunction "RSVD,/EINT5_42") (pintype "bidirectional+no_connect"))
    )
    (net (code "265") (name "unconnected-(C1-RSVD,{slash}EINT7-Pad40)") (class "Default")
      (node (ref "C1") (pin "40") (pinfunction "RSVD,/EINT7_40") (pintype "bidirectional+no_connect"))
    )
    (net (code "266") (name "unconnected-(C1-{slash}BCLR,{slash}GBG-Pad95)") (class "Default")
      (node (ref "C1") (pin "95") (pinfunction "/BCLR,/GBG_95") (pintype "bidirectional+no_connect"))
    )
    (net (code "267") (name "unconnected-(C1-{slash}BGACK-Pad62)") (class "Default")
      (node (ref "C1") (pin "62") (pinfunction "/BGACK_62") (pintype "bidirectional+no_connect"))
    )
    (net (code "268") (name "unconnected-(C1-{slash}C1_Clock-Pad16)") (class "Default")
      (node (ref "C1") (pin "16") (pinfunction "/C1_Clock_16") (pintype "bidirectional+no_connect"))
    )
    (net (code "269") (name "unconnected-(C1-{slash}C3_Clock-Pad14)") (class "Default")
      (node (ref "C1") (pin "14") (pinfunction "/C3_Clock_14") (pintype "bidirectional+no_connect"))
    )
    (net (code "270") (name "unconnected-(C1-{slash}CCS,{slash}AS-Pad74)") (class "Default")
      (node (ref "C1") (pin "74") (pinfunction "/CCS,/AS_74") (pintype "unspecified+no_connect"))
    )
    (net (code "271") (name "unconnected-(C1-{slash}HLT-Pad55)") (class "Default")
      (node (ref "C1") (pin "55") (pinfunction "/HLT_55") (pintype "output+no_connect"))
    )
    (net (code "272") (name "unconnected-(C1-{slash}INT6-Pad22)") (class "Default")
      (node (ref "C1") (pin "22") (pinfunction "/INT6_22") (pintype "output+no_connect"))
    )
    (net (code "273") (name "unconnected-(C1-{slash}OWN-Pad07)") (class "Default")
      (node (ref "C1") (pin "07") (pinfunction "/OWN_07") (pintype "unspecified+no_connect"))
    )
    (net (code "274") (name "unconnected-(C1-{slash}RST-Pad53)") (class "Default")
      (node (ref "C1") (pin "53") (pinfunction "/RST_53") (pintype "unspecified+no_connect"))
    )
    (net (code "275") (name "unconnected-(CN309-Pad25)") (class "Default")
      (node (ref "CN309") (pin "25") (pinfunction "25_25") (pintype "unspecified+no_connect"))
    )
    (net (code "276") (name "unconnected-(CN309-Pad34)") (class "Default")
      (node (ref "CN309") (pin "34") (pinfunction "34_34") (pintype "unspecified+no_connect"))
    )
    (net (code "277") (name "unconnected-(U202-IOQ-Pad25)") (class "Default")
      (node (ref "U202") (pin "25") (pinfunction "IOQ_25") (pintype "unspecified+no_connect"))
    )
    (net (code "278") (name "unconnected-(U203-IOQ-Pad18)") (class "Default")
      (node (ref "U203") (pin "18") (pinfunction "IOQ_18") (pintype "unspecified+no_connect"))
    )
    (net (code "279") (name "unconnected-(U203-IOQ-Pad19)") (class "Default")
      (node (ref "U203") (pin "19") (pinfunction "IOQ_19") (pintype "unspecified+no_connect"))
    )
    (net (code "280") (name "unconnected-(U203-IOQ-Pad21)") (class "Default")
      (node (ref "U203") (pin "21") (pinfunction "IOQ_21") (pintype "unspecified+no_connect"))
    )
    (net (code "281") (name "unconnected-(U207-I-Pad3)") (class "Default")
      (node (ref "U207") (pin "3") (pinfunction "I_3") (pintype "unspecified+no_connect"))
    )
    (net (code "282") (name "unconnected-(U207-I-Pad4)") (class "Default")
      (node (ref "U207") (pin "4") (pinfunction "I_4") (pintype "unspecified+no_connect"))
    )
    (net (code "283") (name "unconnected-(U207-I-Pad5)") (class "Default")
      (node (ref "U207") (pin "5") (pinfunction "I_5") (pintype "unspecified+no_connect"))
    )
    (net (code "284") (name "unconnected-(U207-IOQ-Pad17)") (class "Default")
      (node (ref "U207") (pin "17") (pinfunction "IOQ_17") (pintype "unspecified+no_connect"))
    )
    (net (code "285") (name "unconnected-(U207-IOQ-Pad18)") (class "Default")
      (node (ref "U207") (pin "18") (pinfunction "IOQ_18") (pintype "unspecified+no_connect"))
    )
    (net (code "286") (name "unconnected-(U207-IOQ-Pad20)") (class "Default")
      (node (ref "U207") (pin "20") (pinfunction "IOQ_20") (pintype "unspecified+no_connect"))
    )
    (net (code "287") (name "unconnected-(U207-IOQ-Pad21)") (class "Default")
      (node (ref "U207") (pin "21") (pinfunction "IOQ_21") (pintype "unspecified+no_connect"))
    )
    (net (code "288") (name "unconnected-(U207-IOQ-Pad23)") (class "Default")
      (node (ref "U207") (pin "23") (pinfunction "IOQ_23") (pintype "unspecified+no_connect"))
    )
    (net (code "289") (name "unconnected-(U207-IOQ-Pad25)") (class "Default")
      (node (ref "U207") (pin "25") (pinfunction "IOQ_25") (pintype "unspecified+no_connect"))
    )
    (net (code "290") (name "unconnected-(U300-BSYDIR-Pad108)") (class "Default")
      (node (ref "U300") (pin "108") (pinfunction "BSYDIR_108") (pintype "unspecified+no_connect"))
    )
    (net (code "291") (name "unconnected-(U300-FETCH{slash}-Pad97)") (class "Default")
      (node (ref "U300") (pin "97") (pinfunction "FETCH/_97") (pintype "unspecified+no_connect"))
    )
    (net (code "292") (name "unconnected-(U300-IGS-Pad104)") (class "Default")
      (node (ref "U300") (pin "104") (pinfunction "IGS_104") (pintype "unspecified+no_connect"))
    )
    (net (code "293") (name "unconnected-(U300-RSTDIR-Pad107)") (class "Default")
      (node (ref "U300") (pin "107") (pinfunction "RSTDIR_107") (pintype "unspecified+no_connect"))
    )
    (net (code "294") (name "unconnected-(U300-SC0-Pad88)") (class "Default")
      (node (ref "U300") (pin "88") (pinfunction "SC0_88") (pintype "unspecified+no_connect"))
    )
    (net (code "295") (name "unconnected-(U300-SC1-Pad89)") (class "Default")
      (node (ref "U300") (pin "89") (pinfunction "SC1_89") (pintype "unspecified+no_connect"))
    )
    (net (code "296") (name "unconnected-(U300-SDIR0-Pad142)") (class "Default")
      (node (ref "U300") (pin "142") (pinfunction "SDIR0_142") (pintype "unspecified+no_connect"))
    )
    (net (code "297") (name "unconnected-(U300-SDIR1-Pad141)") (class "Default")
      (node (ref "U300") (pin "141") (pinfunction "SDIR1_141") (pintype "unspecified+no_connect"))
    )
    (net (code "298") (name "unconnected-(U300-SDIR2-Pad140)") (class "Default")
      (node (ref "U300") (pin "140") (pinfunction "SDIR2_140") (pintype "unspecified+no_connect"))
    )
    (net (code "299") (name "unconnected-(U300-SDIR3-Pad138)") (class "Default")
      (node (ref "U300") (pin "138") (pinfunction "SDIR3_138") (pintype "unspecified+no_connect"))
    )
    (net (code "300") (name "unconnected-(U300-SDIR4-Pad137)") (class "Default")
      (node (ref "U300") (pin "137") (pinfunction "SDIR4_137") (pintype "unspecified+no_connect"))
    )
    (net (code "301") (name "unconnected-(U300-SDIR5-Pad135)") (class "Default")
      (node (ref "U300") (pin "135") (pinfunction "SDIR5_135") (pintype "unspecified+no_connect"))
    )
    (net (code "302") (name "unconnected-(U300-SDIR6-Pad134)") (class "Default")
      (node (ref "U300") (pin "134") (pinfunction "SDIR6_134") (pintype "unspecified+no_connect"))
    )
    (net (code "303") (name "unconnected-(U300-SDIR7-Pad133)") (class "Default")
      (node (ref "U300") (pin "133") (pinfunction "SDIR7_133") (pintype "unspecified+no_connect"))
    )
    (net (code "304") (name "unconnected-(U300-SDIRP-Pad132)") (class "Default")
      (node (ref "U300") (pin "132") (pinfunction "SDIRP_132") (pintype "unspecified+no_connect"))
    )
    (net (code "305") (name "unconnected-(U300-SELDIR-Pad106)") (class "Default")
      (node (ref "U300") (pin "106") (pinfunction "SELDIR_106") (pintype "unspecified+no_connect"))
    )
    (net (code "306") (name "unconnected-(U300-TGS-Pad103)") (class "Default")
      (node (ref "U300") (pin "103") (pinfunction "TGS_103") (pintype "unspecified+no_connect"))
    )
    (net (code "307") (name "unconnected-(U300-UPS0-TT0{slash}-Pad34)") (class "Default")
      (node (ref "U300") (pin "34") (pinfunction "UPS0-TT0/_34") (pintype "unspecified+no_connect"))
    )
    (net (code "308") (name "unconnected-(U301-Tri-state-Pad1)") (class "Default")
      (node (ref "U301") (pin "1") (pinfunction "Tri-state_1") (pintype "unspecified+no_connect"))
    )
    (net (code "309") (name "unconnected-(U302-Q1#-Pad8)") (class "Default")
      (node (ref "U302") (pin "8") (pinfunction "Q1#_8") (pintype "unspecified+no_connect"))
    )
    (net (code "310") (name "unconnected-(U302-Q1-Pad9)") (class "Default")
      (node (ref "U302") (pin "9") (pinfunction "Q1_9") (pintype "unspecified+no_connect"))
    )
    (net (code "311") (name "unconnected-(U303-I-Pad13)") (class "Default")
      (node (ref "U303") (pin "13") (pinfunction "I_13") (pintype "unspecified+no_connect"))
    )
    (net (code "312") (name "unconnected-(U303-I-Pad16)") (class "Default")
      (node (ref "U303") (pin "16") (pinfunction "I_16") (pintype "unspecified+no_connect"))
    )
    (net (code "313") (name "unconnected-(U303-IOQ-Pad17)") (class "Default")
      (node (ref "U303") (pin "17") (pinfunction "IOQ_17") (pintype "unspecified+no_connect"))
    )
    (net (code "314") (name "unconnected-(U303-IOQ-Pad18)") (class "Default")
      (node (ref "U303") (pin "18") (pinfunction "IOQ_18") (pintype "unspecified+no_connect"))
    )
    (net (code "315") (name "unconnected-(U303-IOQ-Pad19)") (class "Default")
      (node (ref "U303") (pin "19") (pinfunction "IOQ_19") (pintype "unspecified+no_connect"))
    )
    (net (code "316") (name "unconnected-(U303-IOQ-Pad23)") (class "Default")
      (node (ref "U303") (pin "23") (pinfunction "IOQ_23") (pintype "unspecified+no_connect"))
    )
    (net (code "317") (name "unconnected-(U303-IOQ-Pad24)") (class "Default")
      (node (ref "U303") (pin "24") (pinfunction "IOQ_24") (pintype "unspecified+no_connect"))
    )
    (net (code "318") (name "unconnected-(U303-IOQ-Pad26)") (class "Default")
      (node (ref "U303") (pin "26") (pinfunction "IOQ_26") (pintype "unspecified+no_connect"))
    )
    (net (code "319") (name "unconnected-(U304-I-Pad16)") (class "Default")
      (node (ref "U304") (pin "16") (pinfunction "I_16") (pintype "unspecified+no_connect"))
    )
    (net (code "320") (name "unconnected-(U304-IOQ-Pad17)") (class "Default")
      (node (ref "U304") (pin "17") (pinfunction "IOQ_17") (pintype "unspecified+no_connect"))
    )
    (net (code "321") (name "unconnected-(U304-IOQ-Pad18)") (class "Default")
      (node (ref "U304") (pin "18") (pinfunction "IOQ_18") (pintype "unspecified+no_connect"))
    )
    (net (code "322") (name "unconnected-(U304-IOQ-Pad23)") (class "Default")
      (node (ref "U304") (pin "23") (pinfunction "IOQ_23") (pintype "unspecified+no_connect"))
    )
    (net (code "323") (name "unconnected-(U305-I-Pad11)") (class "Default")
      (node (ref "U305") (pin "11") (pinfunction "I_11") (pintype "unspecified+no_connect"))
    )
    (net (code "324") (name "unconnected-(U305-I-Pad12)") (class "Default")
      (node (ref "U305") (pin "12") (pinfunction "I_12") (pintype "unspecified+no_connect"))
    )
    (net (code "325") (name "unconnected-(U305-IOQ-Pad17)") (class "Default")
      (node (ref "U305") (pin "17") (pinfunction "IOQ_17") (pintype "unspecified+no_connect"))
    )
    (net (code "326") (name "unconnected-(U305-IOQ-Pad18)") (class "Default")
      (node (ref "U305") (pin "18") (pinfunction "IOQ_18") (pintype "unspecified+no_connect"))
    )
    (net (code "327") (name "unconnected-(U306-I-Pad16)") (class "Default")
      (node (ref "U306") (pin "16") (pinfunction "I_16") (pintype "unspecified+no_connect"))
    )
    (net (code "328") (name "unconnected-(U306-IOQ-Pad18)") (class "Default")
      (node (ref "U306") (pin "18") (pinfunction "IOQ_18") (pintype "unspecified+no_connect"))
    )
    (net (code "329") (name "unconnected-(U306-IOQ-Pad24)") (class "Default")
      (node (ref "U306") (pin "24") (pinfunction "IOQ_24") (pintype "unspecified+no_connect"))
    )
    (net (code "330") (name "unconnected-(U306-IOQ-Pad26)") (class "Default")
      (node (ref "U306") (pin "26") (pinfunction "IOQ_26") (pintype "unspecified+no_connect"))
    )
    (net (code "331") (name "unconnected-(U307-5Y-Pad10)") (class "Default")
      (node (ref "U307") (pin "10") (pinfunction "5Y_10") (pintype "unspecified+no_connect"))
    )
    (net (code "332") (name "unconnected-(U307-6Y-Pad12)") (class "Default")
      (node (ref "U307") (pin "12") (pinfunction "6Y_12") (pintype "unspecified+no_connect"))
    )
    (net (code "333") (name "unconnected-(U310-NC-Pad14)") (class "Default")
      (node (ref "U310") (pin "14") (pinfunction "NC_14") (pintype "unspecified+no_connect"))
    )
    (net (code "334") (name "unconnected-(U311-NC-Pad14)") (class "Default")
      (node (ref "U311") (pin "14") (pinfunction "NC_14") (pintype "unspecified+no_connect"))
    )
  )
)
